# ProPrj_RGB_AddOn.net
KiCad netlist of a schematic drawn in EasyEDA Pro
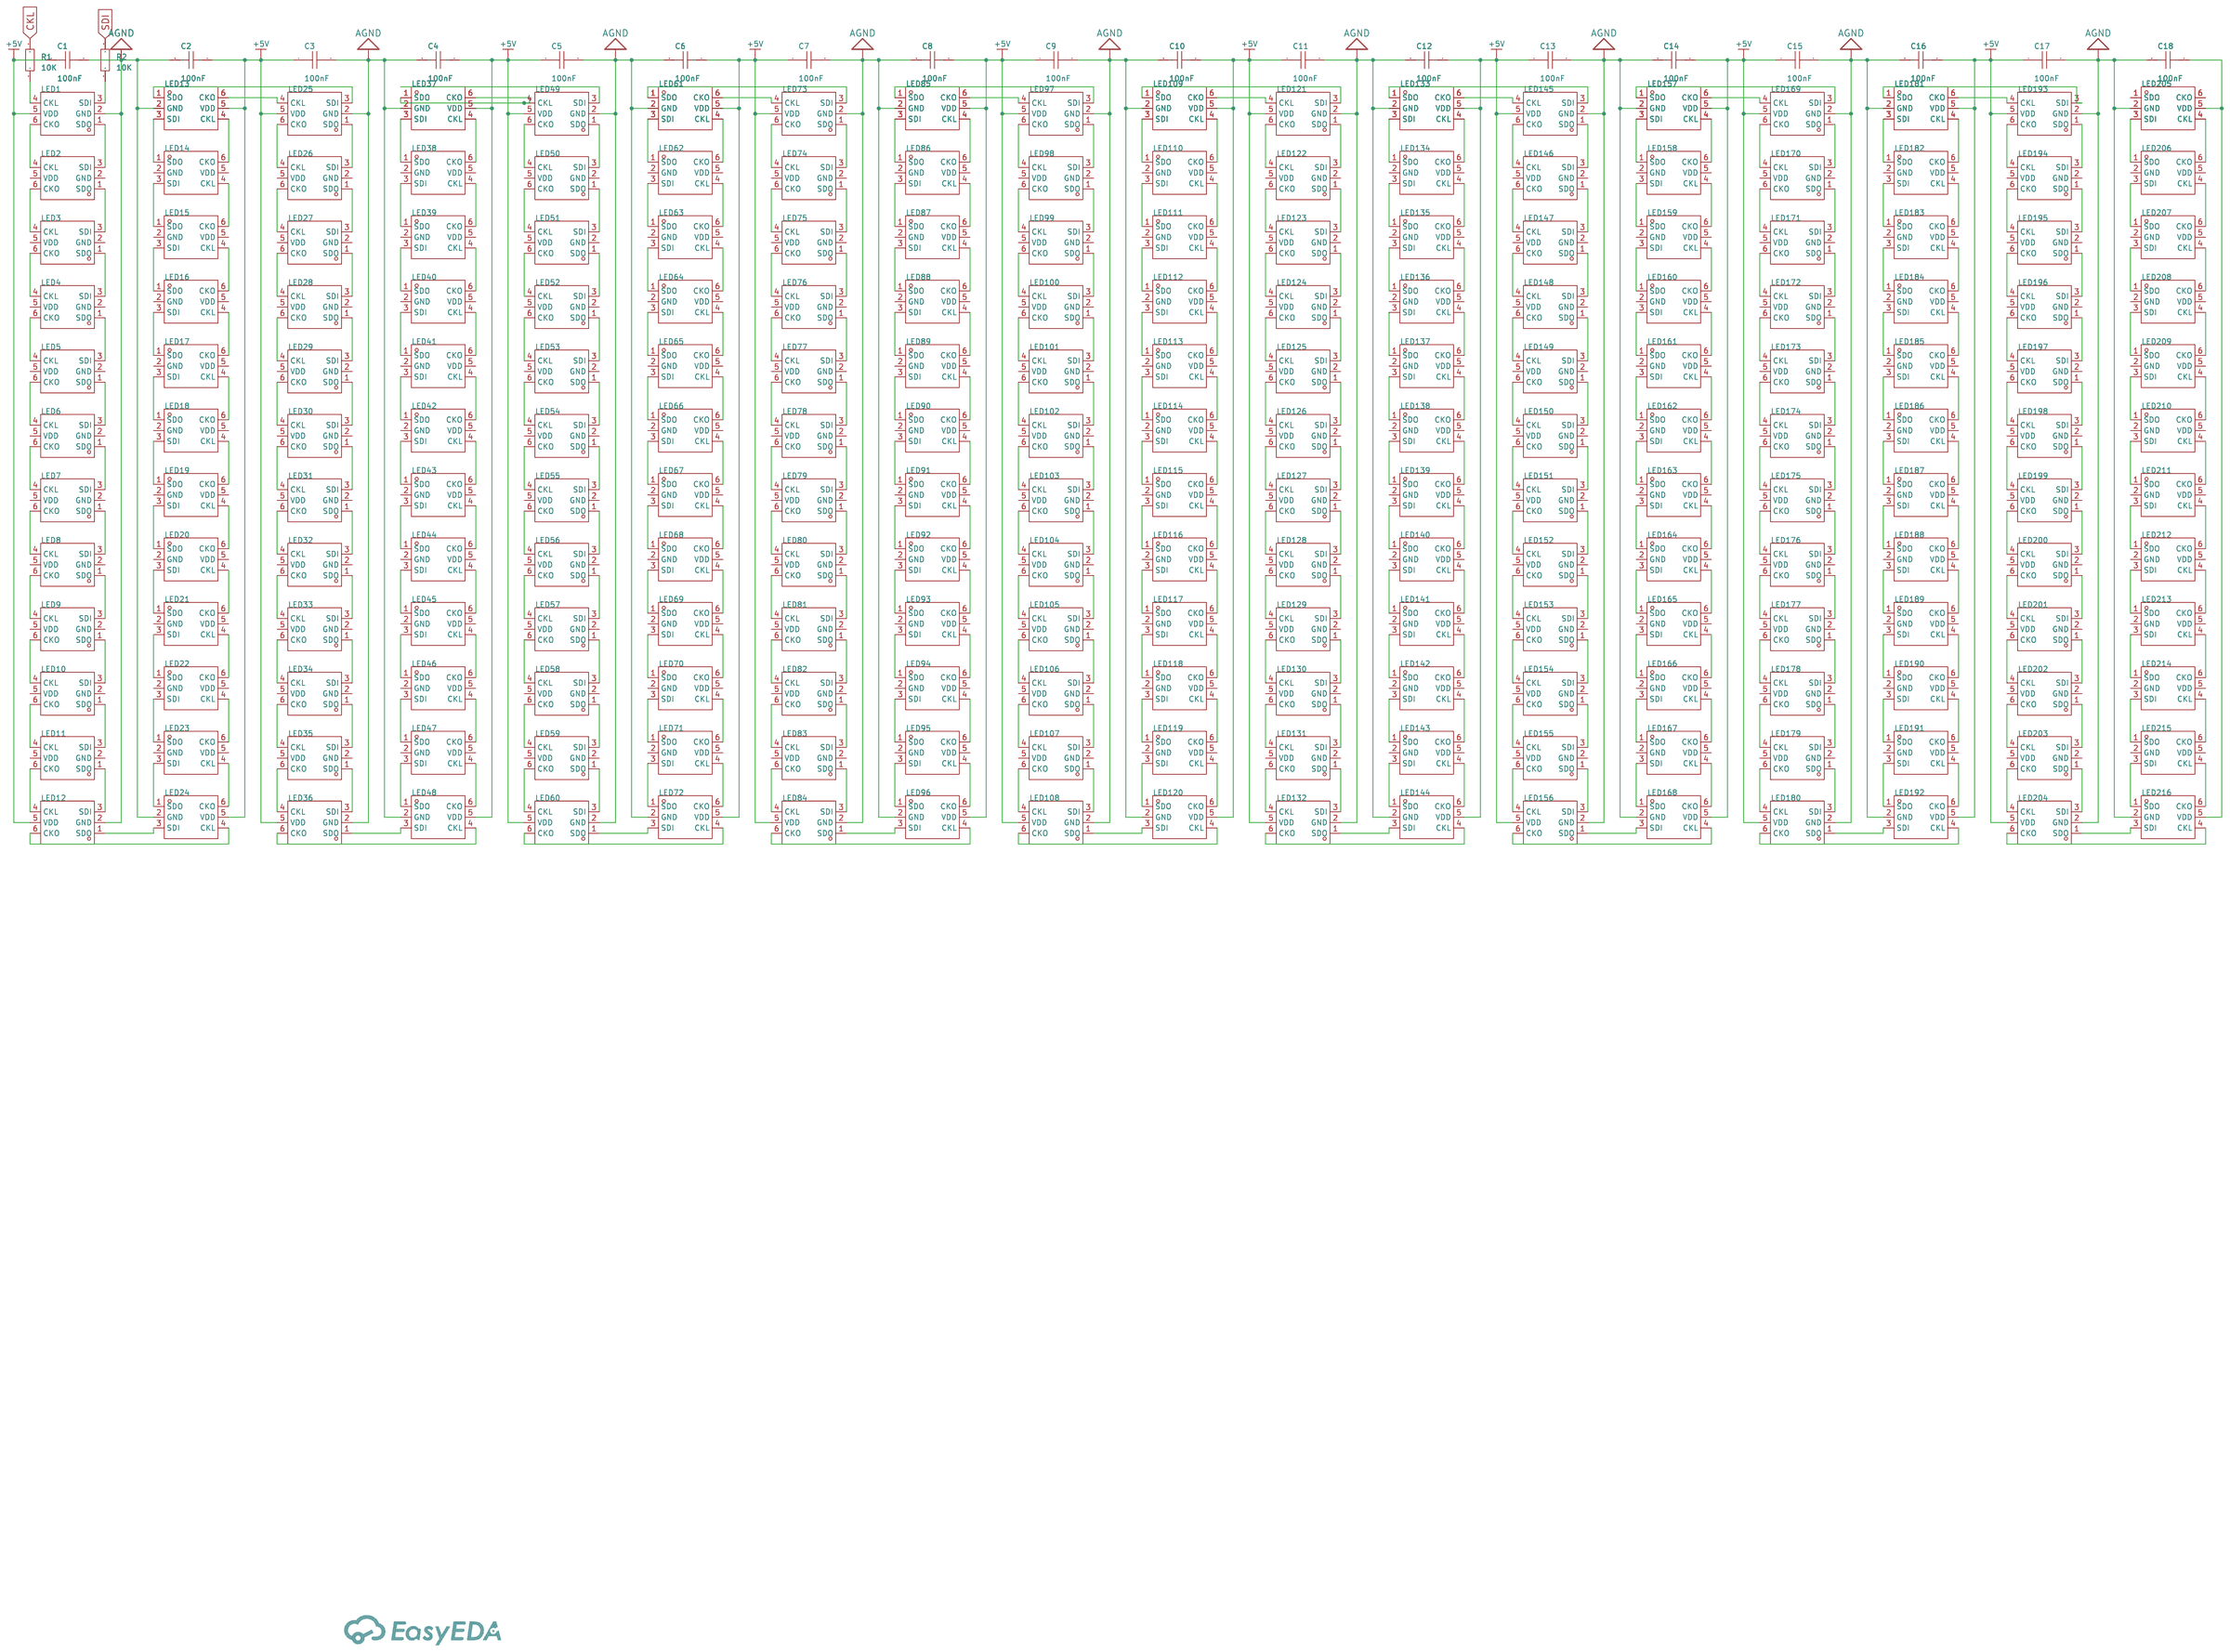
[diagram p0: Matrix]
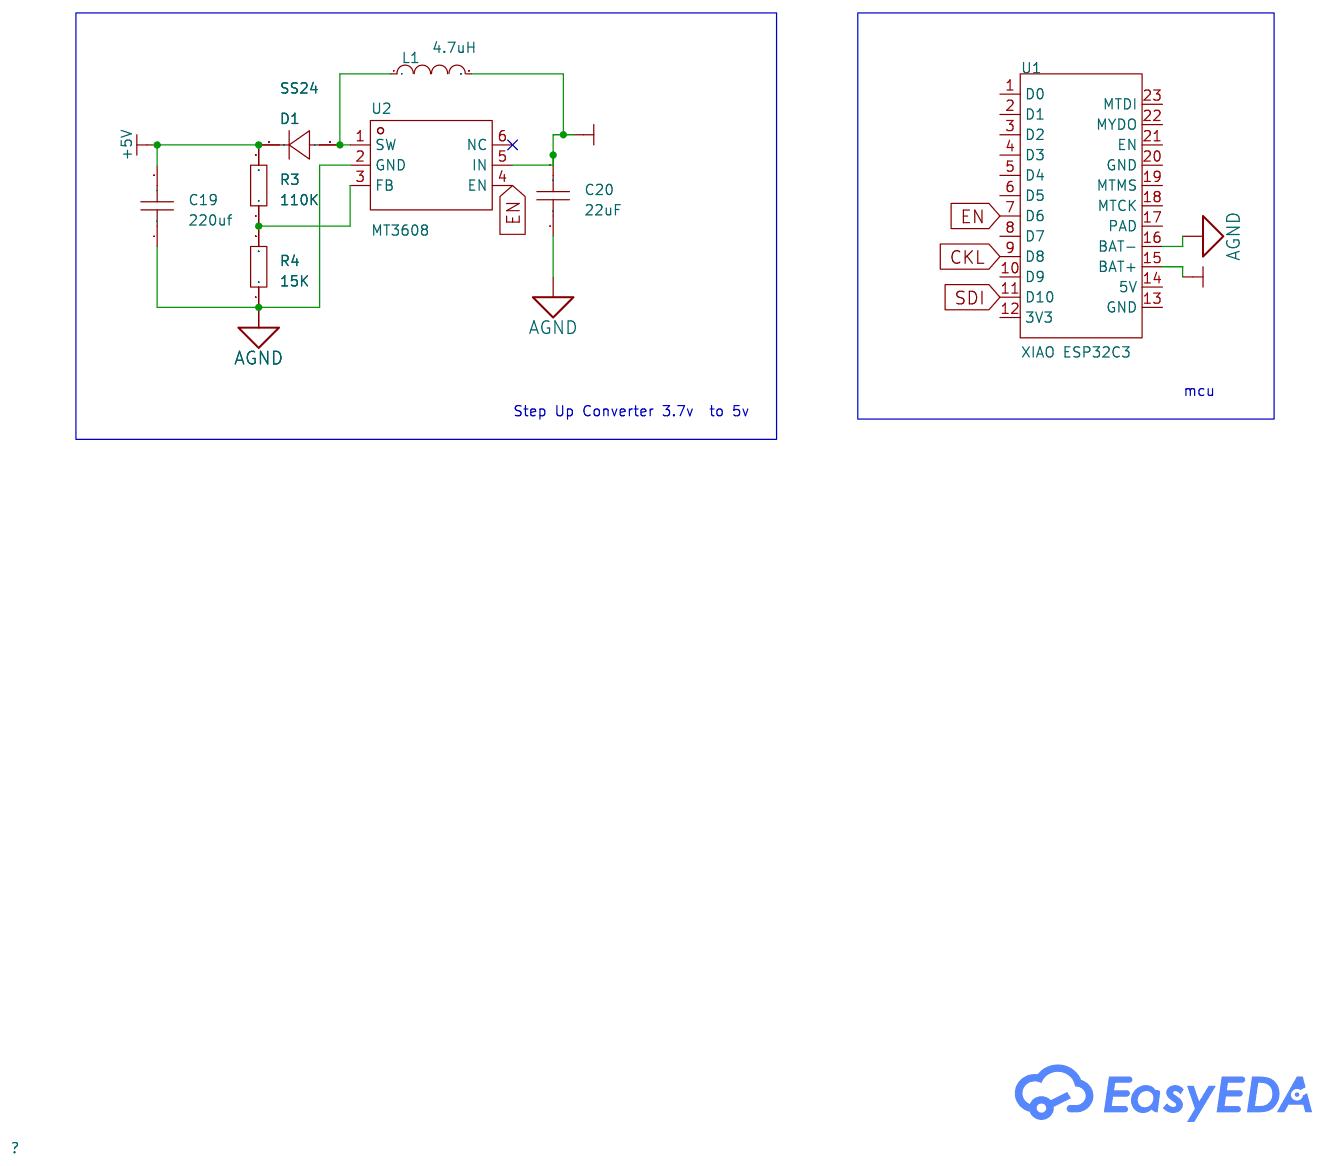
[diagram p1: MCU]

(export (version "E")
  (design (tool "Eeschema 10.0.6"))
  (components
    (comp (ref "C1")
      (value "100nF")
      (footprint "easyedapro:C0603")
      (libsource (lib "easyedapro") (part "CAP"))
    )
    (comp (ref "C2")
      (value "100nF")
      (footprint "easyedapro:C0603")
      (libsource (lib "easyedapro") (part "CAP"))
    )
    (comp (ref "C3")
      (value "100nF")
      (footprint "easyedapro:C0603")
      (libsource (lib "easyedapro") (part "CAP"))
    )
    (comp (ref "C4")
      (value "100nF")
      (footprint "easyedapro:C0603")
      (libsource (lib "easyedapro") (part "CAP"))
    )
    (comp (ref "C5")
      (value "100nF")
      (footprint "easyedapro:C0603")
      (libsource (lib "easyedapro") (part "CAP"))
    )
    (comp (ref "C6")
      (value "100nF")
      (footprint "easyedapro:C0603")
      (libsource (lib "easyedapro") (part "CAP"))
    )
    (comp (ref "C7")
      (value "100nF")
      (footprint "easyedapro:C0603")
      (libsource (lib "easyedapro") (part "CAP"))
    )
    (comp (ref "C8")
      (value "100nF")
      (footprint "easyedapro:C0603")
      (libsource (lib "easyedapro") (part "CAP"))
    )
    (comp (ref "C9")
      (value "100nF")
      (footprint "easyedapro:C0603")
      (libsource (lib "easyedapro") (part "CAP"))
    )
    (comp (ref "C10")
      (value "100nF")
      (footprint "easyedapro:C0603")
      (libsource (lib "easyedapro") (part "CAP"))
    )
    (comp (ref "C11")
      (value "100nF")
      (footprint "easyedapro:C0603")
      (libsource (lib "easyedapro") (part "CAP"))
    )
    (comp (ref "C12")
      (value "100nF")
      (footprint "easyedapro:C0603")
      (libsource (lib "easyedapro") (part "CAP"))
    )
    (comp (ref "C13")
      (value "100nF")
      (footprint "easyedapro:C0603")
      (libsource (lib "easyedapro") (part "CAP"))
    )
    (comp (ref "C14")
      (value "100nF")
      (footprint "easyedapro:C0603")
      (libsource (lib "easyedapro") (part "CAP"))
    )
    (comp (ref "C15")
      (value "100nF")
      (footprint "easyedapro:C0603")
      (libsource (lib "easyedapro") (part "CAP"))
    )
    (comp (ref "C16")
      (value "100nF")
      (footprint "easyedapro:C0603")
      (libsource (lib "easyedapro") (part "CAP"))
    )
    (comp (ref "C17")
      (value "100nF")
      (footprint "easyedapro:C0603")
      (libsource (lib "easyedapro") (part "CAP"))
    )
    (comp (ref "C18")
      (value "100nF")
      (footprint "easyedapro:C0603")
      (libsource (lib "easyedapro") (part "CAP"))
    )
    (comp (ref "LED1")
      (value "SK9822-EC20")
      (footprint "easyedapro:LED-SMD_6P-L2.0-W2.0-P0.80-TL")
      (description "Wavelength:620nm~625nm；460nm~470nm；520nm~530nm Operating Temperature:-40°C~+80°C")
      (fields (field (name "Manufacturer") "欧思科光电"))
      (libsource (lib "easyedapro") (part "SK9822-EC20"))
    )
    (comp (ref "LED2")
      (value "SK9822-EC20")
      (footprint "easyedapro:LED-SMD_6P-L2.0-W2.0-P0.80-TL")
      (description "Wavelength:620nm~625nm；460nm~470nm；520nm~530nm Operating Temperature:-40°C~+80°C")
      (fields (field (name "Manufacturer") "欧思科光电"))
      (libsource (lib "easyedapro") (part "SK9822-EC20"))
    )
    (comp (ref "LED3")
      (value "SK9822-EC20")
      (footprint "easyedapro:LED-SMD_6P-L2.0-W2.0-P0.80-TL")
      (description "Wavelength:620nm~625nm；460nm~470nm；520nm~530nm Operating Temperature:-40°C~+80°C")
      (fields (field (name "Manufacturer") "欧思科光电"))
      (libsource (lib "easyedapro") (part "SK9822-EC20"))
    )
    (comp (ref "LED4")
      (value "SK9822-EC20")
      (footprint "easyedapro:LED-SMD_6P-L2.0-W2.0-P0.80-TL")
      (description "Wavelength:620nm~625nm；460nm~470nm；520nm~530nm Operating Temperature:-40°C~+80°C")
      (fields (field (name "Manufacturer") "欧思科光电"))
      (libsource (lib "easyedapro") (part "SK9822-EC20"))
    )
    (comp (ref "LED5")
      (value "SK9822-EC20")
      (footprint "easyedapro:LED-SMD_6P-L2.0-W2.0-P0.80-TL")
      (description "Wavelength:620nm~625nm；460nm~470nm；520nm~530nm Operating Temperature:-40°C~+80°C")
      (fields (field (name "Manufacturer") "欧思科光电"))
      (libsource (lib "easyedapro") (part "SK9822-EC20"))
    )
    (comp (ref "LED6")
      (value "SK9822-EC20")
      (footprint "easyedapro:LED-SMD_6P-L2.0-W2.0-P0.80-TL")
      (description "Wavelength:620nm~625nm；460nm~470nm；520nm~530nm Operating Temperature:-40°C~+80°C")
      (fields (field (name "Manufacturer") "欧思科光电"))
      (libsource (lib "easyedapro") (part "SK9822-EC20"))
    )
    (comp (ref "LED7")
      (value "SK9822-EC20")
      (footprint "easyedapro:LED-SMD_6P-L2.0-W2.0-P0.80-TL")
      (description "Wavelength:620nm~625nm；460nm~470nm；520nm~530nm Operating Temperature:-40°C~+80°C")
      (fields (field (name "Manufacturer") "欧思科光电"))
      (libsource (lib "easyedapro") (part "SK9822-EC20"))
    )
    (comp (ref "LED8")
      (value "SK9822-EC20")
      (footprint "easyedapro:LED-SMD_6P-L2.0-W2.0-P0.80-TL")
      (description "Wavelength:620nm~625nm；460nm~470nm；520nm~530nm Operating Temperature:-40°C~+80°C")
      (fields (field (name "Manufacturer") "欧思科光电"))
      (libsource (lib "easyedapro") (part "SK9822-EC20"))
    )
    (comp (ref "LED9")
      (value "SK9822-EC20")
      (footprint "easyedapro:LED-SMD_6P-L2.0-W2.0-P0.80-TL")
      (description "Wavelength:620nm~625nm；460nm~470nm；520nm~530nm Operating Temperature:-40°C~+80°C")
      (fields (field (name "Manufacturer") "欧思科光电"))
      (libsource (lib "easyedapro") (part "SK9822-EC20"))
    )
    (comp (ref "LED10")
      (value "SK9822-EC20")
      (footprint "easyedapro:LED-SMD_6P-L2.0-W2.0-P0.80-TL")
      (description "Wavelength:620nm~625nm；460nm~470nm；520nm~530nm Operating Temperature:-40°C~+80°C")
      (fields (field (name "Manufacturer") "欧思科光电"))
      (libsource (lib "easyedapro") (part "SK9822-EC20"))
    )
    (comp (ref "LED11")
      (value "SK9822-EC20")
      (footprint "easyedapro:LED-SMD_6P-L2.0-W2.0-P0.80-TL")
      (description "Wavelength:620nm~625nm；460nm~470nm；520nm~530nm Operating Temperature:-40°C~+80°C")
      (fields (field (name "Manufacturer") "欧思科光电"))
      (libsource (lib "easyedapro") (part "SK9822-EC20"))
    )
    (comp (ref "LED12")
      (value "SK9822-EC20")
      (footprint "easyedapro:LED-SMD_6P-L2.0-W2.0-P0.80-TL")
      (description "Wavelength:620nm~625nm；460nm~470nm；520nm~530nm Operating Temperature:-40°C~+80°C")
      (fields (field (name "Manufacturer") "欧思科光电"))
      (libsource (lib "easyedapro") (part "SK9822-EC20"))
    )
    (comp (ref "LED13")
      (value "SK9822-EC20")
      (footprint "easyedapro:LED-SMD_6P-L2.0-W2.0-P0.80-TL")
      (description "Wavelength:620nm~625nm；460nm~470nm；520nm~530nm Operating Temperature:-40°C~+80°C")
      (fields (field (name "Manufacturer") "欧思科光电"))
      (libsource (lib "easyedapro") (part "SK9822-EC20"))
    )
    (comp (ref "LED14")
      (value "SK9822-EC20")
      (footprint "easyedapro:LED-SMD_6P-L2.0-W2.0-P0.80-TL")
      (description "Wavelength:620nm~625nm；460nm~470nm；520nm~530nm Operating Temperature:-40°C~+80°C")
      (fields (field (name "Manufacturer") "欧思科光电"))
      (libsource (lib "easyedapro") (part "SK9822-EC20"))
    )
    (comp (ref "LED15")
      (value "SK9822-EC20")
      (footprint "easyedapro:LED-SMD_6P-L2.0-W2.0-P0.80-TL")
      (description "Wavelength:620nm~625nm；460nm~470nm；520nm~530nm Operating Temperature:-40°C~+80°C")
      (fields (field (name "Manufacturer") "欧思科光电"))
      (libsource (lib "easyedapro") (part "SK9822-EC20"))
    )
    (comp (ref "LED16")
      (value "SK9822-EC20")
      (footprint "easyedapro:LED-SMD_6P-L2.0-W2.0-P0.80-TL")
      (description "Wavelength:620nm~625nm；460nm~470nm；520nm~530nm Operating Temperature:-40°C~+80°C")
      (fields (field (name "Manufacturer") "欧思科光电"))
      (libsource (lib "easyedapro") (part "SK9822-EC20"))
    )
    (comp (ref "LED17")
      (value "SK9822-EC20")
      (footprint "easyedapro:LED-SMD_6P-L2.0-W2.0-P0.80-TL")
      (description "Wavelength:620nm~625nm；460nm~470nm；520nm~530nm Operating Temperature:-40°C~+80°C")
      (fields (field (name "Manufacturer") "欧思科光电"))
      (libsource (lib "easyedapro") (part "SK9822-EC20"))
    )
    (comp (ref "LED18")
      (value "SK9822-EC20")
      (footprint "easyedapro:LED-SMD_6P-L2.0-W2.0-P0.80-TL")
      (description "Wavelength:620nm~625nm；460nm~470nm；520nm~530nm Operating Temperature:-40°C~+80°C")
      (fields (field (name "Manufacturer") "欧思科光电"))
      (libsource (lib "easyedapro") (part "SK9822-EC20"))
    )
    (comp (ref "LED19")
      (value "SK9822-EC20")
      (footprint "easyedapro:LED-SMD_6P-L2.0-W2.0-P0.80-TL")
      (description "Wavelength:620nm~625nm；460nm~470nm；520nm~530nm Operating Temperature:-40°C~+80°C")
      (fields (field (name "Manufacturer") "欧思科光电"))
      (libsource (lib "easyedapro") (part "SK9822-EC20"))
    )
    (comp (ref "LED20")
      (value "SK9822-EC20")
      (footprint "easyedapro:LED-SMD_6P-L2.0-W2.0-P0.80-TL")
      (description "Wavelength:620nm~625nm；460nm~470nm；520nm~530nm Operating Temperature:-40°C~+80°C")
      (fields (field (name "Manufacturer") "欧思科光电"))
      (libsource (lib "easyedapro") (part "SK9822-EC20"))
    )
    (comp (ref "LED21")
      (value "SK9822-EC20")
      (footprint "easyedapro:LED-SMD_6P-L2.0-W2.0-P0.80-TL")
      (description "Wavelength:620nm~625nm；460nm~470nm；520nm~530nm Operating Temperature:-40°C~+80°C")
      (fields (field (name "Manufacturer") "欧思科光电"))
      (libsource (lib "easyedapro") (part "SK9822-EC20"))
    )
    (comp (ref "LED22")
      (value "SK9822-EC20")
      (footprint "easyedapro:LED-SMD_6P-L2.0-W2.0-P0.80-TL")
      (description "Wavelength:620nm~625nm；460nm~470nm；520nm~530nm Operating Temperature:-40°C~+80°C")
      (fields (field (name "Manufacturer") "欧思科光电"))
      (libsource (lib "easyedapro") (part "SK9822-EC20"))
    )
    (comp (ref "LED23")
      (value "SK9822-EC20")
      (footprint "easyedapro:LED-SMD_6P-L2.0-W2.0-P0.80-TL")
      (description "Wavelength:620nm~625nm；460nm~470nm；520nm~530nm Operating Temperature:-40°C~+80°C")
      (fields (field (name "Manufacturer") "欧思科光电"))
      (libsource (lib "easyedapro") (part "SK9822-EC20"))
    )
    (comp (ref "LED24")
      (value "SK9822-EC20")
      (footprint "easyedapro:LED-SMD_6P-L2.0-W2.0-P0.80-TL")
      (description "Wavelength:620nm~625nm；460nm~470nm；520nm~530nm Operating Temperature:-40°C~+80°C")
      (fields (field (name "Manufacturer") "欧思科光电"))
      (libsource (lib "easyedapro") (part "SK9822-EC20"))
    )
    (comp (ref "LED25")
      (value "SK9822-EC20")
      (footprint "easyedapro:LED-SMD_6P-L2.0-W2.0-P0.80-TL")
      (description "Wavelength:620nm~625nm；460nm~470nm；520nm~530nm Operating Temperature:-40°C~+80°C")
      (fields (field (name "Manufacturer") "欧思科光电"))
      (libsource (lib "easyedapro") (part "SK9822-EC20"))
    )
    (comp (ref "LED26")
      (value "SK9822-EC20")
      (footprint "easyedapro:LED-SMD_6P-L2.0-W2.0-P0.80-TL")
      (description "Wavelength:620nm~625nm；460nm~470nm；520nm~530nm Operating Temperature:-40°C~+80°C")
      (fields (field (name "Manufacturer") "欧思科光电"))
      (libsource (lib "easyedapro") (part "SK9822-EC20"))
    )
    (comp (ref "LED27")
      (value "SK9822-EC20")
      (footprint "easyedapro:LED-SMD_6P-L2.0-W2.0-P0.80-TL")
      (description "Wavelength:620nm~625nm；460nm~470nm；520nm~530nm Operating Temperature:-40°C~+80°C")
      (fields (field (name "Manufacturer") "欧思科光电"))
      (libsource (lib "easyedapro") (part "SK9822-EC20"))
    )
    (comp (ref "LED28")
      (value "SK9822-EC20")
      (footprint "easyedapro:LED-SMD_6P-L2.0-W2.0-P0.80-TL")
      (description "Wavelength:620nm~625nm；460nm~470nm；520nm~530nm Operating Temperature:-40°C~+80°C")
      (fields (field (name "Manufacturer") "欧思科光电"))
      (libsource (lib "easyedapro") (part "SK9822-EC20"))
    )
    (comp (ref "LED29")
      (value "SK9822-EC20")
      (footprint "easyedapro:LED-SMD_6P-L2.0-W2.0-P0.80-TL")
      (description "Wavelength:620nm~625nm；460nm~470nm；520nm~530nm Operating Temperature:-40°C~+80°C")
      (fields (field (name "Manufacturer") "欧思科光电"))
      (libsource (lib "easyedapro") (part "SK9822-EC20"))
    )
    (comp (ref "LED30")
      (value "SK9822-EC20")
      (footprint "easyedapro:LED-SMD_6P-L2.0-W2.0-P0.80-TL")
      (description "Wavelength:620nm~625nm；460nm~470nm；520nm~530nm Operating Temperature:-40°C~+80°C")
      (fields (field (name "Manufacturer") "欧思科光电"))
      (libsource (lib "easyedapro") (part "SK9822-EC20"))
    )
    (comp (ref "LED31")
      (value "SK9822-EC20")
      (footprint "easyedapro:LED-SMD_6P-L2.0-W2.0-P0.80-TL")
      (description "Wavelength:620nm~625nm；460nm~470nm；520nm~530nm Operating Temperature:-40°C~+80°C")
      (fields (field (name "Manufacturer") "欧思科光电"))
      (libsource (lib "easyedapro") (part "SK9822-EC20"))
    )
    (comp (ref "LED32")
      (value "SK9822-EC20")
      (footprint "easyedapro:LED-SMD_6P-L2.0-W2.0-P0.80-TL")
      (description "Wavelength:620nm~625nm；460nm~470nm；520nm~530nm Operating Temperature:-40°C~+80°C")
      (fields (field (name "Manufacturer") "欧思科光电"))
      (libsource (lib "easyedapro") (part "SK9822-EC20"))
    )
    (comp (ref "LED33")
      (value "SK9822-EC20")
      (footprint "easyedapro:LED-SMD_6P-L2.0-W2.0-P0.80-TL")
      (description "Wavelength:620nm~625nm；460nm~470nm；520nm~530nm Operating Temperature:-40°C~+80°C")
      (fields (field (name "Manufacturer") "欧思科光电"))
      (libsource (lib "easyedapro") (part "SK9822-EC20"))
    )
    (comp (ref "LED34")
      (value "SK9822-EC20")
      (footprint "easyedapro:LED-SMD_6P-L2.0-W2.0-P0.80-TL")
      (description "Wavelength:620nm~625nm；460nm~470nm；520nm~530nm Operating Temperature:-40°C~+80°C")
      (fields (field (name "Manufacturer") "欧思科光电"))
      (libsource (lib "easyedapro") (part "SK9822-EC20"))
    )
    (comp (ref "LED35")
      (value "SK9822-EC20")
      (footprint "easyedapro:LED-SMD_6P-L2.0-W2.0-P0.80-TL")
      (description "Wavelength:620nm~625nm；460nm~470nm；520nm~530nm Operating Temperature:-40°C~+80°C")
      (fields (field (name "Manufacturer") "欧思科光电"))
      (libsource (lib "easyedapro") (part "SK9822-EC20"))
    )
    (comp (ref "LED36")
      (value "SK9822-EC20")
      (footprint "easyedapro:LED-SMD_6P-L2.0-W2.0-P0.80-TL")
      (description "Wavelength:620nm~625nm；460nm~470nm；520nm~530nm Operating Temperature:-40°C~+80°C")
      (fields (field (name "Manufacturer") "欧思科光电"))
      (libsource (lib "easyedapro") (part "SK9822-EC20"))
    )
    (comp (ref "LED37")
      (value "SK9822-EC20")
      (footprint "easyedapro:LED-SMD_6P-L2.0-W2.0-P0.80-TL")
      (description "Wavelength:620nm~625nm；460nm~470nm；520nm~530nm Operating Temperature:-40°C~+80°C")
      (fields (field (name "Manufacturer") "欧思科光电"))
      (libsource (lib "easyedapro") (part "SK9822-EC20"))
    )
    (comp (ref "LED38")
      (value "SK9822-EC20")
      (footprint "easyedapro:LED-SMD_6P-L2.0-W2.0-P0.80-TL")
      (description "Wavelength:620nm~625nm；460nm~470nm；520nm~530nm Operating Temperature:-40°C~+80°C")
      (fields (field (name "Manufacturer") "欧思科光电"))
      (libsource (lib "easyedapro") (part "SK9822-EC20"))
    )
    (comp (ref "LED39")
      (value "SK9822-EC20")
      (footprint "easyedapro:LED-SMD_6P-L2.0-W2.0-P0.80-TL")
      (description "Wavelength:620nm~625nm；460nm~470nm；520nm~530nm Operating Temperature:-40°C~+80°C")
      (fields (field (name "Manufacturer") "欧思科光电"))
      (libsource (lib "easyedapro") (part "SK9822-EC20"))
    )
    (comp (ref "LED40")
      (value "SK9822-EC20")
      (footprint "easyedapro:LED-SMD_6P-L2.0-W2.0-P0.80-TL")
      (description "Wavelength:620nm~625nm；460nm~470nm；520nm~530nm Operating Temperature:-40°C~+80°C")
      (fields (field (name "Manufacturer") "欧思科光电"))
      (libsource (lib "easyedapro") (part "SK9822-EC20"))
    )
    (comp (ref "LED41")
      (value "SK9822-EC20")
      (footprint "easyedapro:LED-SMD_6P-L2.0-W2.0-P0.80-TL")
      (description "Wavelength:620nm~625nm；460nm~470nm；520nm~530nm Operating Temperature:-40°C~+80°C")
      (fields (field (name "Manufacturer") "欧思科光电"))
      (libsource (lib "easyedapro") (part "SK9822-EC20"))
    )
    (comp (ref "LED42")
      (value "SK9822-EC20")
      (footprint "easyedapro:LED-SMD_6P-L2.0-W2.0-P0.80-TL")
      (description "Wavelength:620nm~625nm；460nm~470nm；520nm~530nm Operating Temperature:-40°C~+80°C")
      (fields (field (name "Manufacturer") "欧思科光电"))
      (libsource (lib "easyedapro") (part "SK9822-EC20"))
    )
    (comp (ref "LED43")
      (value "SK9822-EC20")
      (footprint "easyedapro:LED-SMD_6P-L2.0-W2.0-P0.80-TL")
      (description "Wavelength:620nm~625nm；460nm~470nm；520nm~530nm Operating Temperature:-40°C~+80°C")
      (fields (field (name "Manufacturer") "欧思科光电"))
      (libsource (lib "easyedapro") (part "SK9822-EC20"))
    )
    (comp (ref "LED44")
      (value "SK9822-EC20")
      (footprint "easyedapro:LED-SMD_6P-L2.0-W2.0-P0.80-TL")
      (description "Wavelength:620nm~625nm；460nm~470nm；520nm~530nm Operating Temperature:-40°C~+80°C")
      (fields (field (name "Manufacturer") "欧思科光电"))
      (libsource (lib "easyedapro") (part "SK9822-EC20"))
    )
    (comp (ref "LED45")
      (value "SK9822-EC20")
      (footprint "easyedapro:LED-SMD_6P-L2.0-W2.0-P0.80-TL")
      (description "Wavelength:620nm~625nm；460nm~470nm；520nm~530nm Operating Temperature:-40°C~+80°C")
      (fields (field (name "Manufacturer") "欧思科光电"))
      (libsource (lib "easyedapro") (part "SK9822-EC20"))
    )
    (comp (ref "LED46")
      (value "SK9822-EC20")
      (footprint "easyedapro:LED-SMD_6P-L2.0-W2.0-P0.80-TL")
      (description "Wavelength:620nm~625nm；460nm~470nm；520nm~530nm Operating Temperature:-40°C~+80°C")
      (fields (field (name "Manufacturer") "欧思科光电"))
      (libsource (lib "easyedapro") (part "SK9822-EC20"))
    )
    (comp (ref "LED47")
      (value "SK9822-EC20")
      (footprint "easyedapro:LED-SMD_6P-L2.0-W2.0-P0.80-TL")
      (description "Wavelength:620nm~625nm；460nm~470nm；520nm~530nm Operating Temperature:-40°C~+80°C")
      (fields (field (name "Manufacturer") "欧思科光电"))
      (libsource (lib "easyedapro") (part "SK9822-EC20"))
    )
    (comp (ref "LED48")
      (value "SK9822-EC20")
      (footprint "easyedapro:LED-SMD_6P-L2.0-W2.0-P0.80-TL")
      (description "Wavelength:620nm~625nm；460nm~470nm；520nm~530nm Operating Temperature:-40°C~+80°C")
      (fields (field (name "Manufacturer") "欧思科光电"))
      (libsource (lib "easyedapro") (part "SK9822-EC20"))
    )
    (comp (ref "LED49")
      (value "SK9822-EC20")
      (footprint "easyedapro:LED-SMD_6P-L2.0-W2.0-P0.80-TL")
      (description "Wavelength:620nm~625nm；460nm~470nm；520nm~530nm Operating Temperature:-40°C~+80°C")
      (fields (field (name "Manufacturer") "欧思科光电"))
      (libsource (lib "easyedapro") (part "SK9822-EC20"))
    )
    (comp (ref "LED50")
      (value "SK9822-EC20")
      (footprint "easyedapro:LED-SMD_6P-L2.0-W2.0-P0.80-TL")
      (description "Wavelength:620nm~625nm；460nm~470nm；520nm~530nm Operating Temperature:-40°C~+80°C")
      (fields (field (name "Manufacturer") "欧思科光电"))
      (libsource (lib "easyedapro") (part "SK9822-EC20"))
    )
    (comp (ref "LED51")
      (value "SK9822-EC20")
      (footprint "easyedapro:LED-SMD_6P-L2.0-W2.0-P0.80-TL")
      (description "Wavelength:620nm~625nm；460nm~470nm；520nm~530nm Operating Temperature:-40°C~+80°C")
      (fields (field (name "Manufacturer") "欧思科光电"))
      (libsource (lib "easyedapro") (part "SK9822-EC20"))
    )
    (comp (ref "LED52")
      (value "SK9822-EC20")
      (footprint "easyedapro:LED-SMD_6P-L2.0-W2.0-P0.80-TL")
      (description "Wavelength:620nm~625nm；460nm~470nm；520nm~530nm Operating Temperature:-40°C~+80°C")
      (fields (field (name "Manufacturer") "欧思科光电"))
      (libsource (lib "easyedapro") (part "SK9822-EC20"))
    )
    (comp (ref "LED53")
      (value "SK9822-EC20")
      (footprint "easyedapro:LED-SMD_6P-L2.0-W2.0-P0.80-TL")
      (description "Wavelength:620nm~625nm；460nm~470nm；520nm~530nm Operating Temperature:-40°C~+80°C")
      (fields (field (name "Manufacturer") "欧思科光电"))
      (libsource (lib "easyedapro") (part "SK9822-EC20"))
    )
    (comp (ref "LED54")
      (value "SK9822-EC20")
      (footprint "easyedapro:LED-SMD_6P-L2.0-W2.0-P0.80-TL")
      (description "Wavelength:620nm~625nm；460nm~470nm；520nm~530nm Operating Temperature:-40°C~+80°C")
      (fields (field (name "Manufacturer") "欧思科光电"))
      (libsource (lib "easyedapro") (part "SK9822-EC20"))
    )
    (comp (ref "LED55")
      (value "SK9822-EC20")
      (footprint "easyedapro:LED-SMD_6P-L2.0-W2.0-P0.80-TL")
      (description "Wavelength:620nm~625nm；460nm~470nm；520nm~530nm Operating Temperature:-40°C~+80°C")
      (fields (field (name "Manufacturer") "欧思科光电"))
      (libsource (lib "easyedapro") (part "SK9822-EC20"))
    )
    (comp (ref "LED56")
      (value "SK9822-EC20")
      (footprint "easyedapro:LED-SMD_6P-L2.0-W2.0-P0.80-TL")
      (description "Wavelength:620nm~625nm；460nm~470nm；520nm~530nm Operating Temperature:-40°C~+80°C")
      (fields (field (name "Manufacturer") "欧思科光电"))
      (libsource (lib "easyedapro") (part "SK9822-EC20"))
    )
    (comp (ref "LED57")
      (value "SK9822-EC20")
      (footprint "easyedapro:LED-SMD_6P-L2.0-W2.0-P0.80-TL")
      (description "Wavelength:620nm~625nm；460nm~470nm；520nm~530nm Operating Temperature:-40°C~+80°C")
      (fields (field (name "Manufacturer") "欧思科光电"))
      (libsource (lib "easyedapro") (part "SK9822-EC20"))
    )
    (comp (ref "LED58")
      (value "SK9822-EC20")
      (footprint "easyedapro:LED-SMD_6P-L2.0-W2.0-P0.80-TL")
      (description "Wavelength:620nm~625nm；460nm~470nm；520nm~530nm Operating Temperature:-40°C~+80°C")
      (fields (field (name "Manufacturer") "欧思科光电"))
      (libsource (lib "easyedapro") (part "SK9822-EC20"))
    )
    (comp (ref "LED59")
      (value "SK9822-EC20")
      (footprint "easyedapro:LED-SMD_6P-L2.0-W2.0-P0.80-TL")
      (description "Wavelength:620nm~625nm；460nm~470nm；520nm~530nm Operating Temperature:-40°C~+80°C")
      (fields (field (name "Manufacturer") "欧思科光电"))
      (libsource (lib "easyedapro") (part "SK9822-EC20"))
    )
    (comp (ref "LED60")
      (value "SK9822-EC20")
      (footprint "easyedapro:LED-SMD_6P-L2.0-W2.0-P0.80-TL")
      (description "Wavelength:620nm~625nm；460nm~470nm；520nm~530nm Operating Temperature:-40°C~+80°C")
      (fields (field (name "Manufacturer") "欧思科光电"))
      (libsource (lib "easyedapro") (part "SK9822-EC20"))
    )
    (comp (ref "LED61")
      (value "SK9822-EC20")
      (footprint "easyedapro:LED-SMD_6P-L2.0-W2.0-P0.80-TL")
      (description "Wavelength:620nm~625nm；460nm~470nm；520nm~530nm Operating Temperature:-40°C~+80°C")
      (fields (field (name "Manufacturer") "欧思科光电"))
      (libsource (lib "easyedapro") (part "SK9822-EC20"))
    )
    (comp (ref "LED62")
      (value "SK9822-EC20")
      (footprint "easyedapro:LED-SMD_6P-L2.0-W2.0-P0.80-TL")
      (description "Wavelength:620nm~625nm；460nm~470nm；520nm~530nm Operating Temperature:-40°C~+80°C")
      (fields (field (name "Manufacturer") "欧思科光电"))
      (libsource (lib "easyedapro") (part "SK9822-EC20"))
    )
    (comp (ref "LED63")
      (value "SK9822-EC20")
      (footprint "easyedapro:LED-SMD_6P-L2.0-W2.0-P0.80-TL")
      (description "Wavelength:620nm~625nm；460nm~470nm；520nm~530nm Operating Temperature:-40°C~+80°C")
      (fields (field (name "Manufacturer") "欧思科光电"))
      (libsource (lib "easyedapro") (part "SK9822-EC20"))
    )
    (comp (ref "LED64")
      (value "SK9822-EC20")
      (footprint "easyedapro:LED-SMD_6P-L2.0-W2.0-P0.80-TL")
      (description "Wavelength:620nm~625nm；460nm~470nm；520nm~530nm Operating Temperature:-40°C~+80°C")
      (fields (field (name "Manufacturer") "欧思科光电"))
      (libsource (lib "easyedapro") (part "SK9822-EC20"))
    )
    (comp (ref "LED65")
      (value "SK9822-EC20")
      (footprint "easyedapro:LED-SMD_6P-L2.0-W2.0-P0.80-TL")
      (description "Wavelength:620nm~625nm；460nm~470nm；520nm~530nm Operating Temperature:-40°C~+80°C")
      (fields (field (name "Manufacturer") "欧思科光电"))
      (libsource (lib "easyedapro") (part "SK9822-EC20"))
    )
    (comp (ref "LED66")
      (value "SK9822-EC20")
      (footprint "easyedapro:LED-SMD_6P-L2.0-W2.0-P0.80-TL")
      (description "Wavelength:620nm~625nm；460nm~470nm；520nm~530nm Operating Temperature:-40°C~+80°C")
      (fields (field (name "Manufacturer") "欧思科光电"))
      (libsource (lib "easyedapro") (part "SK9822-EC20"))
    )
    (comp (ref "LED67")
      (value "SK9822-EC20")
      (footprint "easyedapro:LED-SMD_6P-L2.0-W2.0-P0.80-TL")
      (description "Wavelength:620nm~625nm；460nm~470nm；520nm~530nm Operating Temperature:-40°C~+80°C")
      (fields (field (name "Manufacturer") "欧思科光电"))
      (libsource (lib "easyedapro") (part "SK9822-EC20"))
    )
    (comp (ref "LED68")
      (value "SK9822-EC20")
      (footprint "easyedapro:LED-SMD_6P-L2.0-W2.0-P0.80-TL")
      (description "Wavelength:620nm~625nm；460nm~470nm；520nm~530nm Operating Temperature:-40°C~+80°C")
      (fields (field (name "Manufacturer") "欧思科光电"))
      (libsource (lib "easyedapro") (part "SK9822-EC20"))
    )
    (comp (ref "LED69")
      (value "SK9822-EC20")
      (footprint "easyedapro:LED-SMD_6P-L2.0-W2.0-P0.80-TL")
      (description "Wavelength:620nm~625nm；460nm~470nm；520nm~530nm Operating Temperature:-40°C~+80°C")
      (fields (field (name "Manufacturer") "欧思科光电"))
      (libsource (lib "easyedapro") (part "SK9822-EC20"))
    )
    (comp (ref "LED70")
      (value "SK9822-EC20")
      (footprint "easyedapro:LED-SMD_6P-L2.0-W2.0-P0.80-TL")
      (description "Wavelength:620nm~625nm；460nm~470nm；520nm~530nm Operating Temperature:-40°C~+80°C")
      (fields (field (name "Manufacturer") "欧思科光电"))
      (libsource (lib "easyedapro") (part "SK9822-EC20"))
    )
    (comp (ref "LED71")
      (value "SK9822-EC20")
      (footprint "easyedapro:LED-SMD_6P-L2.0-W2.0-P0.80-TL")
      (description "Wavelength:620nm~625nm；460nm~470nm；520nm~530nm Operating Temperature:-40°C~+80°C")
      (fields (field (name "Manufacturer") "欧思科光电"))
      (libsource (lib "easyedapro") (part "SK9822-EC20"))
    )
    (comp (ref "LED72")
      (value "SK9822-EC20")
      (footprint "easyedapro:LED-SMD_6P-L2.0-W2.0-P0.80-TL")
      (description "Wavelength:620nm~625nm；460nm~470nm；520nm~530nm Operating Temperature:-40°C~+80°C")
      (fields (field (name "Manufacturer") "欧思科光电"))
      (libsource (lib "easyedapro") (part "SK9822-EC20"))
    )
    (comp (ref "LED73")
      (value "SK9822-EC20")
      (footprint "easyedapro:LED-SMD_6P-L2.0-W2.0-P0.80-TL")
      (description "Wavelength:620nm~625nm；460nm~470nm；520nm~530nm Operating Temperature:-40°C~+80°C")
      (fields (field (name "Manufacturer") "欧思科光电"))
      (libsource (lib "easyedapro") (part "SK9822-EC20"))
    )
    (comp (ref "LED74")
      (value "SK9822-EC20")
      (footprint "easyedapro:LED-SMD_6P-L2.0-W2.0-P0.80-TL")
      (description "Wavelength:620nm~625nm；460nm~470nm；520nm~530nm Operating Temperature:-40°C~+80°C")
      (fields (field (name "Manufacturer") "欧思科光电"))
      (libsource (lib "easyedapro") (part "SK9822-EC20"))
    )
    (comp (ref "LED75")
      (value "SK9822-EC20")
      (footprint "easyedapro:LED-SMD_6P-L2.0-W2.0-P0.80-TL")
      (description "Wavelength:620nm~625nm；460nm~470nm；520nm~530nm Operating Temperature:-40°C~+80°C")
      (fields (field (name "Manufacturer") "欧思科光电"))
      (libsource (lib "easyedapro") (part "SK9822-EC20"))
    )
    (comp (ref "LED76")
      (value "SK9822-EC20")
      (footprint "easyedapro:LED-SMD_6P-L2.0-W2.0-P0.80-TL")
      (description "Wavelength:620nm~625nm；460nm~470nm；520nm~530nm Operating Temperature:-40°C~+80°C")
      (fields (field (name "Manufacturer") "欧思科光电"))
      (libsource (lib "easyedapro") (part "SK9822-EC20"))
    )
    (comp (ref "LED77")
      (value "SK9822-EC20")
      (footprint "easyedapro:LED-SMD_6P-L2.0-W2.0-P0.80-TL")
      (description "Wavelength:620nm~625nm；460nm~470nm；520nm~530nm Operating Temperature:-40°C~+80°C")
      (fields (field (name "Manufacturer") "欧思科光电"))
      (libsource (lib "easyedapro") (part "SK9822-EC20"))
    )
    (comp (ref "LED78")
      (value "SK9822-EC20")
      (footprint "easyedapro:LED-SMD_6P-L2.0-W2.0-P0.80-TL")
      (description "Wavelength:620nm~625nm；460nm~470nm；520nm~530nm Operating Temperature:-40°C~+80°C")
      (fields (field (name "Manufacturer") "欧思科光电"))
      (libsource (lib "easyedapro") (part "SK9822-EC20"))
    )
    (comp (ref "LED79")
      (value "SK9822-EC20")
      (footprint "easyedapro:LED-SMD_6P-L2.0-W2.0-P0.80-TL")
      (description "Wavelength:620nm~625nm；460nm~470nm；520nm~530nm Operating Temperature:-40°C~+80°C")
      (fields (field (name "Manufacturer") "欧思科光电"))
      (libsource (lib "easyedapro") (part "SK9822-EC20"))
    )
    (comp (ref "LED80")
      (value "SK9822-EC20")
      (footprint "easyedapro:LED-SMD_6P-L2.0-W2.0-P0.80-TL")
      (description "Wavelength:620nm~625nm；460nm~470nm；520nm~530nm Operating Temperature:-40°C~+80°C")
      (fields (field (name "Manufacturer") "欧思科光电"))
      (libsource (lib "easyedapro") (part "SK9822-EC20"))
    )
    (comp (ref "LED81")
      (value "SK9822-EC20")
      (footprint "easyedapro:LED-SMD_6P-L2.0-W2.0-P0.80-TL")
      (description "Wavelength:620nm~625nm；460nm~470nm；520nm~530nm Operating Temperature:-40°C~+80°C")
      (fields (field (name "Manufacturer") "欧思科光电"))
      (libsource (lib "easyedapro") (part "SK9822-EC20"))
    )
    (comp (ref "LED82")
      (value "SK9822-EC20")
      (footprint "easyedapro:LED-SMD_6P-L2.0-W2.0-P0.80-TL")
      (description "Wavelength:620nm~625nm；460nm~470nm；520nm~530nm Operating Temperature:-40°C~+80°C")
      (fields (field (name "Manufacturer") "欧思科光电"))
      (libsource (lib "easyedapro") (part "SK9822-EC20"))
    )
    (comp (ref "LED83")
      (value "SK9822-EC20")
      (footprint "easyedapro:LED-SMD_6P-L2.0-W2.0-P0.80-TL")
      (description "Wavelength:620nm~625nm；460nm~470nm；520nm~530nm Operating Temperature:-40°C~+80°C")
      (fields (field (name "Manufacturer") "欧思科光电"))
      (libsource (lib "easyedapro") (part "SK9822-EC20"))
    )
    (comp (ref "LED84")
      (value "SK9822-EC20")
      (footprint "easyedapro:LED-SMD_6P-L2.0-W2.0-P0.80-TL")
      (description "Wavelength:620nm~625nm；460nm~470nm；520nm~530nm Operating Temperature:-40°C~+80°C")
      (fields (field (name "Manufacturer") "欧思科光电"))
      (libsource (lib "easyedapro") (part "SK9822-EC20"))
    )
    (comp (ref "LED85")
      (value "SK9822-EC20")
      (footprint "easyedapro:LED-SMD_6P-L2.0-W2.0-P0.80-TL")
      (description "Wavelength:620nm~625nm；460nm~470nm；520nm~530nm Operating Temperature:-40°C~+80°C")
      (fields (field (name "Manufacturer") "欧思科光电"))
      (libsource (lib "easyedapro") (part "SK9822-EC20"))
    )
    (comp (ref "LED86")
      (value "SK9822-EC20")
      (footprint "easyedapro:LED-SMD_6P-L2.0-W2.0-P0.80-TL")
      (description "Wavelength:620nm~625nm；460nm~470nm；520nm~530nm Operating Temperature:-40°C~+80°C")
      (fields (field (name "Manufacturer") "欧思科光电"))
      (libsource (lib "easyedapro") (part "SK9822-EC20"))
    )
    (comp (ref "LED87")
      (value "SK9822-EC20")
      (footprint "easyedapro:LED-SMD_6P-L2.0-W2.0-P0.80-TL")
      (description "Wavelength:620nm~625nm；460nm~470nm；520nm~530nm Operating Temperature:-40°C~+80°C")
      (fields (field (name "Manufacturer") "欧思科光电"))
      (libsource (lib "easyedapro") (part "SK9822-EC20"))
    )
    (comp (ref "LED88")
      (value "SK9822-EC20")
      (footprint "easyedapro:LED-SMD_6P-L2.0-W2.0-P0.80-TL")
      (description "Wavelength:620nm~625nm；460nm~470nm；520nm~530nm Operating Temperature:-40°C~+80°C")
      (fields (field (name "Manufacturer") "欧思科光电"))
      (libsource (lib "easyedapro") (part "SK9822-EC20"))
    )
    (comp (ref "LED89")
      (value "SK9822-EC20")
      (footprint "easyedapro:LED-SMD_6P-L2.0-W2.0-P0.80-TL")
      (description "Wavelength:620nm~625nm；460nm~470nm；520nm~530nm Operating Temperature:-40°C~+80°C")
      (fields (field (name "Manufacturer") "欧思科光电"))
      (libsource (lib "easyedapro") (part "SK9822-EC20"))
    )
    (comp (ref "LED90")
      (value "SK9822-EC20")
      (footprint "easyedapro:LED-SMD_6P-L2.0-W2.0-P0.80-TL")
      (description "Wavelength:620nm~625nm；460nm~470nm；520nm~530nm Operating Temperature:-40°C~+80°C")
      (fields (field (name "Manufacturer") "欧思科光电"))
      (libsource (lib "easyedapro") (part "SK9822-EC20"))
    )
    (comp (ref "LED91")
      (value "SK9822-EC20")
      (footprint "easyedapro:LED-SMD_6P-L2.0-W2.0-P0.80-TL")
      (description "Wavelength:620nm~625nm；460nm~470nm；520nm~530nm Operating Temperature:-40°C~+80°C")
      (fields (field (name "Manufacturer") "欧思科光电"))
      (libsource (lib "easyedapro") (part "SK9822-EC20"))
    )
    (comp (ref "LED92")
      (value "SK9822-EC20")
      (footprint "easyedapro:LED-SMD_6P-L2.0-W2.0-P0.80-TL")
      (description "Wavelength:620nm~625nm；460nm~470nm；520nm~530nm Operating Temperature:-40°C~+80°C")
      (fields (field (name "Manufacturer") "欧思科光电"))
      (libsource (lib "easyedapro") (part "SK9822-EC20"))
    )
    (comp (ref "LED93")
      (value "SK9822-EC20")
      (footprint "easyedapro:LED-SMD_6P-L2.0-W2.0-P0.80-TL")
      (description "Wavelength:620nm~625nm；460nm~470nm；520nm~530nm Operating Temperature:-40°C~+80°C")
      (fields (field (name "Manufacturer") "欧思科光电"))
      (libsource (lib "easyedapro") (part "SK9822-EC20"))
    )
    (comp (ref "LED94")
      (value "SK9822-EC20")
      (footprint "easyedapro:LED-SMD_6P-L2.0-W2.0-P0.80-TL")
      (description "Wavelength:620nm~625nm；460nm~470nm；520nm~530nm Operating Temperature:-40°C~+80°C")
      (fields (field (name "Manufacturer") "欧思科光电"))
      (libsource (lib "easyedapro") (part "SK9822-EC20"))
    )
    (comp (ref "LED95")
      (value "SK9822-EC20")
      (footprint "easyedapro:LED-SMD_6P-L2.0-W2.0-P0.80-TL")
      (description "Wavelength:620nm~625nm；460nm~470nm；520nm~530nm Operating Temperature:-40°C~+80°C")
      (fields (field (name "Manufacturer") "欧思科光电"))
      (libsource (lib "easyedapro") (part "SK9822-EC20"))
    )
    (comp (ref "LED96")
      (value "SK9822-EC20")
      (footprint "easyedapro:LED-SMD_6P-L2.0-W2.0-P0.80-TL")
      (description "Wavelength:620nm~625nm；460nm~470nm；520nm~530nm Operating Temperature:-40°C~+80°C")
      (fields (field (name "Manufacturer") "欧思科光电"))
      (libsource (lib "easyedapro") (part "SK9822-EC20"))
    )
    (comp (ref "LED97")
      (value "SK9822-EC20")
      (footprint "easyedapro:LED-SMD_6P-L2.0-W2.0-P0.80-TL")
      (description "Wavelength:620nm~625nm；460nm~470nm；520nm~530nm Operating Temperature:-40°C~+80°C")
      (fields (field (name "Manufacturer") "欧思科光电"))
      (libsource (lib "easyedapro") (part "SK9822-EC20"))
    )
    (comp (ref "LED98")
      (value "SK9822-EC20")
      (footprint "easyedapro:LED-SMD_6P-L2.0-W2.0-P0.80-TL")
      (description "Wavelength:620nm~625nm；460nm~470nm；520nm~530nm Operating Temperature:-40°C~+80°C")
      (fields (field (name "Manufacturer") "欧思科光电"))
      (libsource (lib "easyedapro") (part "SK9822-EC20"))
    )
    (comp (ref "LED99")
      (value "SK9822-EC20")
      (footprint "easyedapro:LED-SMD_6P-L2.0-W2.0-P0.80-TL")
      (description "Wavelength:620nm~625nm；460nm~470nm；520nm~530nm Operating Temperature:-40°C~+80°C")
      (fields (field (name "Manufacturer") "欧思科光电"))
      (libsource (lib "easyedapro") (part "SK9822-EC20"))
    )
    (comp (ref "LED100")
      (value "SK9822-EC20")
      (footprint "easyedapro:LED-SMD_6P-L2.0-W2.0-P0.80-TL")
      (description "Wavelength:620nm~625nm；460nm~470nm；520nm~530nm Operating Temperature:-40°C~+80°C")
      (fields (field (name "Manufacturer") "欧思科光电"))
      (libsource (lib "easyedapro") (part "SK9822-EC20"))
    )
    (comp (ref "LED101")
      (value "SK9822-EC20")
      (footprint "easyedapro:LED-SMD_6P-L2.0-W2.0-P0.80-TL")
      (description "Wavelength:620nm~625nm；460nm~470nm；520nm~530nm Operating Temperature:-40°C~+80°C")
      (fields (field (name "Manufacturer") "欧思科光电"))
      (libsource (lib "easyedapro") (part "SK9822-EC20"))
    )
    (comp (ref "LED102")
      (value "SK9822-EC20")
      (footprint "easyedapro:LED-SMD_6P-L2.0-W2.0-P0.80-TL")
      (description "Wavelength:620nm~625nm；460nm~470nm；520nm~530nm Operating Temperature:-40°C~+80°C")
      (fields (field (name "Manufacturer") "欧思科光电"))
      (libsource (lib "easyedapro") (part "SK9822-EC20"))
    )
    (comp (ref "LED103")
      (value "SK9822-EC20")
      (footprint "easyedapro:LED-SMD_6P-L2.0-W2.0-P0.80-TL")
      (description "Wavelength:620nm~625nm；460nm~470nm；520nm~530nm Operating Temperature:-40°C~+80°C")
      (fields (field (name "Manufacturer") "欧思科光电"))
      (libsource (lib "easyedapro") (part "SK9822-EC20"))
    )
    (comp (ref "LED104")
      (value "SK9822-EC20")
      (footprint "easyedapro:LED-SMD_6P-L2.0-W2.0-P0.80-TL")
      (description "Wavelength:620nm~625nm；460nm~470nm；520nm~530nm Operating Temperature:-40°C~+80°C")
      (fields (field (name "Manufacturer") "欧思科光电"))
      (libsource (lib "easyedapro") (part "SK9822-EC20"))
    )
    (comp (ref "LED105")
      (value "SK9822-EC20")
      (footprint "easyedapro:LED-SMD_6P-L2.0-W2.0-P0.80-TL")
      (description "Wavelength:620nm~625nm；460nm~470nm；520nm~530nm Operating Temperature:-40°C~+80°C")
      (fields (field (name "Manufacturer") "欧思科光电"))
      (libsource (lib "easyedapro") (part "SK9822-EC20"))
    )
    (comp (ref "LED106")
      (value "SK9822-EC20")
      (footprint "easyedapro:LED-SMD_6P-L2.0-W2.0-P0.80-TL")
      (description "Wavelength:620nm~625nm；460nm~470nm；520nm~530nm Operating Temperature:-40°C~+80°C")
      (fields (field (name "Manufacturer") "欧思科光电"))
      (libsource (lib "easyedapro") (part "SK9822-EC20"))
    )
    (comp (ref "LED107")
      (value "SK9822-EC20")
      (footprint "easyedapro:LED-SMD_6P-L2.0-W2.0-P0.80-TL")
      (description "Wavelength:620nm~625nm；460nm~470nm；520nm~530nm Operating Temperature:-40°C~+80°C")
      (fields (field (name "Manufacturer") "欧思科光电"))
      (libsource (lib "easyedapro") (part "SK9822-EC20"))
    )
    (comp (ref "LED108")
      (value "SK9822-EC20")
      (footprint "easyedapro:LED-SMD_6P-L2.0-W2.0-P0.80-TL")
      (description "Wavelength:620nm~625nm；460nm~470nm；520nm~530nm Operating Temperature:-40°C~+80°C")
      (fields (field (name "Manufacturer") "欧思科光电"))
      (libsource (lib "easyedapro") (part "SK9822-EC20"))
    )
    (comp (ref "LED109")
      (value "SK9822-EC20")
      (footprint "easyedapro:LED-SMD_6P-L2.0-W2.0-P0.80-TL")
      (description "Wavelength:620nm~625nm；460nm~470nm；520nm~530nm Operating Temperature:-40°C~+80°C")
      (fields (field (name "Manufacturer") "欧思科光电"))
      (libsource (lib "easyedapro") (part "SK9822-EC20"))
    )
    (comp (ref "LED110")
      (value "SK9822-EC20")
      (footprint "easyedapro:LED-SMD_6P-L2.0-W2.0-P0.80-TL")
      (description "Wavelength:620nm~625nm；460nm~470nm；520nm~530nm Operating Temperature:-40°C~+80°C")
      (fields (field (name "Manufacturer") "欧思科光电"))
      (libsource (lib "easyedapro") (part "SK9822-EC20"))
    )
    (comp (ref "LED111")
      (value "SK9822-EC20")
      (footprint "easyedapro:LED-SMD_6P-L2.0-W2.0-P0.80-TL")
      (description "Wavelength:620nm~625nm；460nm~470nm；520nm~530nm Operating Temperature:-40°C~+80°C")
      (fields (field (name "Manufacturer") "欧思科光电"))
      (libsource (lib "easyedapro") (part "SK9822-EC20"))
    )
    (comp (ref "LED112")
      (value "SK9822-EC20")
      (footprint "easyedapro:LED-SMD_6P-L2.0-W2.0-P0.80-TL")
      (description "Wavelength:620nm~625nm；460nm~470nm；520nm~530nm Operating Temperature:-40°C~+80°C")
      (fields (field (name "Manufacturer") "欧思科光电"))
      (libsource (lib "easyedapro") (part "SK9822-EC20"))
    )
    (comp (ref "LED113")
      (value "SK9822-EC20")
      (footprint "easyedapro:LED-SMD_6P-L2.0-W2.0-P0.80-TL")
      (description "Wavelength:620nm~625nm；460nm~470nm；520nm~530nm Operating Temperature:-40°C~+80°C")
      (fields (field (name "Manufacturer") "欧思科光电"))
      (libsource (lib "easyedapro") (part "SK9822-EC20"))
    )
    (comp (ref "LED114")
      (value "SK9822-EC20")
      (footprint "easyedapro:LED-SMD_6P-L2.0-W2.0-P0.80-TL")
      (description "Wavelength:620nm~625nm；460nm~470nm；520nm~530nm Operating Temperature:-40°C~+80°C")
      (fields (field (name "Manufacturer") "欧思科光电"))
      (libsource (lib "easyedapro") (part "SK9822-EC20"))
    )
    (comp (ref "LED115")
      (value "SK9822-EC20")
      (footprint "easyedapro:LED-SMD_6P-L2.0-W2.0-P0.80-TL")
      (description "Wavelength:620nm~625nm；460nm~470nm；520nm~530nm Operating Temperature:-40°C~+80°C")
      (fields (field (name "Manufacturer") "欧思科光电"))
      (libsource (lib "easyedapro") (part "SK9822-EC20"))
    )
    (comp (ref "LED116")
      (value "SK9822-EC20")
      (footprint "easyedapro:LED-SMD_6P-L2.0-W2.0-P0.80-TL")
      (description "Wavelength:620nm~625nm；460nm~470nm；520nm~530nm Operating Temperature:-40°C~+80°C")
      (fields (field (name "Manufacturer") "欧思科光电"))
      (libsource (lib "easyedapro") (part "SK9822-EC20"))
    )
    (comp (ref "LED117")
      (value "SK9822-EC20")
      (footprint "easyedapro:LED-SMD_6P-L2.0-W2.0-P0.80-TL")
      (description "Wavelength:620nm~625nm；460nm~470nm；520nm~530nm Operating Temperature:-40°C~+80°C")
      (fields (field (name "Manufacturer") "欧思科光电"))
      (libsource (lib "easyedapro") (part "SK9822-EC20"))
    )
    (comp (ref "LED118")
      (value "SK9822-EC20")
      (footprint "easyedapro:LED-SMD_6P-L2.0-W2.0-P0.80-TL")
      (description "Wavelength:620nm~625nm；460nm~470nm；520nm~530nm Operating Temperature:-40°C~+80°C")
      (fields (field (name "Manufacturer") "欧思科光电"))
      (libsource (lib "easyedapro") (part "SK9822-EC20"))
    )
    (comp (ref "LED119")
      (value "SK9822-EC20")
      (footprint "easyedapro:LED-SMD_6P-L2.0-W2.0-P0.80-TL")
      (description "Wavelength:620nm~625nm；460nm~470nm；520nm~530nm Operating Temperature:-40°C~+80°C")
      (fields (field (name "Manufacturer") "欧思科光电"))
      (libsource (lib "easyedapro") (part "SK9822-EC20"))
    )
    (comp (ref "LED120")
      (value "SK9822-EC20")
      (footprint "easyedapro:LED-SMD_6P-L2.0-W2.0-P0.80-TL")
      (description "Wavelength:620nm~625nm；460nm~470nm；520nm~530nm Operating Temperature:-40°C~+80°C")
      (fields (field (name "Manufacturer") "欧思科光电"))
      (libsource (lib "easyedapro") (part "SK9822-EC20"))
    )
    (comp (ref "LED121")
      (value "SK9822-EC20")
      (footprint "easyedapro:LED-SMD_6P-L2.0-W2.0-P0.80-TL")
      (description "Wavelength:620nm~625nm；460nm~470nm；520nm~530nm Operating Temperature:-40°C~+80°C")
      (fields (field (name "Manufacturer") "欧思科光电"))
      (libsource (lib "easyedapro") (part "SK9822-EC20"))
    )
    (comp (ref "LED122")
      (value "SK9822-EC20")
      (footprint "easyedapro:LED-SMD_6P-L2.0-W2.0-P0.80-TL")
      (description "Wavelength:620nm~625nm；460nm~470nm；520nm~530nm Operating Temperature:-40°C~+80°C")
      (fields (field (name "Manufacturer") "欧思科光电"))
      (libsource (lib "easyedapro") (part "SK9822-EC20"))
    )
    (comp (ref "LED123")
      (value "SK9822-EC20")
      (footprint "easyedapro:LED-SMD_6P-L2.0-W2.0-P0.80-TL")
      (description "Wavelength:620nm~625nm；460nm~470nm；520nm~530nm Operating Temperature:-40°C~+80°C")
      (fields (field (name "Manufacturer") "欧思科光电"))
      (libsource (lib "easyedapro") (part "SK9822-EC20"))
    )
    (comp (ref "LED124")
      (value "SK9822-EC20")
      (footprint "easyedapro:LED-SMD_6P-L2.0-W2.0-P0.80-TL")
      (description "Wavelength:620nm~625nm；460nm~470nm；520nm~530nm Operating Temperature:-40°C~+80°C")
      (fields (field (name "Manufacturer") "欧思科光电"))
      (libsource (lib "easyedapro") (part "SK9822-EC20"))
    )
    (comp (ref "LED125")
      (value "SK9822-EC20")
      (footprint "easyedapro:LED-SMD_6P-L2.0-W2.0-P0.80-TL")
      (description "Wavelength:620nm~625nm；460nm~470nm；520nm~530nm Operating Temperature:-40°C~+80°C")
      (fields (field (name "Manufacturer") "欧思科光电"))
      (libsource (lib "easyedapro") (part "SK9822-EC20"))
    )
    (comp (ref "LED126")
      (value "SK9822-EC20")
      (footprint "easyedapro:LED-SMD_6P-L2.0-W2.0-P0.80-TL")
      (description "Wavelength:620nm~625nm；460nm~470nm；520nm~530nm Operating Temperature:-40°C~+80°C")
      (fields (field (name "Manufacturer") "欧思科光电"))
      (libsource (lib "easyedapro") (part "SK9822-EC20"))
    )
    (comp (ref "LED127")
      (value "SK9822-EC20")
      (footprint "easyedapro:LED-SMD_6P-L2.0-W2.0-P0.80-TL")
      (description "Wavelength:620nm~625nm；460nm~470nm；520nm~530nm Operating Temperature:-40°C~+80°C")
      (fields (field (name "Manufacturer") "欧思科光电"))
      (libsource (lib "easyedapro") (part "SK9822-EC20"))
    )
    (comp (ref "LED128")
      (value "SK9822-EC20")
      (footprint "easyedapro:LED-SMD_6P-L2.0-W2.0-P0.80-TL")
      (description "Wavelength:620nm~625nm；460nm~470nm；520nm~530nm Operating Temperature:-40°C~+80°C")
      (fields (field (name "Manufacturer") "欧思科光电"))
      (libsource (lib "easyedapro") (part "SK9822-EC20"))
    )
    (comp (ref "LED129")
      (value "SK9822-EC20")
      (footprint "easyedapro:LED-SMD_6P-L2.0-W2.0-P0.80-TL")
      (description "Wavelength:620nm~625nm；460nm~470nm；520nm~530nm Operating Temperature:-40°C~+80°C")
      (fields (field (name "Manufacturer") "欧思科光电"))
      (libsource (lib "easyedapro") (part "SK9822-EC20"))
    )
    (comp (ref "LED130")
      (value "SK9822-EC20")
      (footprint "easyedapro:LED-SMD_6P-L2.0-W2.0-P0.80-TL")
      (description "Wavelength:620nm~625nm；460nm~470nm；520nm~530nm Operating Temperature:-40°C~+80°C")
      (fields (field (name "Manufacturer") "欧思科光电"))
      (libsource (lib "easyedapro") (part "SK9822-EC20"))
    )
    (comp (ref "LED131")
      (value "SK9822-EC20")
      (footprint "easyedapro:LED-SMD_6P-L2.0-W2.0-P0.80-TL")
      (description "Wavelength:620nm~625nm；460nm~470nm；520nm~530nm Operating Temperature:-40°C~+80°C")
      (fields (field (name "Manufacturer") "欧思科光电"))
      (libsource (lib "easyedapro") (part "SK9822-EC20"))
    )
    (comp (ref "LED132")
      (value "SK9822-EC20")
      (footprint "easyedapro:LED-SMD_6P-L2.0-W2.0-P0.80-TL")
      (description "Wavelength:620nm~625nm；460nm~470nm；520nm~530nm Operating Temperature:-40°C~+80°C")
      (fields (field (name "Manufacturer") "欧思科光电"))
      (libsource (lib "easyedapro") (part "SK9822-EC20"))
    )
    (comp (ref "LED133")
      (value "SK9822-EC20")
      (footprint "easyedapro:LED-SMD_6P-L2.0-W2.0-P0.80-TL")
      (description "Wavelength:620nm~625nm；460nm~470nm；520nm~530nm Operating Temperature:-40°C~+80°C")
      (fields (field (name "Manufacturer") "欧思科光电"))
      (libsource (lib "easyedapro") (part "SK9822-EC20"))
    )
    (comp (ref "LED134")
      (value "SK9822-EC20")
      (footprint "easyedapro:LED-SMD_6P-L2.0-W2.0-P0.80-TL")
      (description "Wavelength:620nm~625nm；460nm~470nm；520nm~530nm Operating Temperature:-40°C~+80°C")
      (fields (field (name "Manufacturer") "欧思科光电"))
      (libsource (lib "easyedapro") (part "SK9822-EC20"))
    )
    (comp (ref "LED135")
      (value "SK9822-EC20")
      (footprint "easyedapro:LED-SMD_6P-L2.0-W2.0-P0.80-TL")
      (description "Wavelength:620nm~625nm；460nm~470nm；520nm~530nm Operating Temperature:-40°C~+80°C")
      (fields (field (name "Manufacturer") "欧思科光电"))
      (libsource (lib "easyedapro") (part "SK9822-EC20"))
    )
    (comp (ref "LED136")
      (value "SK9822-EC20")
      (footprint "easyedapro:LED-SMD_6P-L2.0-W2.0-P0.80-TL")
      (description "Wavelength:620nm~625nm；460nm~470nm；520nm~530nm Operating Temperature:-40°C~+80°C")
      (fields (field (name "Manufacturer") "欧思科光电"))
      (libsource (lib "easyedapro") (part "SK9822-EC20"))
    )
    (comp (ref "LED137")
      (value "SK9822-EC20")
      (footprint "easyedapro:LED-SMD_6P-L2.0-W2.0-P0.80-TL")
      (description "Wavelength:620nm~625nm；460nm~470nm；520nm~530nm Operating Temperature:-40°C~+80°C")
      (fields (field (name "Manufacturer") "欧思科光电"))
      (libsource (lib "easyedapro") (part "SK9822-EC20"))
    )
    (comp (ref "LED138")
      (value "SK9822-EC20")
      (footprint "easyedapro:LED-SMD_6P-L2.0-W2.0-P0.80-TL")
      (description "Wavelength:620nm~625nm；460nm~470nm；520nm~530nm Operating Temperature:-40°C~+80°C")
      (fields (field (name "Manufacturer") "欧思科光电"))
      (libsource (lib "easyedapro") (part "SK9822-EC20"))
    )
    (comp (ref "LED139")
      (value "SK9822-EC20")
      (footprint "easyedapro:LED-SMD_6P-L2.0-W2.0-P0.80-TL")
      (description "Wavelength:620nm~625nm；460nm~470nm；520nm~530nm Operating Temperature:-40°C~+80°C")
      (fields (field (name "Manufacturer") "欧思科光电"))
      (libsource (lib "easyedapro") (part "SK9822-EC20"))
    )
    (comp (ref "LED140")
      (value "SK9822-EC20")
      (footprint "easyedapro:LED-SMD_6P-L2.0-W2.0-P0.80-TL")
      (description "Wavelength:620nm~625nm；460nm~470nm；520nm~530nm Operating Temperature:-40°C~+80°C")
      (fields (field (name "Manufacturer") "欧思科光电"))
      (libsource (lib "easyedapro") (part "SK9822-EC20"))
    )
    (comp (ref "LED141")
      (value "SK9822-EC20")
      (footprint "easyedapro:LED-SMD_6P-L2.0-W2.0-P0.80-TL")
      (description "Wavelength:620nm~625nm；460nm~470nm；520nm~530nm Operating Temperature:-40°C~+80°C")
      (fields (field (name "Manufacturer") "欧思科光电"))
      (libsource (lib "easyedapro") (part "SK9822-EC20"))
    )
    (comp (ref "LED142")
      (value "SK9822-EC20")
      (footprint "easyedapro:LED-SMD_6P-L2.0-W2.0-P0.80-TL")
      (description "Wavelength:620nm~625nm；460nm~470nm；520nm~530nm Operating Temperature:-40°C~+80°C")
      (fields (field (name "Manufacturer") "欧思科光电"))
      (libsource (lib "easyedapro") (part "SK9822-EC20"))
    )
    (comp (ref "LED143")
      (value "SK9822-EC20")
      (footprint "easyedapro:LED-SMD_6P-L2.0-W2.0-P0.80-TL")
      (description "Wavelength:620nm~625nm；460nm~470nm；520nm~530nm Operating Temperature:-40°C~+80°C")
      (fields (field (name "Manufacturer") "欧思科光电"))
      (libsource (lib "easyedapro") (part "SK9822-EC20"))
    )
    (comp (ref "LED144")
      (value "SK9822-EC20")
      (footprint "easyedapro:LED-SMD_6P-L2.0-W2.0-P0.80-TL")
      (description "Wavelength:620nm~625nm；460nm~470nm；520nm~530nm Operating Temperature:-40°C~+80°C")
      (fields (field (name "Manufacturer") "欧思科光电"))
      (libsource (lib "easyedapro") (part "SK9822-EC20"))
    )
    (comp (ref "LED145")
      (value "SK9822-EC20")
      (footprint "easyedapro:LED-SMD_6P-L2.0-W2.0-P0.80-TL")
      (description "Wavelength:620nm~625nm；460nm~470nm；520nm~530nm Operating Temperature:-40°C~+80°C")
      (fields (field (name "Manufacturer") "欧思科光电"))
      (libsource (lib "easyedapro") (part "SK9822-EC20"))
    )
    (comp (ref "LED146")
      (value "SK9822-EC20")
      (footprint "easyedapro:LED-SMD_6P-L2.0-W2.0-P0.80-TL")
      (description "Wavelength:620nm~625nm；460nm~470nm；520nm~530nm Operating Temperature:-40°C~+80°C")
      (fields (field (name "Manufacturer") "欧思科光电"))
      (libsource (lib "easyedapro") (part "SK9822-EC20"))
    )
    (comp (ref "LED147")
      (value "SK9822-EC20")
      (footprint "easyedapro:LED-SMD_6P-L2.0-W2.0-P0.80-TL")
      (description "Wavelength:620nm~625nm；460nm~470nm；520nm~530nm Operating Temperature:-40°C~+80°C")
      (fields (field (name "Manufacturer") "欧思科光电"))
      (libsource (lib "easyedapro") (part "SK9822-EC20"))
    )
    (comp (ref "LED148")
      (value "SK9822-EC20")
      (footprint "easyedapro:LED-SMD_6P-L2.0-W2.0-P0.80-TL")
      (description "Wavelength:620nm~625nm；460nm~470nm；520nm~530nm Operating Temperature:-40°C~+80°C")
      (fields (field (name "Manufacturer") "欧思科光电"))
      (libsource (lib "easyedapro") (part "SK9822-EC20"))
    )
    (comp (ref "LED149")
      (value "SK9822-EC20")
      (footprint "easyedapro:LED-SMD_6P-L2.0-W2.0-P0.80-TL")
      (description "Wavelength:620nm~625nm；460nm~470nm；520nm~530nm Operating Temperature:-40°C~+80°C")
      (fields (field (name "Manufacturer") "欧思科光电"))
      (libsource (lib "easyedapro") (part "SK9822-EC20"))
    )
    (comp (ref "LED150")
      (value "SK9822-EC20")
      (footprint "easyedapro:LED-SMD_6P-L2.0-W2.0-P0.80-TL")
      (description "Wavelength:620nm~625nm；460nm~470nm；520nm~530nm Operating Temperature:-40°C~+80°C")
      (fields (field (name "Manufacturer") "欧思科光电"))
      (libsource (lib "easyedapro") (part "SK9822-EC20"))
    )
    (comp (ref "LED151")
      (value "SK9822-EC20")
      (footprint "easyedapro:LED-SMD_6P-L2.0-W2.0-P0.80-TL")
      (description "Wavelength:620nm~625nm；460nm~470nm；520nm~530nm Operating Temperature:-40°C~+80°C")
      (fields (field (name "Manufacturer") "欧思科光电"))
      (libsource (lib "easyedapro") (part "SK9822-EC20"))
    )
    (comp (ref "LED152")
      (value "SK9822-EC20")
      (footprint "easyedapro:LED-SMD_6P-L2.0-W2.0-P0.80-TL")
      (description "Wavelength:620nm~625nm；460nm~470nm；520nm~530nm Operating Temperature:-40°C~+80°C")
      (fields (field (name "Manufacturer") "欧思科光电"))
      (libsource (lib "easyedapro") (part "SK9822-EC20"))
    )
    (comp (ref "LED153")
      (value "SK9822-EC20")
      (footprint "easyedapro:LED-SMD_6P-L2.0-W2.0-P0.80-TL")
      (description "Wavelength:620nm~625nm；460nm~470nm；520nm~530nm Operating Temperature:-40°C~+80°C")
      (fields (field (name "Manufacturer") "欧思科光电"))
      (libsource (lib "easyedapro") (part "SK9822-EC20"))
    )
    (comp (ref "LED154")
      (value "SK9822-EC20")
      (footprint "easyedapro:LED-SMD_6P-L2.0-W2.0-P0.80-TL")
      (description "Wavelength:620nm~625nm；460nm~470nm；520nm~530nm Operating Temperature:-40°C~+80°C")
      (fields (field (name "Manufacturer") "欧思科光电"))
      (libsource (lib "easyedapro") (part "SK9822-EC20"))
    )
    (comp (ref "LED155")
      (value "SK9822-EC20")
      (footprint "easyedapro:LED-SMD_6P-L2.0-W2.0-P0.80-TL")
      (description "Wavelength:620nm~625nm；460nm~470nm；520nm~530nm Operating Temperature:-40°C~+80°C")
      (fields (field (name "Manufacturer") "欧思科光电"))
      (libsource (lib "easyedapro") (part "SK9822-EC20"))
    )
    (comp (ref "LED156")
      (value "SK9822-EC20")
      (footprint "easyedapro:LED-SMD_6P-L2.0-W2.0-P0.80-TL")
      (description "Wavelength:620nm~625nm；460nm~470nm；520nm~530nm Operating Temperature:-40°C~+80°C")
      (fields (field (name "Manufacturer") "欧思科光电"))
      (libsource (lib "easyedapro") (part "SK9822-EC20"))
    )
    (comp (ref "LED157")
      (value "SK9822-EC20")
      (footprint "easyedapro:LED-SMD_6P-L2.0-W2.0-P0.80-TL")
      (description "Wavelength:620nm~625nm；460nm~470nm；520nm~530nm Operating Temperature:-40°C~+80°C")
      (fields (field (name "Manufacturer") "欧思科光电"))
      (libsource (lib "easyedapro") (part "SK9822-EC20"))
    )
    (comp (ref "LED158")
      (value "SK9822-EC20")
      (footprint "easyedapro:LED-SMD_6P-L2.0-W2.0-P0.80-TL")
      (description "Wavelength:620nm~625nm；460nm~470nm；520nm~530nm Operating Temperature:-40°C~+80°C")
      (fields (field (name "Manufacturer") "欧思科光电"))
      (libsource (lib "easyedapro") (part "SK9822-EC20"))
    )
    (comp (ref "LED159")
      (value "SK9822-EC20")
      (footprint "easyedapro:LED-SMD_6P-L2.0-W2.0-P0.80-TL")
      (description "Wavelength:620nm~625nm；460nm~470nm；520nm~530nm Operating Temperature:-40°C~+80°C")
      (fields (field (name "Manufacturer") "欧思科光电"))
      (libsource (lib "easyedapro") (part "SK9822-EC20"))
    )
    (comp (ref "LED160")
      (value "SK9822-EC20")
      (footprint "easyedapro:LED-SMD_6P-L2.0-W2.0-P0.80-TL")
      (description "Wavelength:620nm~625nm；460nm~470nm；520nm~530nm Operating Temperature:-40°C~+80°C")
      (fields (field (name "Manufacturer") "欧思科光电"))
      (libsource (lib "easyedapro") (part "SK9822-EC20"))
    )
    (comp (ref "LED161")
      (value "SK9822-EC20")
      (footprint "easyedapro:LED-SMD_6P-L2.0-W2.0-P0.80-TL")
      (description "Wavelength:620nm~625nm；460nm~470nm；520nm~530nm Operating Temperature:-40°C~+80°C")
      (fields (field (name "Manufacturer") "欧思科光电"))
      (libsource (lib "easyedapro") (part "SK9822-EC20"))
    )
    (comp (ref "LED162")
      (value "SK9822-EC20")
      (footprint "easyedapro:LED-SMD_6P-L2.0-W2.0-P0.80-TL")
      (description "Wavelength:620nm~625nm；460nm~470nm；520nm~530nm Operating Temperature:-40°C~+80°C")
      (fields (field (name "Manufacturer") "欧思科光电"))
      (libsource (lib "easyedapro") (part "SK9822-EC20"))
    )
    (comp (ref "LED163")
      (value "SK9822-EC20")
      (footprint "easyedapro:LED-SMD_6P-L2.0-W2.0-P0.80-TL")
      (description "Wavelength:620nm~625nm；460nm~470nm；520nm~530nm Operating Temperature:-40°C~+80°C")
      (fields (field (name "Manufacturer") "欧思科光电"))
      (libsource (lib "easyedapro") (part "SK9822-EC20"))
    )
    (comp (ref "LED164")
      (value "SK9822-EC20")
      (footprint "easyedapro:LED-SMD_6P-L2.0-W2.0-P0.80-TL")
      (description "Wavelength:620nm~625nm；460nm~470nm；520nm~530nm Operating Temperature:-40°C~+80°C")
      (fields (field (name "Manufacturer") "欧思科光电"))
      (libsource (lib "easyedapro") (part "SK9822-EC20"))
    )
    (comp (ref "LED165")
      (value "SK9822-EC20")
      (footprint "easyedapro:LED-SMD_6P-L2.0-W2.0-P0.80-TL")
      (description "Wavelength:620nm~625nm；460nm~470nm；520nm~530nm Operating Temperature:-40°C~+80°C")
      (fields (field (name "Manufacturer") "欧思科光电"))
      (libsource (lib "easyedapro") (part "SK9822-EC20"))
    )
    (comp (ref "LED166")
      (value "SK9822-EC20")
      (footprint "easyedapro:LED-SMD_6P-L2.0-W2.0-P0.80-TL")
      (description "Wavelength:620nm~625nm；460nm~470nm；520nm~530nm Operating Temperature:-40°C~+80°C")
      (fields (field (name "Manufacturer") "欧思科光电"))
      (libsource (lib "easyedapro") (part "SK9822-EC20"))
    )
    (comp (ref "LED167")
      (value "SK9822-EC20")
      (footprint "easyedapro:LED-SMD_6P-L2.0-W2.0-P0.80-TL")
      (description "Wavelength:620nm~625nm；460nm~470nm；520nm~530nm Operating Temperature:-40°C~+80°C")
      (fields (field (name "Manufacturer") "欧思科光电"))
      (libsource (lib "easyedapro") (part "SK9822-EC20"))
    )
    (comp (ref "LED168")
      (value "SK9822-EC20")
      (footprint "easyedapro:LED-SMD_6P-L2.0-W2.0-P0.80-TL")
      (description "Wavelength:620nm~625nm；460nm~470nm；520nm~530nm Operating Temperature:-40°C~+80°C")
      (fields (field (name "Manufacturer") "欧思科光电"))
      (libsource (lib "easyedapro") (part "SK9822-EC20"))
    )
    (comp (ref "LED169")
      (value "SK9822-EC20")
      (footprint "easyedapro:LED-SMD_6P-L2.0-W2.0-P0.80-TL")
      (description "Wavelength:620nm~625nm；460nm~470nm；520nm~530nm Operating Temperature:-40°C~+80°C")
      (fields (field (name "Manufacturer") "欧思科光电"))
      (libsource (lib "easyedapro") (part "SK9822-EC20"))
    )
    (comp (ref "LED170")
      (value "SK9822-EC20")
      (footprint "easyedapro:LED-SMD_6P-L2.0-W2.0-P0.80-TL")
      (description "Wavelength:620nm~625nm；460nm~470nm；520nm~530nm Operating Temperature:-40°C~+80°C")
      (fields (field (name "Manufacturer") "欧思科光电"))
      (libsource (lib "easyedapro") (part "SK9822-EC20"))
    )
    (comp (ref "LED171")
      (value "SK9822-EC20")
      (footprint "easyedapro:LED-SMD_6P-L2.0-W2.0-P0.80-TL")
      (description "Wavelength:620nm~625nm；460nm~470nm；520nm~530nm Operating Temperature:-40°C~+80°C")
      (fields (field (name "Manufacturer") "欧思科光电"))
      (libsource (lib "easyedapro") (part "SK9822-EC20"))
    )
    (comp (ref "LED172")
      (value "SK9822-EC20")
      (footprint "easyedapro:LED-SMD_6P-L2.0-W2.0-P0.80-TL")
      (description "Wavelength:620nm~625nm；460nm~470nm；520nm~530nm Operating Temperature:-40°C~+80°C")
      (fields (field (name "Manufacturer") "欧思科光电"))
      (libsource (lib "easyedapro") (part "SK9822-EC20"))
    )
    (comp (ref "LED173")
      (value "SK9822-EC20")
      (footprint "easyedapro:LED-SMD_6P-L2.0-W2.0-P0.80-TL")
      (description "Wavelength:620nm~625nm；460nm~470nm；520nm~530nm Operating Temperature:-40°C~+80°C")
      (fields (field (name "Manufacturer") "欧思科光电"))
      (libsource (lib "easyedapro") (part "SK9822-EC20"))
    )
    (comp (ref "LED174")
      (value "SK9822-EC20")
      (footprint "easyedapro:LED-SMD_6P-L2.0-W2.0-P0.80-TL")
      (description "Wavelength:620nm~625nm；460nm~470nm；520nm~530nm Operating Temperature:-40°C~+80°C")
      (fields (field (name "Manufacturer") "欧思科光电"))
      (libsource (lib "easyedapro") (part "SK9822-EC20"))
    )
    (comp (ref "LED175")
      (value "SK9822-EC20")
      (footprint "easyedapro:LED-SMD_6P-L2.0-W2.0-P0.80-TL")
      (description "Wavelength:620nm~625nm；460nm~470nm；520nm~530nm Operating Temperature:-40°C~+80°C")
      (fields (field (name "Manufacturer") "欧思科光电"))
      (libsource (lib "easyedapro") (part "SK9822-EC20"))
    )
    (comp (ref "LED176")
      (value "SK9822-EC20")
      (footprint "easyedapro:LED-SMD_6P-L2.0-W2.0-P0.80-TL")
      (description "Wavelength:620nm~625nm；460nm~470nm；520nm~530nm Operating Temperature:-40°C~+80°C")
      (fields (field (name "Manufacturer") "欧思科光电"))
      (libsource (lib "easyedapro") (part "SK9822-EC20"))
    )
    (comp (ref "LED177")
      (value "SK9822-EC20")
      (footprint "easyedapro:LED-SMD_6P-L2.0-W2.0-P0.80-TL")
      (description "Wavelength:620nm~625nm；460nm~470nm；520nm~530nm Operating Temperature:-40°C~+80°C")
      (fields (field (name "Manufacturer") "欧思科光电"))
      (libsource (lib "easyedapro") (part "SK9822-EC20"))
    )
    (comp (ref "LED178")
      (value "SK9822-EC20")
      (footprint "easyedapro:LED-SMD_6P-L2.0-W2.0-P0.80-TL")
      (description "Wavelength:620nm~625nm；460nm~470nm；520nm~530nm Operating Temperature:-40°C~+80°C")
      (fields (field (name "Manufacturer") "欧思科光电"))
      (libsource (lib "easyedapro") (part "SK9822-EC20"))
    )
    (comp (ref "LED179")
      (value "SK9822-EC20")
      (footprint "easyedapro:LED-SMD_6P-L2.0-W2.0-P0.80-TL")
      (description "Wavelength:620nm~625nm；460nm~470nm；520nm~530nm Operating Temperature:-40°C~+80°C")
      (fields (field (name "Manufacturer") "欧思科光电"))
      (libsource (lib "easyedapro") (part "SK9822-EC20"))
    )
    (comp (ref "LED180")
      (value "SK9822-EC20")
      (footprint "easyedapro:LED-SMD_6P-L2.0-W2.0-P0.80-TL")
      (description "Wavelength:620nm~625nm；460nm~470nm；520nm~530nm Operating Temperature:-40°C~+80°C")
      (fields (field (name "Manufacturer") "欧思科光电"))
      (libsource (lib "easyedapro") (part "SK9822-EC20"))
    )
    (comp (ref "LED181")
      (value "SK9822-EC20")
      (footprint "easyedapro:LED-SMD_6P-L2.0-W2.0-P0.80-TL")
      (description "Wavelength:620nm~625nm；460nm~470nm；520nm~530nm Operating Temperature:-40°C~+80°C")
      (fields (field (name "Manufacturer") "欧思科光电"))
      (libsource (lib "easyedapro") (part "SK9822-EC20"))
    )
    (comp (ref "LED182")
      (value "SK9822-EC20")
      (footprint "easyedapro:LED-SMD_6P-L2.0-W2.0-P0.80-TL")
      (description "Wavelength:620nm~625nm；460nm~470nm；520nm~530nm Operating Temperature:-40°C~+80°C")
      (fields (field (name "Manufacturer") "欧思科光电"))
      (libsource (lib "easyedapro") (part "SK9822-EC20"))
    )
    (comp (ref "LED183")
      (value "SK9822-EC20")
      (footprint "easyedapro:LED-SMD_6P-L2.0-W2.0-P0.80-TL")
      (description "Wavelength:620nm~625nm；460nm~470nm；520nm~530nm Operating Temperature:-40°C~+80°C")
      (fields (field (name "Manufacturer") "欧思科光电"))
      (libsource (lib "easyedapro") (part "SK9822-EC20"))
    )
    (comp (ref "LED184")
      (value "SK9822-EC20")
      (footprint "easyedapro:LED-SMD_6P-L2.0-W2.0-P0.80-TL")
      (description "Wavelength:620nm~625nm；460nm~470nm；520nm~530nm Operating Temperature:-40°C~+80°C")
      (fields (field (name "Manufacturer") "欧思科光电"))
      (libsource (lib "easyedapro") (part "SK9822-EC20"))
    )
    (comp (ref "LED185")
      (value "SK9822-EC20")
      (footprint "easyedapro:LED-SMD_6P-L2.0-W2.0-P0.80-TL")
      (description "Wavelength:620nm~625nm；460nm~470nm；520nm~530nm Operating Temperature:-40°C~+80°C")
      (fields (field (name "Manufacturer") "欧思科光电"))
      (libsource (lib "easyedapro") (part "SK9822-EC20"))
    )
    (comp (ref "LED186")
      (value "SK9822-EC20")
      (footprint "easyedapro:LED-SMD_6P-L2.0-W2.0-P0.80-TL")
      (description "Wavelength:620nm~625nm；460nm~470nm；520nm~530nm Operating Temperature:-40°C~+80°C")
      (fields (field (name "Manufacturer") "欧思科光电"))
      (libsource (lib "easyedapro") (part "SK9822-EC20"))
    )
    (comp (ref "LED187")
      (value "SK9822-EC20")
      (footprint "easyedapro:LED-SMD_6P-L2.0-W2.0-P0.80-TL")
      (description "Wavelength:620nm~625nm；460nm~470nm；520nm~530nm Operating Temperature:-40°C~+80°C")
      (fields (field (name "Manufacturer") "欧思科光电"))
      (libsource (lib "easyedapro") (part "SK9822-EC20"))
    )
    (comp (ref "LED188")
      (value "SK9822-EC20")
      (footprint "easyedapro:LED-SMD_6P-L2.0-W2.0-P0.80-TL")
      (description "Wavelength:620nm~625nm；460nm~470nm；520nm~530nm Operating Temperature:-40°C~+80°C")
      (fields (field (name "Manufacturer") "欧思科光电"))
      (libsource (lib "easyedapro") (part "SK9822-EC20"))
    )
    (comp (ref "LED189")
      (value "SK9822-EC20")
      (footprint "easyedapro:LED-SMD_6P-L2.0-W2.0-P0.80-TL")
      (description "Wavelength:620nm~625nm；460nm~470nm；520nm~530nm Operating Temperature:-40°C~+80°C")
      (fields (field (name "Manufacturer") "欧思科光电"))
      (libsource (lib "easyedapro") (part "SK9822-EC20"))
    )
    (comp (ref "LED190")
      (value "SK9822-EC20")
      (footprint "easyedapro:LED-SMD_6P-L2.0-W2.0-P0.80-TL")
      (description "Wavelength:620nm~625nm；460nm~470nm；520nm~530nm Operating Temperature:-40°C~+80°C")
      (fields (field (name "Manufacturer") "欧思科光电"))
      (libsource (lib "easyedapro") (part "SK9822-EC20"))
    )
    (comp (ref "LED191")
      (value "SK9822-EC20")
      (footprint "easyedapro:LED-SMD_6P-L2.0-W2.0-P0.80-TL")
      (description "Wavelength:620nm~625nm；460nm~470nm；520nm~530nm Operating Temperature:-40°C~+80°C")
      (fields (field (name "Manufacturer") "欧思科光电"))
      (libsource (lib "easyedapro") (part "SK9822-EC20"))
    )
    (comp (ref "LED192")
      (value "SK9822-EC20")
      (footprint "easyedapro:LED-SMD_6P-L2.0-W2.0-P0.80-TL")
      (description "Wavelength:620nm~625nm；460nm~470nm；520nm~530nm Operating Temperature:-40°C~+80°C")
      (fields (field (name "Manufacturer") "欧思科光电"))
      (libsource (lib "easyedapro") (part "SK9822-EC20"))
    )
    (comp (ref "LED193")
      (value "SK9822-EC20")
      (footprint "easyedapro:LED-SMD_6P-L2.0-W2.0-P0.80-TL")
      (description "Wavelength:620nm~625nm；460nm~470nm；520nm~530nm Operating Temperature:-40°C~+80°C")
      (fields (field (name "Manufacturer") "欧思科光电"))
      (libsource (lib "easyedapro") (part "SK9822-EC20"))
    )
    (comp (ref "LED194")
      (value "SK9822-EC20")
      (footprint "easyedapro:LED-SMD_6P-L2.0-W2.0-P0.80-TL")
      (description "Wavelength:620nm~625nm；460nm~470nm；520nm~530nm Operating Temperature:-40°C~+80°C")
      (fields (field (name "Manufacturer") "欧思科光电"))
      (libsource (lib "easyedapro") (part "SK9822-EC20"))
    )
    (comp (ref "LED195")
      (value "SK9822-EC20")
      (footprint "easyedapro:LED-SMD_6P-L2.0-W2.0-P0.80-TL")
      (description "Wavelength:620nm~625nm；460nm~470nm；520nm~530nm Operating Temperature:-40°C~+80°C")
      (fields (field (name "Manufacturer") "欧思科光电"))
      (libsource (lib "easyedapro") (part "SK9822-EC20"))
    )
    (comp (ref "LED196")
      (value "SK9822-EC20")
      (footprint "easyedapro:LED-SMD_6P-L2.0-W2.0-P0.80-TL")
      (description "Wavelength:620nm~625nm；460nm~470nm；520nm~530nm Operating Temperature:-40°C~+80°C")
      (fields (field (name "Manufacturer") "欧思科光电"))
      (libsource (lib "easyedapro") (part "SK9822-EC20"))
    )
    (comp (ref "LED197")
      (value "SK9822-EC20")
      (footprint "easyedapro:LED-SMD_6P-L2.0-W2.0-P0.80-TL")
      (description "Wavelength:620nm~625nm；460nm~470nm；520nm~530nm Operating Temperature:-40°C~+80°C")
      (fields (field (name "Manufacturer") "欧思科光电"))
      (libsource (lib "easyedapro") (part "SK9822-EC20"))
    )
    (comp (ref "LED198")
      (value "SK9822-EC20")
      (footprint "easyedapro:LED-SMD_6P-L2.0-W2.0-P0.80-TL")
      (description "Wavelength:620nm~625nm；460nm~470nm；520nm~530nm Operating Temperature:-40°C~+80°C")
      (fields (field (name "Manufacturer") "欧思科光电"))
      (libsource (lib "easyedapro") (part "SK9822-EC20"))
    )
    (comp (ref "LED199")
      (value "SK9822-EC20")
      (footprint "easyedapro:LED-SMD_6P-L2.0-W2.0-P0.80-TL")
      (description "Wavelength:620nm~625nm；460nm~470nm；520nm~530nm Operating Temperature:-40°C~+80°C")
      (fields (field (name "Manufacturer") "欧思科光电"))
      (libsource (lib "easyedapro") (part "SK9822-EC20"))
    )
    (comp (ref "LED200")
      (value "SK9822-EC20")
      (footprint "easyedapro:LED-SMD_6P-L2.0-W2.0-P0.80-TL")
      (description "Wavelength:620nm~625nm；460nm~470nm；520nm~530nm Operating Temperature:-40°C~+80°C")
      (fields (field (name "Manufacturer") "欧思科光电"))
      (libsource (lib "easyedapro") (part "SK9822-EC20"))
    )
    (comp (ref "LED201")
      (value "SK9822-EC20")
      (footprint "easyedapro:LED-SMD_6P-L2.0-W2.0-P0.80-TL")
      (description "Wavelength:620nm~625nm；460nm~470nm；520nm~530nm Operating Temperature:-40°C~+80°C")
      (fields (field (name "Manufacturer") "欧思科光电"))
      (libsource (lib "easyedapro") (part "SK9822-EC20"))
    )
    (comp (ref "LED202")
      (value "SK9822-EC20")
      (footprint "easyedapro:LED-SMD_6P-L2.0-W2.0-P0.80-TL")
      (description "Wavelength:620nm~625nm；460nm~470nm；520nm~530nm Operating Temperature:-40°C~+80°C")
      (fields (field (name "Manufacturer") "欧思科光电"))
      (libsource (lib "easyedapro") (part "SK9822-EC20"))
    )
    (comp (ref "LED203")
      (value "SK9822-EC20")
      (footprint "easyedapro:LED-SMD_6P-L2.0-W2.0-P0.80-TL")
      (description "Wavelength:620nm~625nm；460nm~470nm；520nm~530nm Operating Temperature:-40°C~+80°C")
      (fields (field (name "Manufacturer") "欧思科光电"))
      (libsource (lib "easyedapro") (part "SK9822-EC20"))
    )
    (comp (ref "LED204")
      (value "SK9822-EC20")
      (footprint "easyedapro:LED-SMD_6P-L2.0-W2.0-P0.80-TL")
      (description "Wavelength:620nm~625nm；460nm~470nm；520nm~530nm Operating Temperature:-40°C~+80°C")
      (fields (field (name "Manufacturer") "欧思科光电"))
      (libsource (lib "easyedapro") (part "SK9822-EC20"))
    )
    (comp (ref "LED205")
      (value "SK9822-EC20")
      (footprint "easyedapro:LED-SMD_6P-L2.0-W2.0-P0.80-TL")
      (description "Wavelength:620nm~625nm；460nm~470nm；520nm~530nm Operating Temperature:-40°C~+80°C")
      (fields (field (name "Manufacturer") "欧思科光电"))
      (libsource (lib "easyedapro") (part "SK9822-EC20"))
    )
    (comp (ref "LED206")
      (value "SK9822-EC20")
      (footprint "easyedapro:LED-SMD_6P-L2.0-W2.0-P0.80-TL")
      (description "Wavelength:620nm~625nm；460nm~470nm；520nm~530nm Operating Temperature:-40°C~+80°C")
      (fields (field (name "Manufacturer") "欧思科光电"))
      (libsource (lib "easyedapro") (part "SK9822-EC20"))
    )
    (comp (ref "LED207")
      (value "SK9822-EC20")
      (footprint "easyedapro:LED-SMD_6P-L2.0-W2.0-P0.80-TL")
      (description "Wavelength:620nm~625nm；460nm~470nm；520nm~530nm Operating Temperature:-40°C~+80°C")
      (fields (field (name "Manufacturer") "欧思科光电"))
      (libsource (lib "easyedapro") (part "SK9822-EC20"))
    )
    (comp (ref "LED208")
      (value "SK9822-EC20")
      (footprint "easyedapro:LED-SMD_6P-L2.0-W2.0-P0.80-TL")
      (description "Wavelength:620nm~625nm；460nm~470nm；520nm~530nm Operating Temperature:-40°C~+80°C")
      (fields (field (name "Manufacturer") "欧思科光电"))
      (libsource (lib "easyedapro") (part "SK9822-EC20"))
    )
    (comp (ref "LED209")
      (value "SK9822-EC20")
      (footprint "easyedapro:LED-SMD_6P-L2.0-W2.0-P0.80-TL")
      (description "Wavelength:620nm~625nm；460nm~470nm；520nm~530nm Operating Temperature:-40°C~+80°C")
      (fields (field (name "Manufacturer") "欧思科光电"))
      (libsource (lib "easyedapro") (part "SK9822-EC20"))
    )
    (comp (ref "LED210")
      (value "SK9822-EC20")
      (footprint "easyedapro:LED-SMD_6P-L2.0-W2.0-P0.80-TL")
      (description "Wavelength:620nm~625nm；460nm~470nm；520nm~530nm Operating Temperature:-40°C~+80°C")
      (fields (field (name "Manufacturer") "欧思科光电"))
      (libsource (lib "easyedapro") (part "SK9822-EC20"))
    )
    (comp (ref "LED211")
      (value "SK9822-EC20")
      (footprint "easyedapro:LED-SMD_6P-L2.0-W2.0-P0.80-TL")
      (description "Wavelength:620nm~625nm；460nm~470nm；520nm~530nm Operating Temperature:-40°C~+80°C")
      (fields (field (name "Manufacturer") "欧思科光电"))
      (libsource (lib "easyedapro") (part "SK9822-EC20"))
    )
    (comp (ref "LED212")
      (value "SK9822-EC20")
      (footprint "easyedapro:LED-SMD_6P-L2.0-W2.0-P0.80-TL")
      (description "Wavelength:620nm~625nm；460nm~470nm；520nm~530nm Operating Temperature:-40°C~+80°C")
      (fields (field (name "Manufacturer") "欧思科光电"))
      (libsource (lib "easyedapro") (part "SK9822-EC20"))
    )
    (comp (ref "LED213")
      (value "SK9822-EC20")
      (footprint "easyedapro:LED-SMD_6P-L2.0-W2.0-P0.80-TL")
      (description "Wavelength:620nm~625nm；460nm~470nm；520nm~530nm Operating Temperature:-40°C~+80°C")
      (fields (field (name "Manufacturer") "欧思科光电"))
      (libsource (lib "easyedapro") (part "SK9822-EC20"))
    )
    (comp (ref "LED214")
      (value "SK9822-EC20")
      (footprint "easyedapro:LED-SMD_6P-L2.0-W2.0-P0.80-TL")
      (description "Wavelength:620nm~625nm；460nm~470nm；520nm~530nm Operating Temperature:-40°C~+80°C")
      (fields (field (name "Manufacturer") "欧思科光电"))
      (libsource (lib "easyedapro") (part "SK9822-EC20"))
    )
    (comp (ref "LED215")
      (value "SK9822-EC20")
      (footprint "easyedapro:LED-SMD_6P-L2.0-W2.0-P0.80-TL")
      (description "Wavelength:620nm~625nm；460nm~470nm；520nm~530nm Operating Temperature:-40°C~+80°C")
      (fields (field (name "Manufacturer") "欧思科光电"))
      (libsource (lib "easyedapro") (part "SK9822-EC20"))
    )
    (comp (ref "LED216")
      (value "SK9822-EC20")
      (footprint "easyedapro:LED-SMD_6P-L2.0-W2.0-P0.80-TL")
      (description "Wavelength:620nm~625nm；460nm~470nm；520nm~530nm Operating Temperature:-40°C~+80°C")
      (fields (field (name "Manufacturer") "欧思科光电"))
      (libsource (lib "easyedapro") (part "SK9822-EC20"))
    )
    (comp (ref "R1") (value "10K") (footprint "easyedapro:R0603") (libsource (lib "easyedapro") (part "Res")))
    (comp (ref "R2") (value "10K") (footprint "easyedapro:R0603") (libsource (lib "easyedapro") (part "Res")))
    (comp (ref "C19")
      (value "220uf")
      (footprint "easyedapro:C0603")
      (libsource (lib "easyedapro") (part "CAP"))
    )
    (comp (ref "C20")
      (value "22uF")
      (footprint "easyedapro:C0603")
      (libsource (lib "easyedapro") (part "CAP"))
    )
    (comp (ref "D1")
      (value "SS24")
      (footprint "easyedapro:SMA_L4.4-W2.8-LS5.4-RD")
      (fields (field (name "Manufacturer") "JSMSEMI(杰盛微)"))
      (libsource (lib "easyedapro") (part "D_1N4007"))
    )
    (comp (ref "L1")
      (value "4.7uH")
      (footprint "easyedapro:L0603")
      (libsource (lib "easyedapro") (part "电感"))
    )
    (comp (ref "R3")
      (value "110K")
      (footprint "easyedapro:R0603")
      (libsource (lib "easyedapro") (part "Res"))
    )
    (comp (ref "R4") (value "15K") (footprint "easyedapro:R0603") (libsource (lib "easyedapro") (part "Res")))
    (comp (ref "U1")
      (value "XIAO ESP32C3")
      (footprint "easyedapro:CONN-SMD_113991054")
      (libsource (lib "easyedapro") (part "XIAO ESP32C3"))
    )
    (comp (ref "U2")
      (value "MT3608")
      (footprint "easyedapro:SOT-23-6_L2.9-W1.6-P0.95-LS2.8-BL")
      (fields (field (name "Manufacturer") "西安航天民芯"))
      (libsource (lib "easyedapro") (part "MT3608"))
    )
  )
  (nets
    (net (code "1") (name "+5V") (class "Default")
      (node (ref "C1") (pin "1") (pinfunction "1_1") (pintype "input"))
      (node (ref "C10") (pin "1") (pinfunction "1_1") (pintype "input"))
      (node (ref "C11") (pin "1") (pinfunction "1_1") (pintype "input"))
      (node (ref "C12") (pin "1") (pinfunction "1_1") (pintype "input"))
      (node (ref "C13") (pin "1") (pinfunction "1_1") (pintype "input"))
      (node (ref "C14") (pin "1") (pinfunction "1_1") (pintype "input"))
      (node (ref "C15") (pin "1") (pinfunction "1_1") (pintype "input"))
      (node (ref "C16") (pin "1") (pinfunction "1_1") (pintype "input"))
      (node (ref "C17") (pin "1") (pinfunction "1_1") (pintype "input"))
      (node (ref "C19") (pin "2") (pinfunction "2_2") (pintype "input"))
      (node (ref "C2") (pin "1") (pinfunction "1_1") (pintype "input"))
      (node (ref "C3") (pin "1") (pinfunction "1_1") (pintype "input"))
      (node (ref "C4") (pin "1") (pinfunction "1_1") (pintype "input"))
      (node (ref "C5") (pin "1") (pinfunction "1_1") (pintype "input"))
      (node (ref "C6") (pin "1") (pinfunction "1_1") (pintype "input"))
      (node (ref "C7") (pin "1") (pinfunction "1_1") (pintype "input"))
      (node (ref "C8") (pin "1") (pinfunction "1_1") (pintype "input"))
      (node (ref "C9") (pin "1") (pinfunction "1_1") (pintype "input"))
      (node (ref "D1") (pin "1") (pinfunction "K_1") (pintype "input"))
      (node (ref "LED1") (pin "5") (pinfunction "VDD_5") (pintype "unspecified"))
      (node (ref "LED108") (pin "5") (pinfunction "VDD_5") (pintype "unspecified"))
      (node (ref "LED109") (pin "5") (pinfunction "VDD_5") (pintype "unspecified"))
      (node (ref "LED12") (pin "5") (pinfunction "VDD_5") (pintype "unspecified"))
      (node (ref "LED120") (pin "5") (pinfunction "VDD_5") (pintype "unspecified"))
      (node (ref "LED121") (pin "5") (pinfunction "VDD_5") (pintype "unspecified"))
      (node (ref "LED13") (pin "5") (pinfunction "VDD_5") (pintype "unspecified"))
      (node (ref "LED132") (pin "5") (pinfunction "VDD_5") (pintype "unspecified"))
      (node (ref "LED133") (pin "5") (pinfunction "VDD_5") (pintype "unspecified"))
      (node (ref "LED144") (pin "5") (pinfunction "VDD_5") (pintype "unspecified"))
      (node (ref "LED145") (pin "5") (pinfunction "VDD_5") (pintype "unspecified"))
      (node (ref "LED156") (pin "5") (pinfunction "VDD_5") (pintype "unspecified"))
      (node (ref "LED157") (pin "5") (pinfunction "VDD_5") (pintype "unspecified"))
      (node (ref "LED168") (pin "5") (pinfunction "VDD_5") (pintype "unspecified"))
      (node (ref "LED169") (pin "5") (pinfunction "VDD_5") (pintype "unspecified"))
      (node (ref "LED180") (pin "5") (pinfunction "VDD_5") (pintype "unspecified"))
      (node (ref "LED181") (pin "5") (pinfunction "VDD_5") (pintype "unspecified"))
      (node (ref "LED192") (pin "5") (pinfunction "VDD_5") (pintype "unspecified"))
      (node (ref "LED193") (pin "5") (pinfunction "VDD_5") (pintype "unspecified"))
      (node (ref "LED204") (pin "5") (pinfunction "VDD_5") (pintype "unspecified"))
      (node (ref "LED24") (pin "5") (pinfunction "VDD_5") (pintype "unspecified"))
      (node (ref "LED25") (pin "5") (pinfunction "VDD_5") (pintype "unspecified"))
      (node (ref "LED36") (pin "5") (pinfunction "VDD_5") (pintype "unspecified"))
      (node (ref "LED37") (pin "5") (pinfunction "VDD_5") (pintype "unspecified"))
      (node (ref "LED48") (pin "5") (pinfunction "VDD_5") (pintype "unspecified"))
      (node (ref "LED49") (pin "5") (pinfunction "VDD_5") (pintype "unspecified"))
      (node (ref "LED60") (pin "5") (pinfunction "VDD_5") (pintype "unspecified"))
      (node (ref "LED61") (pin "5") (pinfunction "VDD_5") (pintype "unspecified"))
      (node (ref "LED72") (pin "5") (pinfunction "VDD_5") (pintype "unspecified"))
      (node (ref "LED73") (pin "5") (pinfunction "VDD_5") (pintype "unspecified"))
      (node (ref "LED84") (pin "5") (pinfunction "VDD_5") (pintype "unspecified"))
      (node (ref "LED85") (pin "5") (pinfunction "VDD_5") (pintype "unspecified"))
      (node (ref "LED96") (pin "5") (pinfunction "VDD_5") (pintype "unspecified"))
      (node (ref "LED97") (pin "5") (pinfunction "VDD_5") (pintype "unspecified"))
      (node (ref "R3") (pin "2") (pinfunction "2_2") (pintype "input"))
    )
    (net (code "2") (name "AGND") (class "Default")
      (node (ref "C1") (pin "2") (pinfunction "2_2") (pintype "input"))
      (node (ref "C10") (pin "2") (pinfunction "2_2") (pintype "input"))
      (node (ref "C11") (pin "2") (pinfunction "2_2") (pintype "input"))
      (node (ref "C12") (pin "2") (pinfunction "2_2") (pintype "input"))
      (node (ref "C13") (pin "2") (pinfunction "2_2") (pintype "input"))
      (node (ref "C14") (pin "2") (pinfunction "2_2") (pintype "input"))
      (node (ref "C15") (pin "2") (pinfunction "2_2") (pintype "input"))
      (node (ref "C16") (pin "2") (pinfunction "2_2") (pintype "input"))
      (node (ref "C17") (pin "2") (pinfunction "2_2") (pintype "input"))
      (node (ref "C18") (pin "2") (pinfunction "2_2") (pintype "input"))
      (node (ref "C19") (pin "1") (pinfunction "1_1") (pintype "input"))
      (node (ref "C2") (pin "2") (pinfunction "2_2") (pintype "input"))
      (node (ref "C20") (pin "1") (pinfunction "1_1") (pintype "input"))
      (node (ref "C3") (pin "2") (pinfunction "2_2") (pintype "input"))
      (node (ref "C4") (pin "2") (pinfunction "2_2") (pintype "input"))
      (node (ref "C5") (pin "2") (pinfunction "2_2") (pintype "input"))
      (node (ref "C6") (pin "2") (pinfunction "2_2") (pintype "input"))
      (node (ref "C7") (pin "2") (pinfunction "2_2") (pintype "input"))
      (node (ref "C8") (pin "2") (pinfunction "2_2") (pintype "input"))
      (node (ref "C9") (pin "2") (pinfunction "2_2") (pintype "input"))
      (node (ref "LED1") (pin "2") (pinfunction "GND_2") (pintype "unspecified"))
      (node (ref "LED108") (pin "2") (pinfunction "GND_2") (pintype "unspecified"))
      (node (ref "LED109") (pin "2") (pinfunction "GND_2") (pintype "unspecified"))
      (node (ref "LED12") (pin "2") (pinfunction "GND_2") (pintype "unspecified"))
      (node (ref "LED120") (pin "2") (pinfunction "GND_2") (pintype "unspecified"))
      (node (ref "LED121") (pin "2") (pinfunction "GND_2") (pintype "unspecified"))
      (node (ref "LED13") (pin "2") (pinfunction "GND_2") (pintype "unspecified"))
      (node (ref "LED132") (pin "2") (pinfunction "GND_2") (pintype "unspecified"))
      (node (ref "LED133") (pin "2") (pinfunction "GND_2") (pintype "unspecified"))
      (node (ref "LED144") (pin "2") (pinfunction "GND_2") (pintype "unspecified"))
      (node (ref "LED145") (pin "2") (pinfunction "GND_2") (pintype "unspecified"))
      (node (ref "LED156") (pin "2") (pinfunction "GND_2") (pintype "unspecified"))
      (node (ref "LED157") (pin "2") (pinfunction "GND_2") (pintype "unspecified"))
      (node (ref "LED168") (pin "2") (pinfunction "GND_2") (pintype "unspecified"))
      (node (ref "LED169") (pin "2") (pinfunction "GND_2") (pintype "unspecified"))
      (node (ref "LED180") (pin "2") (pinfunction "GND_2") (pintype "unspecified"))
      (node (ref "LED181") (pin "2") (pinfunction "GND_2") (pintype "unspecified"))
      (node (ref "LED192") (pin "2") (pinfunction "GND_2") (pintype "unspecified"))
      (node (ref "LED193") (pin "2") (pinfunction "GND_2") (pintype "unspecified"))
      (node (ref "LED204") (pin "2") (pinfunction "GND_2") (pintype "unspecified"))
      (node (ref "LED205") (pin "2") (pinfunction "GND_2") (pintype "unspecified"))
      (node (ref "LED216") (pin "2") (pinfunction "GND_2") (pintype "unspecified"))
      (node (ref "LED24") (pin "2") (pinfunction "GND_2") (pintype "unspecified"))
      (node (ref "LED25") (pin "2") (pinfunction "GND_2") (pintype "unspecified"))
      (node (ref "LED36") (pin "2") (pinfunction "GND_2") (pintype "unspecified"))
      (node (ref "LED37") (pin "2") (pinfunction "GND_2") (pintype "unspecified"))
      (node (ref "LED48") (pin "2") (pinfunction "GND_2") (pintype "unspecified"))
      (node (ref "LED49") (pin "2") (pinfunction "GND_2") (pintype "unspecified"))
      (node (ref "LED60") (pin "2") (pinfunction "GND_2") (pintype "unspecified"))
      (node (ref "LED61") (pin "2") (pinfunction "GND_2") (pintype "unspecified"))
      (node (ref "LED72") (pin "2") (pinfunction "GND_2") (pintype "unspecified"))
      (node (ref "LED73") (pin "2") (pinfunction "GND_2") (pintype "unspecified"))
      (node (ref "LED84") (pin "2") (pinfunction "GND_2") (pintype "unspecified"))
      (node (ref "LED85") (pin "2") (pinfunction "GND_2") (pintype "unspecified"))
      (node (ref "LED96") (pin "2") (pinfunction "GND_2") (pintype "unspecified"))
      (node (ref "LED97") (pin "2") (pinfunction "GND_2") (pintype "unspecified"))
      (node (ref "R4") (pin "1") (pinfunction "1_1") (pintype "input"))
      (node (ref "U1") (pin "16") (pinfunction "BAT-_16") (pintype "unspecified"))
      (node (ref "U2") (pin "2") (pinfunction "GND_2") (pintype "unspecified"))
    )
    (net (code "3") (name "CKL") (class "Default")
      (node (ref "R1") (pin "2") (pinfunction "2_2") (pintype "input"))
      (node (ref "U1") (pin "9") (pinfunction "D8_9") (pintype "unspecified"))
    )
    (net (code "4") (name "EN") (class "Default")
      (node (ref "U1") (pin "7") (pinfunction "D6_7") (pintype "unspecified"))
      (node (ref "U2") (pin "4") (pinfunction "EN_4") (pintype "unspecified"))
    )
    (net (code "5") (name "Net-(D1-A)") (class "Default")
      (node (ref "D1") (pin "2") (pinfunction "A_2") (pintype "input"))
      (node (ref "L1") (pin "1") (pinfunction "1_1") (pintype "input"))
      (node (ref "U2") (pin "1") (pinfunction "SW_1") (pintype "unspecified"))
    )
    (net (code "6") (name "Net-(LED1-CKL)") (class "Default")
      (node (ref "LED1") (pin "4") (pinfunction "CKL_4") (pintype "unspecified"))
      (node (ref "R1") (pin "1") (pinfunction "1_1") (pintype "input"))
    )
    (net (code "7") (name "Net-(LED1-CKO)") (class "Default")
      (node (ref "LED1") (pin "6") (pinfunction "CKO_6") (pintype "unspecified"))
      (node (ref "LED2") (pin "4") (pinfunction "CKL_4") (pintype "unspecified"))
    )
    (net (code "8") (name "Net-(LED1-SDI)") (class "Default")
      (node (ref "LED1") (pin "3") (pinfunction "SDI_3") (pintype "unspecified"))
      (node (ref "R2") (pin "1") (pinfunction "1_1") (pintype "input"))
    )
    (net (code "9") (name "Net-(LED1-SDO)") (class "Default")
      (node (ref "LED1") (pin "1") (pinfunction "SDO_1") (pintype "unspecified"))
      (node (ref "LED2") (pin "3") (pinfunction "SDI_3") (pintype "unspecified"))
    )
    (net (code "10") (name "Net-(LED2-CKO)") (class "Default")
      (node (ref "LED2") (pin "6") (pinfunction "CKO_6") (pintype "unspecified"))
      (node (ref "LED3") (pin "4") (pinfunction "CKL_4") (pintype "unspecified"))
    )
    (net (code "11") (name "Net-(LED2-SDO)") (class "Default")
      (node (ref "LED2") (pin "1") (pinfunction "SDO_1") (pintype "unspecified"))
      (node (ref "LED3") (pin "3") (pinfunction "SDI_3") (pintype "unspecified"))
    )
    (net (code "12") (name "Net-(LED3-CKO)") (class "Default")
      (node (ref "LED3") (pin "6") (pinfunction "CKO_6") (pintype "unspecified"))
      (node (ref "LED4") (pin "4") (pinfunction "CKL_4") (pintype "unspecified"))
    )
    (net (code "13") (name "Net-(LED3-SDO)") (class "Default")
      (node (ref "LED3") (pin "1") (pinfunction "SDO_1") (pintype "unspecified"))
      (node (ref "LED4") (pin "3") (pinfunction "SDI_3") (pintype "unspecified"))
    )
    (net (code "14") (name "Net-(LED4-CKO)") (class "Default")
      (node (ref "LED4") (pin "6") (pinfunction "CKO_6") (pintype "unspecified"))
      (node (ref "LED5") (pin "4") (pinfunction "CKL_4") (pintype "unspecified"))
    )
    (net (code "15") (name "Net-(LED4-SDO)") (class "Default")
      (node (ref "LED4") (pin "1") (pinfunction "SDO_1") (pintype "unspecified"))
      (node (ref "LED5") (pin "3") (pinfunction "SDI_3") (pintype "unspecified"))
    )
    (net (code "16") (name "Net-(LED5-CKO)") (class "Default")
      (node (ref "LED5") (pin "6") (pinfunction "CKO_6") (pintype "unspecified"))
      (node (ref "LED6") (pin "4") (pinfunction "CKL_4") (pintype "unspecified"))
    )
    (net (code "17") (name "Net-(LED5-SDO)") (class "Default")
      (node (ref "LED5") (pin "1") (pinfunction "SDO_1") (pintype "unspecified"))
      (node (ref "LED6") (pin "3") (pinfunction "SDI_3") (pintype "unspecified"))
    )
    (net (code "18") (name "Net-(LED6-CKO)") (class "Default")
      (node (ref "LED6") (pin "6") (pinfunction "CKO_6") (pintype "unspecified"))
      (node (ref "LED7") (pin "4") (pinfunction "CKL_4") (pintype "unspecified"))
    )
    (net (code "19") (name "Net-(LED6-SDO)") (class "Default")
      (node (ref "LED6") (pin "1") (pinfunction "SDO_1") (pintype "unspecified"))
      (node (ref "LED7") (pin "3") (pinfunction "SDI_3") (pintype "unspecified"))
    )
    (net (code "20") (name "Net-(LED7-CKO)") (class "Default")
      (node (ref "LED7") (pin "6") (pinfunction "CKO_6") (pintype "unspecified"))
      (node (ref "LED8") (pin "4") (pinfunction "CKL_4") (pintype "unspecified"))
    )
    (net (code "21") (name "Net-(LED7-SDO)") (class "Default")
      (node (ref "LED7") (pin "1") (pinfunction "SDO_1") (pintype "unspecified"))
      (node (ref "LED8") (pin "3") (pinfunction "SDI_3") (pintype "unspecified"))
    )
    (net (code "22") (name "Net-(LED8-CKO)") (class "Default")
      (node (ref "LED8") (pin "6") (pinfunction "CKO_6") (pintype "unspecified"))
      (node (ref "LED9") (pin "4") (pinfunction "CKL_4") (pintype "unspecified"))
    )
    (net (code "23") (name "Net-(LED8-SDO)") (class "Default")
      (node (ref "LED8") (pin "1") (pinfunction "SDO_1") (pintype "unspecified"))
      (node (ref "LED9") (pin "3") (pinfunction "SDI_3") (pintype "unspecified"))
    )
    (net (code "24") (name "Net-(LED10-CKL)") (class "Default")
      (node (ref "LED10") (pin "4") (pinfunction "CKL_4") (pintype "unspecified"))
      (node (ref "LED9") (pin "6") (pinfunction "CKO_6") (pintype "unspecified"))
    )
    (net (code "25") (name "Net-(LED10-CKO)") (class "Default")
      (node (ref "LED10") (pin "6") (pinfunction "CKO_6") (pintype "unspecified"))
      (node (ref "LED11") (pin "4") (pinfunction "CKL_4") (pintype "unspecified"))
    )
    (net (code "26") (name "Net-(LED10-SDI)") (class "Default")
      (node (ref "LED10") (pin "3") (pinfunction "SDI_3") (pintype "unspecified"))
      (node (ref "LED9") (pin "1") (pinfunction "SDO_1") (pintype "unspecified"))
    )
    (net (code "27") (name "Net-(LED10-SDO)") (class "Default")
      (node (ref "LED10") (pin "1") (pinfunction "SDO_1") (pintype "unspecified"))
      (node (ref "LED11") (pin "3") (pinfunction "SDI_3") (pintype "unspecified"))
    )
    (net (code "28") (name "Net-(LED11-CKO)") (class "Default")
      (node (ref "LED11") (pin "6") (pinfunction "CKO_6") (pintype "unspecified"))
      (node (ref "LED12") (pin "4") (pinfunction "CKL_4") (pintype "unspecified"))
    )
    (net (code "29") (name "Net-(LED11-SDO)") (class "Default")
      (node (ref "LED11") (pin "1") (pinfunction "SDO_1") (pintype "unspecified"))
      (node (ref "LED12") (pin "3") (pinfunction "SDI_3") (pintype "unspecified"))
    )
    (net (code "30") (name "Net-(LED12-CKO)") (class "Default")
      (node (ref "LED12") (pin "6") (pinfunction "CKO_6") (pintype "unspecified"))
      (node (ref "LED24") (pin "4") (pinfunction "CKL_4") (pintype "unspecified"))
    )
    (net (code "31") (name "Net-(LED12-SDO)") (class "Default")
      (node (ref "LED12") (pin "1") (pinfunction "SDO_1") (pintype "unspecified"))
      (node (ref "LED24") (pin "3") (pinfunction "SDI_3") (pintype "unspecified"))
    )
    (net (code "32") (name "Net-(LED13-CKL)") (class "Default")
      (node (ref "LED13") (pin "4") (pinfunction "CKL_4") (pintype "unspecified"))
      (node (ref "LED14") (pin "6") (pinfunction "CKO_6") (pintype "unspecified"))
    )
    (net (code "33") (name "Net-(LED13-CKO)") (class "Default")
      (node (ref "LED13") (pin "6") (pinfunction "CKO_6") (pintype "unspecified"))
      (node (ref "LED25") (pin "4") (pinfunction "CKL_4") (pintype "unspecified"))
    )
    (net (code "34") (name "Net-(LED13-SDI)") (class "Default")
      (node (ref "LED13") (pin "3") (pinfunction "SDI_3") (pintype "unspecified"))
      (node (ref "LED14") (pin "1") (pinfunction "SDO_1") (pintype "unspecified"))
    )
    (net (code "35") (name "Net-(LED13-SDO)") (class "Default")
      (node (ref "LED13") (pin "1") (pinfunction "SDO_1") (pintype "unspecified"))
      (node (ref "LED25") (pin "3") (pinfunction "SDI_3") (pintype "unspecified"))
    )
    (net (code "36") (name "Net-(LED14-CKL)") (class "Default")
      (node (ref "LED14") (pin "4") (pinfunction "CKL_4") (pintype "unspecified"))
      (node (ref "LED15") (pin "6") (pinfunction "CKO_6") (pintype "unspecified"))
    )
    (net (code "37") (name "Net-(LED14-SDI)") (class "Default")
      (node (ref "LED14") (pin "3") (pinfunction "SDI_3") (pintype "unspecified"))
      (node (ref "LED15") (pin "1") (pinfunction "SDO_1") (pintype "unspecified"))
    )
    (net (code "38") (name "Net-(LED15-CKL)") (class "Default")
      (node (ref "LED15") (pin "4") (pinfunction "CKL_4") (pintype "unspecified"))
      (node (ref "LED16") (pin "6") (pinfunction "CKO_6") (pintype "unspecified"))
    )
    (net (code "39") (name "Net-(LED15-SDI)") (class "Default")
      (node (ref "LED15") (pin "3") (pinfunction "SDI_3") (pintype "unspecified"))
      (node (ref "LED16") (pin "1") (pinfunction "SDO_1") (pintype "unspecified"))
    )
    (net (code "40") (name "Net-(LED16-CKL)") (class "Default")
      (node (ref "LED16") (pin "4") (pinfunction "CKL_4") (pintype "unspecified"))
      (node (ref "LED17") (pin "6") (pinfunction "CKO_6") (pintype "unspecified"))
    )
    (net (code "41") (name "Net-(LED16-SDI)") (class "Default")
      (node (ref "LED16") (pin "3") (pinfunction "SDI_3") (pintype "unspecified"))
      (node (ref "LED17") (pin "1") (pinfunction "SDO_1") (pintype "unspecified"))
    )
    (net (code "42") (name "Net-(LED17-CKL)") (class "Default")
      (node (ref "LED17") (pin "4") (pinfunction "CKL_4") (pintype "unspecified"))
      (node (ref "LED18") (pin "6") (pinfunction "CKO_6") (pintype "unspecified"))
    )
    (net (code "43") (name "Net-(LED17-SDI)") (class "Default")
      (node (ref "LED17") (pin "3") (pinfunction "SDI_3") (pintype "unspecified"))
      (node (ref "LED18") (pin "1") (pinfunction "SDO_1") (pintype "unspecified"))
    )
    (net (code "44") (name "Net-(LED18-CKL)") (class "Default")
      (node (ref "LED18") (pin "4") (pinfunction "CKL_4") (pintype "unspecified"))
      (node (ref "LED19") (pin "6") (pinfunction "CKO_6") (pintype "unspecified"))
    )
    (net (code "45") (name "Net-(LED18-SDI)") (class "Default")
      (node (ref "LED18") (pin "3") (pinfunction "SDI_3") (pintype "unspecified"))
      (node (ref "LED19") (pin "1") (pinfunction "SDO_1") (pintype "unspecified"))
    )
    (net (code "46") (name "Net-(LED19-CKL)") (class "Default")
      (node (ref "LED19") (pin "4") (pinfunction "CKL_4") (pintype "unspecified"))
      (node (ref "LED20") (pin "6") (pinfunction "CKO_6") (pintype "unspecified"))
    )
    (net (code "47") (name "Net-(LED19-SDI)") (class "Default")
      (node (ref "LED19") (pin "3") (pinfunction "SDI_3") (pintype "unspecified"))
      (node (ref "LED20") (pin "1") (pinfunction "SDO_1") (pintype "unspecified"))
    )
    (net (code "48") (name "Net-(LED20-CKL)") (class "Default")
      (node (ref "LED20") (pin "4") (pinfunction "CKL_4") (pintype "unspecified"))
      (node (ref "LED21") (pin "6") (pinfunction "CKO_6") (pintype "unspecified"))
    )
    (net (code "49") (name "Net-(LED20-SDI)") (class "Default")
      (node (ref "LED20") (pin "3") (pinfunction "SDI_3") (pintype "unspecified"))
      (node (ref "LED21") (pin "1") (pinfunction "SDO_1") (pintype "unspecified"))
    )
    (net (code "50") (name "Net-(LED21-CKL)") (class "Default")
      (node (ref "LED21") (pin "4") (pinfunction "CKL_4") (pintype "unspecified"))
      (node (ref "LED22") (pin "6") (pinfunction "CKO_6") (pintype "unspecified"))
    )
    (net (code "51") (name "Net-(LED21-SDI)") (class "Default")
      (node (ref "LED21") (pin "3") (pinfunction "SDI_3") (pintype "unspecified"))
      (node (ref "LED22") (pin "1") (pinfunction "SDO_1") (pintype "unspecified"))
    )
    (net (code "52") (name "Net-(LED22-CKL)") (class "Default")
      (node (ref "LED22") (pin "4") (pinfunction "CKL_4") (pintype "unspecified"))
      (node (ref "LED23") (pin "6") (pinfunction "CKO_6") (pintype "unspecified"))
    )
    (net (code "53") (name "Net-(LED22-SDI)") (class "Default")
      (node (ref "LED22") (pin "3") (pinfunction "SDI_3") (pintype "unspecified"))
      (node (ref "LED23") (pin "1") (pinfunction "SDO_1") (pintype "unspecified"))
    )
    (net (code "54") (name "Net-(LED23-CKL)") (class "Default")
      (node (ref "LED23") (pin "4") (pinfunction "CKL_4") (pintype "unspecified"))
      (node (ref "LED24") (pin "6") (pinfunction "CKO_6") (pintype "unspecified"))
    )
    (net (code "55") (name "Net-(LED23-SDI)") (class "Default")
      (node (ref "LED23") (pin "3") (pinfunction "SDI_3") (pintype "unspecified"))
      (node (ref "LED24") (pin "1") (pinfunction "SDO_1") (pintype "unspecified"))
    )
    (net (code "56") (name "Net-(LED25-CKO)") (class "Default")
      (node (ref "LED25") (pin "6") (pinfunction "CKO_6") (pintype "unspecified"))
      (node (ref "LED26") (pin "4") (pinfunction "CKL_4") (pintype "unspecified"))
    )
    (net (code "57") (name "Net-(LED25-SDO)") (class "Default")
      (node (ref "LED25") (pin "1") (pinfunction "SDO_1") (pintype "unspecified"))
      (node (ref "LED26") (pin "3") (pinfunction "SDI_3") (pintype "unspecified"))
    )
    (net (code "58") (name "Net-(LED26-CKO)") (class "Default")
      (node (ref "LED26") (pin "6") (pinfunction "CKO_6") (pintype "unspecified"))
      (node (ref "LED27") (pin "4") (pinfunction "CKL_4") (pintype "unspecified"))
    )
    (net (code "59") (name "Net-(LED26-SDO)") (class "Default")
      (node (ref "LED26") (pin "1") (pinfunction "SDO_1") (pintype "unspecified"))
      (node (ref "LED27") (pin "3") (pinfunction "SDI_3") (pintype "unspecified"))
    )
    (net (code "60") (name "Net-(LED27-CKO)") (class "Default")
      (node (ref "LED27") (pin "6") (pinfunction "CKO_6") (pintype "unspecified"))
      (node (ref "LED28") (pin "4") (pinfunction "CKL_4") (pintype "unspecified"))
    )
    (net (code "61") (name "Net-(LED27-SDO)") (class "Default")
      (node (ref "LED27") (pin "1") (pinfunction "SDO_1") (pintype "unspecified"))
      (node (ref "LED28") (pin "3") (pinfunction "SDI_3") (pintype "unspecified"))
    )
    (net (code "62") (name "Net-(LED28-CKO)") (class "Default")
      (node (ref "LED28") (pin "6") (pinfunction "CKO_6") (pintype "unspecified"))
      (node (ref "LED29") (pin "4") (pinfunction "CKL_4") (pintype "unspecified"))
    )
    (net (code "63") (name "Net-(LED28-SDO)") (class "Default")
      (node (ref "LED28") (pin "1") (pinfunction "SDO_1") (pintype "unspecified"))
      (node (ref "LED29") (pin "3") (pinfunction "SDI_3") (pintype "unspecified"))
    )
    (net (code "64") (name "Net-(LED29-CKO)") (class "Default")
      (node (ref "LED29") (pin "6") (pinfunction "CKO_6") (pintype "unspecified"))
      (node (ref "LED30") (pin "4") (pinfunction "CKL_4") (pintype "unspecified"))
    )
    (net (code "65") (name "Net-(LED29-SDO)") (class "Default")
      (node (ref "LED29") (pin "1") (pinfunction "SDO_1") (pintype "unspecified"))
      (node (ref "LED30") (pin "3") (pinfunction "SDI_3") (pintype "unspecified"))
    )
    (net (code "66") (name "Net-(LED30-CKO)") (class "Default")
      (node (ref "LED30") (pin "6") (pinfunction "CKO_6") (pintype "unspecified"))
      (node (ref "LED31") (pin "4") (pinfunction "CKL_4") (pintype "unspecified"))
    )
    (net (code "67") (name "Net-(LED30-SDO)") (class "Default")
      (node (ref "LED30") (pin "1") (pinfunction "SDO_1") (pintype "unspecified"))
      (node (ref "LED31") (pin "3") (pinfunction "SDI_3") (pintype "unspecified"))
    )
    (net (code "68") (name "Net-(LED31-CKO)") (class "Default")
      (node (ref "LED31") (pin "6") (pinfunction "CKO_6") (pintype "unspecified"))
      (node (ref "LED32") (pin "4") (pinfunction "CKL_4") (pintype "unspecified"))
    )
    (net (code "69") (name "Net-(LED31-SDO)") (class "Default")
      (node (ref "LED31") (pin "1") (pinfunction "SDO_1") (pintype "unspecified"))
      (node (ref "LED32") (pin "3") (pinfunction "SDI_3") (pintype "unspecified"))
    )
    (net (code "70") (name "Net-(LED32-CKO)") (class "Default")
      (node (ref "LED32") (pin "6") (pinfunction "CKO_6") (pintype "unspecified"))
      (node (ref "LED33") (pin "4") (pinfunction "CKL_4") (pintype "unspecified"))
    )
    (net (code "71") (name "Net-(LED32-SDO)") (class "Default")
      (node (ref "LED32") (pin "1") (pinfunction "SDO_1") (pintype "unspecified"))
      (node (ref "LED33") (pin "3") (pinfunction "SDI_3") (pintype "unspecified"))
    )
    (net (code "72") (name "Net-(LED33-CKO)") (class "Default")
      (node (ref "LED33") (pin "6") (pinfunction "CKO_6") (pintype "unspecified"))
      (node (ref "LED34") (pin "4") (pinfunction "CKL_4") (pintype "unspecified"))
    )
    (net (code "73") (name "Net-(LED33-SDO)") (class "Default")
      (node (ref "LED33") (pin "1") (pinfunction "SDO_1") (pintype "unspecified"))
      (node (ref "LED34") (pin "3") (pinfunction "SDI_3") (pintype "unspecified"))
    )
    (net (code "74") (name "Net-(LED34-CKO)") (class "Default")
      (node (ref "LED34") (pin "6") (pinfunction "CKO_6") (pintype "unspecified"))
      (node (ref "LED35") (pin "4") (pinfunction "CKL_4") (pintype "unspecified"))
    )
    (net (code "75") (name "Net-(LED34-SDO)") (class "Default")
      (node (ref "LED34") (pin "1") (pinfunction "SDO_1") (pintype "unspecified"))
      (node (ref "LED35") (pin "3") (pinfunction "SDI_3") (pintype "unspecified"))
    )
    (net (code "76") (name "Net-(LED35-CKO)") (class "Default")
      (node (ref "LED35") (pin "6") (pinfunction "CKO_6") (pintype "unspecified"))
      (node (ref "LED36") (pin "4") (pinfunction "CKL_4") (pintype "unspecified"))
    )
    (net (code "77") (name "Net-(LED35-SDO)") (class "Default")
      (node (ref "LED35") (pin "1") (pinfunction "SDO_1") (pintype "unspecified"))
      (node (ref "LED36") (pin "3") (pinfunction "SDI_3") (pintype "unspecified"))
    )
    (net (code "78") (name "Net-(LED36-CKO)") (class "Default")
      (node (ref "LED36") (pin "6") (pinfunction "CKO_6") (pintype "unspecified"))
      (node (ref "LED48") (pin "4") (pinfunction "CKL_4") (pintype "unspecified"))
    )
    (net (code "79") (name "Net-(LED36-SDO)") (class "Default")
      (node (ref "LED36") (pin "1") (pinfunction "SDO_1") (pintype "unspecified"))
      (node (ref "LED48") (pin "3") (pinfunction "SDI_3") (pintype "unspecified"))
    )
    (net (code "80") (name "Net-(LED37-CKL)") (class "Default")
      (node (ref "LED37") (pin "4") (pinfunction "CKL_4") (pintype "unspecified"))
      (node (ref "LED38") (pin "6") (pinfunction "CKO_6") (pintype "unspecified"))
    )
    (net (code "81") (name "Net-(LED37-CKO)") (class "Default")
      (node (ref "LED37") (pin "1") (pinfunction "SDO_1") (pintype "unspecified"))
      (node (ref "LED37") (pin "6") (pinfunction "CKO_6") (pintype "unspecified"))
      (node (ref "LED49") (pin "4") (pinfunction "CKL_4") (pintype "unspecified"))
    )
    (net (code "82") (name "Net-(LED37-SDI)") (class "Default")
      (node (ref "LED37") (pin "3") (pinfunction "SDI_3") (pintype "unspecified"))
      (node (ref "LED38") (pin "1") (pinfunction "SDO_1") (pintype "unspecified"))
    )
    (net (code "83") (name "Net-(LED38-CKL)") (class "Default")
      (node (ref "LED38") (pin "4") (pinfunction "CKL_4") (pintype "unspecified"))
      (node (ref "LED39") (pin "6") (pinfunction "CKO_6") (pintype "unspecified"))
    )
    (net (code "84") (name "Net-(LED38-SDI)") (class "Default")
      (node (ref "LED38") (pin "3") (pinfunction "SDI_3") (pintype "unspecified"))
      (node (ref "LED39") (pin "1") (pinfunction "SDO_1") (pintype "unspecified"))
    )
    (net (code "85") (name "Net-(LED39-CKL)") (class "Default")
      (node (ref "LED39") (pin "4") (pinfunction "CKL_4") (pintype "unspecified"))
      (node (ref "LED40") (pin "6") (pinfunction "CKO_6") (pintype "unspecified"))
    )
    (net (code "86") (name "Net-(LED39-SDI)") (class "Default")
      (node (ref "LED39") (pin "3") (pinfunction "SDI_3") (pintype "unspecified"))
      (node (ref "LED40") (pin "1") (pinfunction "SDO_1") (pintype "unspecified"))
    )
    (net (code "87") (name "Net-(LED40-CKL)") (class "Default")
      (node (ref "LED40") (pin "4") (pinfunction "CKL_4") (pintype "unspecified"))
      (node (ref "LED41") (pin "6") (pinfunction "CKO_6") (pintype "unspecified"))
    )
    (net (code "88") (name "Net-(LED40-SDI)") (class "Default")
      (node (ref "LED40") (pin "3") (pinfunction "SDI_3") (pintype "unspecified"))
      (node (ref "LED41") (pin "1") (pinfunction "SDO_1") (pintype "unspecified"))
    )
    (net (code "89") (name "Net-(LED41-CKL)") (class "Default")
      (node (ref "LED41") (pin "4") (pinfunction "CKL_4") (pintype "unspecified"))
      (node (ref "LED42") (pin "6") (pinfunction "CKO_6") (pintype "unspecified"))
    )
    (net (code "90") (name "Net-(LED41-SDI)") (class "Default")
      (node (ref "LED41") (pin "3") (pinfunction "SDI_3") (pintype "unspecified"))
      (node (ref "LED42") (pin "1") (pinfunction "SDO_1") (pintype "unspecified"))
    )
    (net (code "91") (name "Net-(LED42-CKL)") (class "Default")
      (node (ref "LED42") (pin "4") (pinfunction "CKL_4") (pintype "unspecified"))
      (node (ref "LED43") (pin "6") (pinfunction "CKO_6") (pintype "unspecified"))
    )
    (net (code "92") (name "Net-(LED42-SDI)") (class "Default")
      (node (ref "LED42") (pin "3") (pinfunction "SDI_3") (pintype "unspecified"))
      (node (ref "LED43") (pin "1") (pinfunction "SDO_1") (pintype "unspecified"))
    )
    (net (code "93") (name "Net-(LED43-CKL)") (class "Default")
      (node (ref "LED43") (pin "4") (pinfunction "CKL_4") (pintype "unspecified"))
      (node (ref "LED44") (pin "6") (pinfunction "CKO_6") (pintype "unspecified"))
    )
    (net (code "94") (name "Net-(LED43-SDI)") (class "Default")
      (node (ref "LED43") (pin "3") (pinfunction "SDI_3") (pintype "unspecified"))
      (node (ref "LED44") (pin "1") (pinfunction "SDO_1") (pintype "unspecified"))
    )
    (net (code "95") (name "Net-(LED44-CKL)") (class "Default")
      (node (ref "LED44") (pin "4") (pinfunction "CKL_4") (pintype "unspecified"))
      (node (ref "LED45") (pin "6") (pinfunction "CKO_6") (pintype "unspecified"))
    )
    (net (code "96") (name "Net-(LED44-SDI)") (class "Default")
      (node (ref "LED44") (pin "3") (pinfunction "SDI_3") (pintype "unspecified"))
      (node (ref "LED45") (pin "1") (pinfunction "SDO_1") (pintype "unspecified"))
    )
    (net (code "97") (name "Net-(LED45-CKL)") (class "Default")
      (node (ref "LED45") (pin "4") (pinfunction "CKL_4") (pintype "unspecified"))
      (node (ref "LED46") (pin "6") (pinfunction "CKO_6") (pintype "unspecified"))
    )
    (net (code "98") (name "Net-(LED45-SDI)") (class "Default")
      (node (ref "LED45") (pin "3") (pinfunction "SDI_3") (pintype "unspecified"))
      (node (ref "LED46") (pin "1") (pinfunction "SDO_1") (pintype "unspecified"))
    )
    (net (code "99") (name "Net-(LED46-CKL)") (class "Default")
      (node (ref "LED46") (pin "4") (pinfunction "CKL_4") (pintype "unspecified"))
      (node (ref "LED47") (pin "6") (pinfunction "CKO_6") (pintype "unspecified"))
    )
    (net (code "100") (name "Net-(LED46-SDI)") (class "Default")
      (node (ref "LED46") (pin "3") (pinfunction "SDI_3") (pintype "unspecified"))
      (node (ref "LED47") (pin "1") (pinfunction "SDO_1") (pintype "unspecified"))
    )
    (net (code "101") (name "Net-(LED47-CKL)") (class "Default")
      (node (ref "LED47") (pin "4") (pinfunction "CKL_4") (pintype "unspecified"))
      (node (ref "LED48") (pin "6") (pinfunction "CKO_6") (pintype "unspecified"))
    )
    (net (code "102") (name "Net-(LED47-SDI)") (class "Default")
      (node (ref "LED47") (pin "3") (pinfunction "SDI_3") (pintype "unspecified"))
      (node (ref "LED48") (pin "1") (pinfunction "SDO_1") (pintype "unspecified"))
    )
    (net (code "103") (name "Net-(LED49-CKO)") (class "Default")
      (node (ref "LED49") (pin "6") (pinfunction "CKO_6") (pintype "unspecified"))
      (node (ref "LED50") (pin "4") (pinfunction "CKL_4") (pintype "unspecified"))
    )
    (net (code "104") (name "Net-(LED49-SDO)") (class "Default")
      (node (ref "LED49") (pin "1") (pinfunction "SDO_1") (pintype "unspecified"))
      (node (ref "LED50") (pin "3") (pinfunction "SDI_3") (pintype "unspecified"))
    )
    (net (code "105") (name "Net-(LED50-CKO)") (class "Default")
      (node (ref "LED50") (pin "6") (pinfunction "CKO_6") (pintype "unspecified"))
      (node (ref "LED51") (pin "4") (pinfunction "CKL_4") (pintype "unspecified"))
    )
    (net (code "106") (name "Net-(LED50-SDO)") (class "Default")
      (node (ref "LED50") (pin "1") (pinfunction "SDO_1") (pintype "unspecified"))
      (node (ref "LED51") (pin "3") (pinfunction "SDI_3") (pintype "unspecified"))
    )
    (net (code "107") (name "Net-(LED51-CKO)") (class "Default")
      (node (ref "LED51") (pin "6") (pinfunction "CKO_6") (pintype "unspecified"))
      (node (ref "LED52") (pin "4") (pinfunction "CKL_4") (pintype "unspecified"))
    )
    (net (code "108") (name "Net-(LED51-SDO)") (class "Default")
      (node (ref "LED51") (pin "1") (pinfunction "SDO_1") (pintype "unspecified"))
      (node (ref "LED52") (pin "3") (pinfunction "SDI_3") (pintype "unspecified"))
    )
    (net (code "109") (name "Net-(LED52-CKO)") (class "Default")
      (node (ref "LED52") (pin "6") (pinfunction "CKO_6") (pintype "unspecified"))
      (node (ref "LED53") (pin "4") (pinfunction "CKL_4") (pintype "unspecified"))
    )
    (net (code "110") (name "Net-(LED52-SDO)") (class "Default")
      (node (ref "LED52") (pin "1") (pinfunction "SDO_1") (pintype "unspecified"))
      (node (ref "LED53") (pin "3") (pinfunction "SDI_3") (pintype "unspecified"))
    )
    (net (code "111") (name "Net-(LED53-CKO)") (class "Default")
      (node (ref "LED53") (pin "6") (pinfunction "CKO_6") (pintype "unspecified"))
      (node (ref "LED54") (pin "4") (pinfunction "CKL_4") (pintype "unspecified"))
    )
    (net (code "112") (name "Net-(LED53-SDO)") (class "Default")
      (node (ref "LED53") (pin "1") (pinfunction "SDO_1") (pintype "unspecified"))
      (node (ref "LED54") (pin "3") (pinfunction "SDI_3") (pintype "unspecified"))
    )
    (net (code "113") (name "Net-(LED54-CKO)") (class "Default")
      (node (ref "LED54") (pin "6") (pinfunction "CKO_6") (pintype "unspecified"))
      (node (ref "LED55") (pin "4") (pinfunction "CKL_4") (pintype "unspecified"))
    )
    (net (code "114") (name "Net-(LED54-SDO)") (class "Default")
      (node (ref "LED54") (pin "1") (pinfunction "SDO_1") (pintype "unspecified"))
      (node (ref "LED55") (pin "3") (pinfunction "SDI_3") (pintype "unspecified"))
    )
    (net (code "115") (name "Net-(LED55-CKO)") (class "Default")
      (node (ref "LED55") (pin "6") (pinfunction "CKO_6") (pintype "unspecified"))
      (node (ref "LED56") (pin "4") (pinfunction "CKL_4") (pintype "unspecified"))
    )
    (net (code "116") (name "Net-(LED55-SDO)") (class "Default")
      (node (ref "LED55") (pin "1") (pinfunction "SDO_1") (pintype "unspecified"))
      (node (ref "LED56") (pin "3") (pinfunction "SDI_3") (pintype "unspecified"))
    )
    (net (code "117") (name "Net-(LED56-CKO)") (class "Default")
      (node (ref "LED56") (pin "6") (pinfunction "CKO_6") (pintype "unspecified"))
      (node (ref "LED57") (pin "4") (pinfunction "CKL_4") (pintype "unspecified"))
    )
    (net (code "118") (name "Net-(LED56-SDO)") (class "Default")
      (node (ref "LED56") (pin "1") (pinfunction "SDO_1") (pintype "unspecified"))
      (node (ref "LED57") (pin "3") (pinfunction "SDI_3") (pintype "unspecified"))
    )
    (net (code "119") (name "Net-(LED57-CKO)") (class "Default")
      (node (ref "LED57") (pin "6") (pinfunction "CKO_6") (pintype "unspecified"))
      (node (ref "LED58") (pin "4") (pinfunction "CKL_4") (pintype "unspecified"))
    )
    (net (code "120") (name "Net-(LED57-SDO)") (class "Default")
      (node (ref "LED57") (pin "1") (pinfunction "SDO_1") (pintype "unspecified"))
      (node (ref "LED58") (pin "3") (pinfunction "SDI_3") (pintype "unspecified"))
    )
    (net (code "121") (name "Net-(LED58-CKO)") (class "Default")
      (node (ref "LED58") (pin "6") (pinfunction "CKO_6") (pintype "unspecified"))
      (node (ref "LED59") (pin "4") (pinfunction "CKL_4") (pintype "unspecified"))
    )
    (net (code "122") (name "Net-(LED58-SDO)") (class "Default")
      (node (ref "LED58") (pin "1") (pinfunction "SDO_1") (pintype "unspecified"))
      (node (ref "LED59") (pin "3") (pinfunction "SDI_3") (pintype "unspecified"))
    )
    (net (code "123") (name "Net-(LED59-CKO)") (class "Default")
      (node (ref "LED59") (pin "6") (pinfunction "CKO_6") (pintype "unspecified"))
      (node (ref "LED60") (pin "4") (pinfunction "CKL_4") (pintype "unspecified"))
    )
    (net (code "124") (name "Net-(LED59-SDO)") (class "Default")
      (node (ref "LED59") (pin "1") (pinfunction "SDO_1") (pintype "unspecified"))
      (node (ref "LED60") (pin "3") (pinfunction "SDI_3") (pintype "unspecified"))
    )
    (net (code "125") (name "Net-(LED60-CKO)") (class "Default")
      (node (ref "LED60") (pin "6") (pinfunction "CKO_6") (pintype "unspecified"))
      (node (ref "LED72") (pin "4") (pinfunction "CKL_4") (pintype "unspecified"))
    )
    (net (code "126") (name "Net-(LED60-SDO)") (class "Default")
      (node (ref "LED60") (pin "1") (pinfunction "SDO_1") (pintype "unspecified"))
      (node (ref "LED72") (pin "3") (pinfunction "SDI_3") (pintype "unspecified"))
    )
    (net (code "127") (name "Net-(LED61-CKL)") (class "Default")
      (node (ref "LED61") (pin "4") (pinfunction "CKL_4") (pintype "unspecified"))
      (node (ref "LED62") (pin "6") (pinfunction "CKO_6") (pintype "unspecified"))
    )
    (net (code "128") (name "Net-(LED61-CKO)") (class "Default")
      (node (ref "LED61") (pin "6") (pinfunction "CKO_6") (pintype "unspecified"))
      (node (ref "LED73") (pin "4") (pinfunction "CKL_4") (pintype "unspecified"))
    )
    (net (code "129") (name "Net-(LED61-SDI)") (class "Default")
      (node (ref "LED61") (pin "3") (pinfunction "SDI_3") (pintype "unspecified"))
      (node (ref "LED62") (pin "1") (pinfunction "SDO_1") (pintype "unspecified"))
    )
    (net (code "130") (name "Net-(LED61-SDO)") (class "Default")
      (node (ref "LED61") (pin "1") (pinfunction "SDO_1") (pintype "unspecified"))
      (node (ref "LED73") (pin "3") (pinfunction "SDI_3") (pintype "unspecified"))
    )
    (net (code "131") (name "Net-(LED62-CKL)") (class "Default")
      (node (ref "LED62") (pin "4") (pinfunction "CKL_4") (pintype "unspecified"))
      (node (ref "LED63") (pin "6") (pinfunction "CKO_6") (pintype "unspecified"))
    )
    (net (code "132") (name "Net-(LED62-SDI)") (class "Default")
      (node (ref "LED62") (pin "3") (pinfunction "SDI_3") (pintype "unspecified"))
      (node (ref "LED63") (pin "1") (pinfunction "SDO_1") (pintype "unspecified"))
    )
    (net (code "133") (name "Net-(LED63-CKL)") (class "Default")
      (node (ref "LED63") (pin "4") (pinfunction "CKL_4") (pintype "unspecified"))
      (node (ref "LED64") (pin "6") (pinfunction "CKO_6") (pintype "unspecified"))
    )
    (net (code "134") (name "Net-(LED63-SDI)") (class "Default")
      (node (ref "LED63") (pin "3") (pinfunction "SDI_3") (pintype "unspecified"))
      (node (ref "LED64") (pin "1") (pinfunction "SDO_1") (pintype "unspecified"))
    )
    (net (code "135") (name "Net-(LED64-CKL)") (class "Default")
      (node (ref "LED64") (pin "4") (pinfunction "CKL_4") (pintype "unspecified"))
      (node (ref "LED65") (pin "6") (pinfunction "CKO_6") (pintype "unspecified"))
    )
    (net (code "136") (name "Net-(LED64-SDI)") (class "Default")
      (node (ref "LED64") (pin "3") (pinfunction "SDI_3") (pintype "unspecified"))
      (node (ref "LED65") (pin "1") (pinfunction "SDO_1") (pintype "unspecified"))
    )
    (net (code "137") (name "Net-(LED65-CKL)") (class "Default")
      (node (ref "LED65") (pin "4") (pinfunction "CKL_4") (pintype "unspecified"))
      (node (ref "LED66") (pin "6") (pinfunction "CKO_6") (pintype "unspecified"))
    )
    (net (code "138") (name "Net-(LED65-SDI)") (class "Default")
      (node (ref "LED65") (pin "3") (pinfunction "SDI_3") (pintype "unspecified"))
      (node (ref "LED66") (pin "1") (pinfunction "SDO_1") (pintype "unspecified"))
    )
    (net (code "139") (name "Net-(LED66-CKL)") (class "Default")
      (node (ref "LED66") (pin "4") (pinfunction "CKL_4") (pintype "unspecified"))
      (node (ref "LED67") (pin "6") (pinfunction "CKO_6") (pintype "unspecified"))
    )
    (net (code "140") (name "Net-(LED66-SDI)") (class "Default")
      (node (ref "LED66") (pin "3") (pinfunction "SDI_3") (pintype "unspecified"))
      (node (ref "LED67") (pin "1") (pinfunction "SDO_1") (pintype "unspecified"))
    )
    (net (code "141") (name "Net-(LED67-CKL)") (class "Default")
      (node (ref "LED67") (pin "4") (pinfunction "CKL_4") (pintype "unspecified"))
      (node (ref "LED68") (pin "6") (pinfunction "CKO_6") (pintype "unspecified"))
    )
    (net (code "142") (name "Net-(LED67-SDI)") (class "Default")
      (node (ref "LED67") (pin "3") (pinfunction "SDI_3") (pintype "unspecified"))
      (node (ref "LED68") (pin "1") (pinfunction "SDO_1") (pintype "unspecified"))
    )
    (net (code "143") (name "Net-(LED68-CKL)") (class "Default")
      (node (ref "LED68") (pin "4") (pinfunction "CKL_4") (pintype "unspecified"))
      (node (ref "LED69") (pin "6") (pinfunction "CKO_6") (pintype "unspecified"))
    )
    (net (code "144") (name "Net-(LED68-SDI)") (class "Default")
      (node (ref "LED68") (pin "3") (pinfunction "SDI_3") (pintype "unspecified"))
      (node (ref "LED69") (pin "1") (pinfunction "SDO_1") (pintype "unspecified"))
    )
    (net (code "145") (name "Net-(LED69-CKL)") (class "Default")
      (node (ref "LED69") (pin "4") (pinfunction "CKL_4") (pintype "unspecified"))
      (node (ref "LED70") (pin "6") (pinfunction "CKO_6") (pintype "unspecified"))
    )
    (net (code "146") (name "Net-(LED69-SDI)") (class "Default")
      (node (ref "LED69") (pin "3") (pinfunction "SDI_3") (pintype "unspecified"))
      (node (ref "LED70") (pin "1") (pinfunction "SDO_1") (pintype "unspecified"))
    )
    (net (code "147") (name "Net-(LED70-CKL)") (class "Default")
      (node (ref "LED70") (pin "4") (pinfunction "CKL_4") (pintype "unspecified"))
      (node (ref "LED71") (pin "6") (pinfunction "CKO_6") (pintype "unspecified"))
    )
    (net (code "148") (name "Net-(LED70-SDI)") (class "Default")
      (node (ref "LED70") (pin "3") (pinfunction "SDI_3") (pintype "unspecified"))
      (node (ref "LED71") (pin "1") (pinfunction "SDO_1") (pintype "unspecified"))
    )
    (net (code "149") (name "Net-(LED71-CKL)") (class "Default")
      (node (ref "LED71") (pin "4") (pinfunction "CKL_4") (pintype "unspecified"))
      (node (ref "LED72") (pin "6") (pinfunction "CKO_6") (pintype "unspecified"))
    )
    (net (code "150") (name "Net-(LED71-SDI)") (class "Default")
      (node (ref "LED71") (pin "3") (pinfunction "SDI_3") (pintype "unspecified"))
      (node (ref "LED72") (pin "1") (pinfunction "SDO_1") (pintype "unspecified"))
    )
    (net (code "151") (name "Net-(LED73-CKO)") (class "Default")
      (node (ref "LED73") (pin "6") (pinfunction "CKO_6") (pintype "unspecified"))
      (node (ref "LED74") (pin "4") (pinfunction "CKL_4") (pintype "unspecified"))
    )
    (net (code "152") (name "Net-(LED73-SDO)") (class "Default")
      (node (ref "LED73") (pin "1") (pinfunction "SDO_1") (pintype "unspecified"))
      (node (ref "LED74") (pin "3") (pinfunction "SDI_3") (pintype "unspecified"))
    )
    (net (code "153") (name "Net-(LED74-CKO)") (class "Default")
      (node (ref "LED74") (pin "6") (pinfunction "CKO_6") (pintype "unspecified"))
      (node (ref "LED75") (pin "4") (pinfunction "CKL_4") (pintype "unspecified"))
    )
    (net (code "154") (name "Net-(LED74-SDO)") (class "Default")
      (node (ref "LED74") (pin "1") (pinfunction "SDO_1") (pintype "unspecified"))
      (node (ref "LED75") (pin "3") (pinfunction "SDI_3") (pintype "unspecified"))
    )
    (net (code "155") (name "Net-(LED75-CKO)") (class "Default")
      (node (ref "LED75") (pin "6") (pinfunction "CKO_6") (pintype "unspecified"))
      (node (ref "LED76") (pin "4") (pinfunction "CKL_4") (pintype "unspecified"))
    )
    (net (code "156") (name "Net-(LED75-SDO)") (class "Default")
      (node (ref "LED75") (pin "1") (pinfunction "SDO_1") (pintype "unspecified"))
      (node (ref "LED76") (pin "3") (pinfunction "SDI_3") (pintype "unspecified"))
    )
    (net (code "157") (name "Net-(LED76-CKO)") (class "Default")
      (node (ref "LED76") (pin "6") (pinfunction "CKO_6") (pintype "unspecified"))
      (node (ref "LED77") (pin "4") (pinfunction "CKL_4") (pintype "unspecified"))
    )
    (net (code "158") (name "Net-(LED76-SDO)") (class "Default")
      (node (ref "LED76") (pin "1") (pinfunction "SDO_1") (pintype "unspecified"))
      (node (ref "LED77") (pin "3") (pinfunction "SDI_3") (pintype "unspecified"))
    )
    (net (code "159") (name "Net-(LED77-CKO)") (class "Default")
      (node (ref "LED77") (pin "6") (pinfunction "CKO_6") (pintype "unspecified"))
      (node (ref "LED78") (pin "4") (pinfunction "CKL_4") (pintype "unspecified"))
    )
    (net (code "160") (name "Net-(LED77-SDO)") (class "Default")
      (node (ref "LED77") (pin "1") (pinfunction "SDO_1") (pintype "unspecified"))
      (node (ref "LED78") (pin "3") (pinfunction "SDI_3") (pintype "unspecified"))
    )
    (net (code "161") (name "Net-(LED78-CKO)") (class "Default")
      (node (ref "LED78") (pin "6") (pinfunction "CKO_6") (pintype "unspecified"))
      (node (ref "LED79") (pin "4") (pinfunction "CKL_4") (pintype "unspecified"))
    )
    (net (code "162") (name "Net-(LED78-SDO)") (class "Default")
      (node (ref "LED78") (pin "1") (pinfunction "SDO_1") (pintype "unspecified"))
      (node (ref "LED79") (pin "3") (pinfunction "SDI_3") (pintype "unspecified"))
    )
    (net (code "163") (name "Net-(LED79-CKO)") (class "Default")
      (node (ref "LED79") (pin "6") (pinfunction "CKO_6") (pintype "unspecified"))
      (node (ref "LED80") (pin "4") (pinfunction "CKL_4") (pintype "unspecified"))
    )
    (net (code "164") (name "Net-(LED79-SDO)") (class "Default")
      (node (ref "LED79") (pin "1") (pinfunction "SDO_1") (pintype "unspecified"))
      (node (ref "LED80") (pin "3") (pinfunction "SDI_3") (pintype "unspecified"))
    )
    (net (code "165") (name "Net-(LED80-CKO)") (class "Default")
      (node (ref "LED80") (pin "6") (pinfunction "CKO_6") (pintype "unspecified"))
      (node (ref "LED81") (pin "4") (pinfunction "CKL_4") (pintype "unspecified"))
    )
    (net (code "166") (name "Net-(LED80-SDO)") (class "Default")
      (node (ref "LED80") (pin "1") (pinfunction "SDO_1") (pintype "unspecified"))
      (node (ref "LED81") (pin "3") (pinfunction "SDI_3") (pintype "unspecified"))
    )
    (net (code "167") (name "Net-(LED81-CKO)") (class "Default")
      (node (ref "LED81") (pin "6") (pinfunction "CKO_6") (pintype "unspecified"))
      (node (ref "LED82") (pin "4") (pinfunction "CKL_4") (pintype "unspecified"))
    )
    (net (code "168") (name "Net-(LED81-SDO)") (class "Default")
      (node (ref "LED81") (pin "1") (pinfunction "SDO_1") (pintype "unspecified"))
      (node (ref "LED82") (pin "3") (pinfunction "SDI_3") (pintype "unspecified"))
    )
    (net (code "169") (name "Net-(LED82-CKO)") (class "Default")
      (node (ref "LED82") (pin "6") (pinfunction "CKO_6") (pintype "unspecified"))
      (node (ref "LED83") (pin "4") (pinfunction "CKL_4") (pintype "unspecified"))
    )
    (net (code "170") (name "Net-(LED82-SDO)") (class "Default")
      (node (ref "LED82") (pin "1") (pinfunction "SDO_1") (pintype "unspecified"))
      (node (ref "LED83") (pin "3") (pinfunction "SDI_3") (pintype "unspecified"))
    )
    (net (code "171") (name "Net-(LED83-CKO)") (class "Default")
      (node (ref "LED83") (pin "6") (pinfunction "CKO_6") (pintype "unspecified"))
      (node (ref "LED84") (pin "4") (pinfunction "CKL_4") (pintype "unspecified"))
    )
    (net (code "172") (name "Net-(LED83-SDO)") (class "Default")
      (node (ref "LED83") (pin "1") (pinfunction "SDO_1") (pintype "unspecified"))
      (node (ref "LED84") (pin "3") (pinfunction "SDI_3") (pintype "unspecified"))
    )
    (net (code "173") (name "Net-(LED84-CKO)") (class "Default")
      (node (ref "LED84") (pin "6") (pinfunction "CKO_6") (pintype "unspecified"))
      (node (ref "LED96") (pin "4") (pinfunction "CKL_4") (pintype "unspecified"))
    )
    (net (code "174") (name "Net-(LED84-SDO)") (class "Default")
      (node (ref "LED84") (pin "1") (pinfunction "SDO_1") (pintype "unspecified"))
      (node (ref "LED96") (pin "3") (pinfunction "SDI_3") (pintype "unspecified"))
    )
    (net (code "175") (name "Net-(LED85-CKL)") (class "Default")
      (node (ref "LED85") (pin "4") (pinfunction "CKL_4") (pintype "unspecified"))
      (node (ref "LED86") (pin "6") (pinfunction "CKO_6") (pintype "unspecified"))
    )
    (net (code "176") (name "Net-(LED85-CKO)") (class "Default")
      (node (ref "LED85") (pin "6") (pinfunction "CKO_6") (pintype "unspecified"))
      (node (ref "LED97") (pin "4") (pinfunction "CKL_4") (pintype "unspecified"))
    )
    (net (code "177") (name "Net-(LED85-SDI)") (class "Default")
      (node (ref "LED85") (pin "3") (pinfunction "SDI_3") (pintype "unspecified"))
      (node (ref "LED86") (pin "1") (pinfunction "SDO_1") (pintype "unspecified"))
    )
    (net (code "178") (name "Net-(LED85-SDO)") (class "Default")
      (node (ref "LED85") (pin "1") (pinfunction "SDO_1") (pintype "unspecified"))
      (node (ref "LED97") (pin "3") (pinfunction "SDI_3") (pintype "unspecified"))
    )
    (net (code "179") (name "Net-(LED86-CKL)") (class "Default")
      (node (ref "LED86") (pin "4") (pinfunction "CKL_4") (pintype "unspecified"))
      (node (ref "LED87") (pin "6") (pinfunction "CKO_6") (pintype "unspecified"))
    )
    (net (code "180") (name "Net-(LED86-SDI)") (class "Default")
      (node (ref "LED86") (pin "3") (pinfunction "SDI_3") (pintype "unspecified"))
      (node (ref "LED87") (pin "1") (pinfunction "SDO_1") (pintype "unspecified"))
    )
    (net (code "181") (name "Net-(LED87-CKL)") (class "Default")
      (node (ref "LED87") (pin "4") (pinfunction "CKL_4") (pintype "unspecified"))
      (node (ref "LED88") (pin "6") (pinfunction "CKO_6") (pintype "unspecified"))
    )
    (net (code "182") (name "Net-(LED87-SDI)") (class "Default")
      (node (ref "LED87") (pin "3") (pinfunction "SDI_3") (pintype "unspecified"))
      (node (ref "LED88") (pin "1") (pinfunction "SDO_1") (pintype "unspecified"))
    )
    (net (code "183") (name "Net-(LED88-CKL)") (class "Default")
      (node (ref "LED88") (pin "4") (pinfunction "CKL_4") (pintype "unspecified"))
      (node (ref "LED89") (pin "6") (pinfunction "CKO_6") (pintype "unspecified"))
    )
    (net (code "184") (name "Net-(LED88-SDI)") (class "Default")
      (node (ref "LED88") (pin "3") (pinfunction "SDI_3") (pintype "unspecified"))
      (node (ref "LED89") (pin "1") (pinfunction "SDO_1") (pintype "unspecified"))
    )
    (net (code "185") (name "Net-(LED89-CKL)") (class "Default")
      (node (ref "LED89") (pin "4") (pinfunction "CKL_4") (pintype "unspecified"))
      (node (ref "LED90") (pin "6") (pinfunction "CKO_6") (pintype "unspecified"))
    )
    (net (code "186") (name "Net-(LED89-SDI)") (class "Default")
      (node (ref "LED89") (pin "3") (pinfunction "SDI_3") (pintype "unspecified"))
      (node (ref "LED90") (pin "1") (pinfunction "SDO_1") (pintype "unspecified"))
    )
    (net (code "187") (name "Net-(LED90-CKL)") (class "Default")
      (node (ref "LED90") (pin "4") (pinfunction "CKL_4") (pintype "unspecified"))
      (node (ref "LED91") (pin "6") (pinfunction "CKO_6") (pintype "unspecified"))
    )
    (net (code "188") (name "Net-(LED90-SDI)") (class "Default")
      (node (ref "LED90") (pin "3") (pinfunction "SDI_3") (pintype "unspecified"))
      (node (ref "LED91") (pin "1") (pinfunction "SDO_1") (pintype "unspecified"))
    )
    (net (code "189") (name "Net-(LED91-CKL)") (class "Default")
      (node (ref "LED91") (pin "4") (pinfunction "CKL_4") (pintype "unspecified"))
      (node (ref "LED92") (pin "6") (pinfunction "CKO_6") (pintype "unspecified"))
    )
    (net (code "190") (name "Net-(LED91-SDI)") (class "Default")
      (node (ref "LED91") (pin "3") (pinfunction "SDI_3") (pintype "unspecified"))
      (node (ref "LED92") (pin "1") (pinfunction "SDO_1") (pintype "unspecified"))
    )
    (net (code "191") (name "Net-(LED92-CKL)") (class "Default")
      (node (ref "LED92") (pin "4") (pinfunction "CKL_4") (pintype "unspecified"))
      (node (ref "LED93") (pin "6") (pinfunction "CKO_6") (pintype "unspecified"))
    )
    (net (code "192") (name "Net-(LED92-SDI)") (class "Default")
      (node (ref "LED92") (pin "3") (pinfunction "SDI_3") (pintype "unspecified"))
      (node (ref "LED93") (pin "1") (pinfunction "SDO_1") (pintype "unspecified"))
    )
    (net (code "193") (name "Net-(LED93-CKL)") (class "Default")
      (node (ref "LED93") (pin "4") (pinfunction "CKL_4") (pintype "unspecified"))
      (node (ref "LED94") (pin "6") (pinfunction "CKO_6") (pintype "unspecified"))
    )
    (net (code "194") (name "Net-(LED93-SDI)") (class "Default")
      (node (ref "LED93") (pin "3") (pinfunction "SDI_3") (pintype "unspecified"))
      (node (ref "LED94") (pin "1") (pinfunction "SDO_1") (pintype "unspecified"))
    )
    (net (code "195") (name "Net-(LED94-CKL)") (class "Default")
      (node (ref "LED94") (pin "4") (pinfunction "CKL_4") (pintype "unspecified"))
      (node (ref "LED95") (pin "6") (pinfunction "CKO_6") (pintype "unspecified"))
    )
    (net (code "196") (name "Net-(LED94-SDI)") (class "Default")
      (node (ref "LED94") (pin "3") (pinfunction "SDI_3") (pintype "unspecified"))
      (node (ref "LED95") (pin "1") (pinfunction "SDO_1") (pintype "unspecified"))
    )
    (net (code "197") (name "Net-(LED95-CKL)") (class "Default")
      (node (ref "LED95") (pin "4") (pinfunction "CKL_4") (pintype "unspecified"))
      (node (ref "LED96") (pin "6") (pinfunction "CKO_6") (pintype "unspecified"))
    )
    (net (code "198") (name "Net-(LED95-SDI)") (class "Default")
      (node (ref "LED95") (pin "3") (pinfunction "SDI_3") (pintype "unspecified"))
      (node (ref "LED96") (pin "1") (pinfunction "SDO_1") (pintype "unspecified"))
    )
    (net (code "199") (name "Net-(LED97-CKO)") (class "Default")
      (node (ref "LED97") (pin "6") (pinfunction "CKO_6") (pintype "unspecified"))
      (node (ref "LED98") (pin "4") (pinfunction "CKL_4") (pintype "unspecified"))
    )
    (net (code "200") (name "Net-(LED97-SDO)") (class "Default")
      (node (ref "LED97") (pin "1") (pinfunction "SDO_1") (pintype "unspecified"))
      (node (ref "LED98") (pin "3") (pinfunction "SDI_3") (pintype "unspecified"))
    )
    (net (code "201") (name "Net-(LED98-CKO)") (class "Default")
      (node (ref "LED98") (pin "6") (pinfunction "CKO_6") (pintype "unspecified"))
      (node (ref "LED99") (pin "4") (pinfunction "CKL_4") (pintype "unspecified"))
    )
    (net (code "202") (name "Net-(LED98-SDO)") (class "Default")
      (node (ref "LED98") (pin "1") (pinfunction "SDO_1") (pintype "unspecified"))
      (node (ref "LED99") (pin "3") (pinfunction "SDI_3") (pintype "unspecified"))
    )
    (net (code "203") (name "Net-(LED100-CKL)") (class "Default")
      (node (ref "LED100") (pin "4") (pinfunction "CKL_4") (pintype "unspecified"))
      (node (ref "LED99") (pin "6") (pinfunction "CKO_6") (pintype "unspecified"))
    )
    (net (code "204") (name "Net-(LED100-CKO)") (class "Default")
      (node (ref "LED100") (pin "6") (pinfunction "CKO_6") (pintype "unspecified"))
      (node (ref "LED101") (pin "4") (pinfunction "CKL_4") (pintype "unspecified"))
    )
    (net (code "205") (name "Net-(LED100-SDI)") (class "Default")
      (node (ref "LED100") (pin "3") (pinfunction "SDI_3") (pintype "unspecified"))
      (node (ref "LED99") (pin "1") (pinfunction "SDO_1") (pintype "unspecified"))
    )
    (net (code "206") (name "Net-(LED100-SDO)") (class "Default")
      (node (ref "LED100") (pin "1") (pinfunction "SDO_1") (pintype "unspecified"))
      (node (ref "LED101") (pin "3") (pinfunction "SDI_3") (pintype "unspecified"))
    )
    (net (code "207") (name "Net-(LED101-CKO)") (class "Default")
      (node (ref "LED101") (pin "6") (pinfunction "CKO_6") (pintype "unspecified"))
      (node (ref "LED102") (pin "4") (pinfunction "CKL_4") (pintype "unspecified"))
    )
    (net (code "208") (name "Net-(LED101-SDO)") (class "Default")
      (node (ref "LED101") (pin "1") (pinfunction "SDO_1") (pintype "unspecified"))
      (node (ref "LED102") (pin "3") (pinfunction "SDI_3") (pintype "unspecified"))
    )
    (net (code "209") (name "Net-(LED102-CKO)") (class "Default")
      (node (ref "LED102") (pin "6") (pinfunction "CKO_6") (pintype "unspecified"))
      (node (ref "LED103") (pin "4") (pinfunction "CKL_4") (pintype "unspecified"))
    )
    (net (code "210") (name "Net-(LED102-SDO)") (class "Default")
      (node (ref "LED102") (pin "1") (pinfunction "SDO_1") (pintype "unspecified"))
      (node (ref "LED103") (pin "3") (pinfunction "SDI_3") (pintype "unspecified"))
    )
    (net (code "211") (name "Net-(LED103-CKO)") (class "Default")
      (node (ref "LED103") (pin "6") (pinfunction "CKO_6") (pintype "unspecified"))
      (node (ref "LED104") (pin "4") (pinfunction "CKL_4") (pintype "unspecified"))
    )
    (net (code "212") (name "Net-(LED103-SDO)") (class "Default")
      (node (ref "LED103") (pin "1") (pinfunction "SDO_1") (pintype "unspecified"))
      (node (ref "LED104") (pin "3") (pinfunction "SDI_3") (pintype "unspecified"))
    )
    (net (code "213") (name "Net-(LED104-CKO)") (class "Default")
      (node (ref "LED104") (pin "6") (pinfunction "CKO_6") (pintype "unspecified"))
      (node (ref "LED105") (pin "4") (pinfunction "CKL_4") (pintype "unspecified"))
    )
    (net (code "214") (name "Net-(LED104-SDO)") (class "Default")
      (node (ref "LED104") (pin "1") (pinfunction "SDO_1") (pintype "unspecified"))
      (node (ref "LED105") (pin "3") (pinfunction "SDI_3") (pintype "unspecified"))
    )
    (net (code "215") (name "Net-(LED105-CKO)") (class "Default")
      (node (ref "LED105") (pin "6") (pinfunction "CKO_6") (pintype "unspecified"))
      (node (ref "LED106") (pin "4") (pinfunction "CKL_4") (pintype "unspecified"))
    )
    (net (code "216") (name "Net-(LED105-SDO)") (class "Default")
      (node (ref "LED105") (pin "1") (pinfunction "SDO_1") (pintype "unspecified"))
      (node (ref "LED106") (pin "3") (pinfunction "SDI_3") (pintype "unspecified"))
    )
    (net (code "217") (name "Net-(LED106-CKO)") (class "Default")
      (node (ref "LED106") (pin "6") (pinfunction "CKO_6") (pintype "unspecified"))
      (node (ref "LED107") (pin "4") (pinfunction "CKL_4") (pintype "unspecified"))
    )
    (net (code "218") (name "Net-(LED106-SDO)") (class "Default")
      (node (ref "LED106") (pin "1") (pinfunction "SDO_1") (pintype "unspecified"))
      (node (ref "LED107") (pin "3") (pinfunction "SDI_3") (pintype "unspecified"))
    )
    (net (code "219") (name "Net-(LED107-CKO)") (class "Default")
      (node (ref "LED107") (pin "6") (pinfunction "CKO_6") (pintype "unspecified"))
      (node (ref "LED108") (pin "4") (pinfunction "CKL_4") (pintype "unspecified"))
    )
    (net (code "220") (name "Net-(LED107-SDO)") (class "Default")
      (node (ref "LED107") (pin "1") (pinfunction "SDO_1") (pintype "unspecified"))
      (node (ref "LED108") (pin "3") (pinfunction "SDI_3") (pintype "unspecified"))
    )
    (net (code "221") (name "Net-(LED108-CKO)") (class "Default")
      (node (ref "LED108") (pin "6") (pinfunction "CKO_6") (pintype "unspecified"))
      (node (ref "LED120") (pin "4") (pinfunction "CKL_4") (pintype "unspecified"))
    )
    (net (code "222") (name "Net-(LED108-SDO)") (class "Default")
      (node (ref "LED108") (pin "1") (pinfunction "SDO_1") (pintype "unspecified"))
      (node (ref "LED120") (pin "3") (pinfunction "SDI_3") (pintype "unspecified"))
    )
    (net (code "223") (name "Net-(LED109-CKL)") (class "Default")
      (node (ref "LED109") (pin "4") (pinfunction "CKL_4") (pintype "unspecified"))
      (node (ref "LED110") (pin "6") (pinfunction "CKO_6") (pintype "unspecified"))
    )
    (net (code "224") (name "Net-(LED109-CKO)") (class "Default")
      (node (ref "LED109") (pin "6") (pinfunction "CKO_6") (pintype "unspecified"))
      (node (ref "LED121") (pin "4") (pinfunction "CKL_4") (pintype "unspecified"))
    )
    (net (code "225") (name "Net-(LED109-SDI)") (class "Default")
      (node (ref "LED109") (pin "3") (pinfunction "SDI_3") (pintype "unspecified"))
      (node (ref "LED110") (pin "1") (pinfunction "SDO_1") (pintype "unspecified"))
    )
    (net (code "226") (name "Net-(LED109-SDO)") (class "Default")
      (node (ref "LED109") (pin "1") (pinfunction "SDO_1") (pintype "unspecified"))
      (node (ref "LED121") (pin "3") (pinfunction "SDI_3") (pintype "unspecified"))
    )
    (net (code "227") (name "Net-(LED110-CKL)") (class "Default")
      (node (ref "LED110") (pin "4") (pinfunction "CKL_4") (pintype "unspecified"))
      (node (ref "LED111") (pin "6") (pinfunction "CKO_6") (pintype "unspecified"))
    )
    (net (code "228") (name "Net-(LED110-SDI)") (class "Default")
      (node (ref "LED110") (pin "3") (pinfunction "SDI_3") (pintype "unspecified"))
      (node (ref "LED111") (pin "1") (pinfunction "SDO_1") (pintype "unspecified"))
    )
    (net (code "229") (name "Net-(LED111-CKL)") (class "Default")
      (node (ref "LED111") (pin "4") (pinfunction "CKL_4") (pintype "unspecified"))
      (node (ref "LED112") (pin "6") (pinfunction "CKO_6") (pintype "unspecified"))
    )
    (net (code "230") (name "Net-(LED111-SDI)") (class "Default")
      (node (ref "LED111") (pin "3") (pinfunction "SDI_3") (pintype "unspecified"))
      (node (ref "LED112") (pin "1") (pinfunction "SDO_1") (pintype "unspecified"))
    )
    (net (code "231") (name "Net-(LED112-CKL)") (class "Default")
      (node (ref "LED112") (pin "4") (pinfunction "CKL_4") (pintype "unspecified"))
      (node (ref "LED113") (pin "6") (pinfunction "CKO_6") (pintype "unspecified"))
    )
    (net (code "232") (name "Net-(LED112-SDI)") (class "Default")
      (node (ref "LED112") (pin "3") (pinfunction "SDI_3") (pintype "unspecified"))
      (node (ref "LED113") (pin "1") (pinfunction "SDO_1") (pintype "unspecified"))
    )
    (net (code "233") (name "Net-(LED113-CKL)") (class "Default")
      (node (ref "LED113") (pin "4") (pinfunction "CKL_4") (pintype "unspecified"))
      (node (ref "LED114") (pin "6") (pinfunction "CKO_6") (pintype "unspecified"))
    )
    (net (code "234") (name "Net-(LED113-SDI)") (class "Default")
      (node (ref "LED113") (pin "3") (pinfunction "SDI_3") (pintype "unspecified"))
      (node (ref "LED114") (pin "1") (pinfunction "SDO_1") (pintype "unspecified"))
    )
    (net (code "235") (name "Net-(LED114-CKL)") (class "Default")
      (node (ref "LED114") (pin "4") (pinfunction "CKL_4") (pintype "unspecified"))
      (node (ref "LED115") (pin "6") (pinfunction "CKO_6") (pintype "unspecified"))
    )
    (net (code "236") (name "Net-(LED114-SDI)") (class "Default")
      (node (ref "LED114") (pin "3") (pinfunction "SDI_3") (pintype "unspecified"))
      (node (ref "LED115") (pin "1") (pinfunction "SDO_1") (pintype "unspecified"))
    )
    (net (code "237") (name "Net-(LED115-CKL)") (class "Default")
      (node (ref "LED115") (pin "4") (pinfunction "CKL_4") (pintype "unspecified"))
      (node (ref "LED116") (pin "6") (pinfunction "CKO_6") (pintype "unspecified"))
    )
    (net (code "238") (name "Net-(LED115-SDI)") (class "Default")
      (node (ref "LED115") (pin "3") (pinfunction "SDI_3") (pintype "unspecified"))
      (node (ref "LED116") (pin "1") (pinfunction "SDO_1") (pintype "unspecified"))
    )
    (net (code "239") (name "Net-(LED116-CKL)") (class "Default")
      (node (ref "LED116") (pin "4") (pinfunction "CKL_4") (pintype "unspecified"))
      (node (ref "LED117") (pin "6") (pinfunction "CKO_6") (pintype "unspecified"))
    )
    (net (code "240") (name "Net-(LED116-SDI)") (class "Default")
      (node (ref "LED116") (pin "3") (pinfunction "SDI_3") (pintype "unspecified"))
      (node (ref "LED117") (pin "1") (pinfunction "SDO_1") (pintype "unspecified"))
    )
    (net (code "241") (name "Net-(LED117-CKL)") (class "Default")
      (node (ref "LED117") (pin "4") (pinfunction "CKL_4") (pintype "unspecified"))
      (node (ref "LED118") (pin "6") (pinfunction "CKO_6") (pintype "unspecified"))
    )
    (net (code "242") (name "Net-(LED117-SDI)") (class "Default")
      (node (ref "LED117") (pin "3") (pinfunction "SDI_3") (pintype "unspecified"))
      (node (ref "LED118") (pin "1") (pinfunction "SDO_1") (pintype "unspecified"))
    )
    (net (code "243") (name "Net-(LED118-CKL)") (class "Default")
      (node (ref "LED118") (pin "4") (pinfunction "CKL_4") (pintype "unspecified"))
      (node (ref "LED119") (pin "6") (pinfunction "CKO_6") (pintype "unspecified"))
    )
    (net (code "244") (name "Net-(LED118-SDI)") (class "Default")
      (node (ref "LED118") (pin "3") (pinfunction "SDI_3") (pintype "unspecified"))
      (node (ref "LED119") (pin "1") (pinfunction "SDO_1") (pintype "unspecified"))
    )
    (net (code "245") (name "Net-(LED119-CKL)") (class "Default")
      (node (ref "LED119") (pin "4") (pinfunction "CKL_4") (pintype "unspecified"))
      (node (ref "LED120") (pin "6") (pinfunction "CKO_6") (pintype "unspecified"))
    )
    (net (code "246") (name "Net-(LED119-SDI)") (class "Default")
      (node (ref "LED119") (pin "3") (pinfunction "SDI_3") (pintype "unspecified"))
      (node (ref "LED120") (pin "1") (pinfunction "SDO_1") (pintype "unspecified"))
    )
    (net (code "247") (name "Net-(LED121-CKO)") (class "Default")
      (node (ref "LED121") (pin "6") (pinfunction "CKO_6") (pintype "unspecified"))
      (node (ref "LED122") (pin "4") (pinfunction "CKL_4") (pintype "unspecified"))
    )
    (net (code "248") (name "Net-(LED121-SDO)") (class "Default")
      (node (ref "LED121") (pin "1") (pinfunction "SDO_1") (pintype "unspecified"))
      (node (ref "LED122") (pin "3") (pinfunction "SDI_3") (pintype "unspecified"))
    )
    (net (code "249") (name "Net-(LED122-CKO)") (class "Default")
      (node (ref "LED122") (pin "6") (pinfunction "CKO_6") (pintype "unspecified"))
      (node (ref "LED123") (pin "4") (pinfunction "CKL_4") (pintype "unspecified"))
    )
    (net (code "250") (name "Net-(LED122-SDO)") (class "Default")
      (node (ref "LED122") (pin "1") (pinfunction "SDO_1") (pintype "unspecified"))
      (node (ref "LED123") (pin "3") (pinfunction "SDI_3") (pintype "unspecified"))
    )
    (net (code "251") (name "Net-(LED123-CKO)") (class "Default")
      (node (ref "LED123") (pin "6") (pinfunction "CKO_6") (pintype "unspecified"))
      (node (ref "LED124") (pin "4") (pinfunction "CKL_4") (pintype "unspecified"))
    )
    (net (code "252") (name "Net-(LED123-SDO)") (class "Default")
      (node (ref "LED123") (pin "1") (pinfunction "SDO_1") (pintype "unspecified"))
      (node (ref "LED124") (pin "3") (pinfunction "SDI_3") (pintype "unspecified"))
    )
    (net (code "253") (name "Net-(LED124-CKO)") (class "Default")
      (node (ref "LED124") (pin "6") (pinfunction "CKO_6") (pintype "unspecified"))
      (node (ref "LED125") (pin "4") (pinfunction "CKL_4") (pintype "unspecified"))
    )
    (net (code "254") (name "Net-(LED124-SDO)") (class "Default")
      (node (ref "LED124") (pin "1") (pinfunction "SDO_1") (pintype "unspecified"))
      (node (ref "LED125") (pin "3") (pinfunction "SDI_3") (pintype "unspecified"))
    )
    (net (code "255") (name "Net-(LED125-CKO)") (class "Default")
      (node (ref "LED125") (pin "6") (pinfunction "CKO_6") (pintype "unspecified"))
      (node (ref "LED126") (pin "4") (pinfunction "CKL_4") (pintype "unspecified"))
    )
    (net (code "256") (name "Net-(LED125-SDO)") (class "Default")
      (node (ref "LED125") (pin "1") (pinfunction "SDO_1") (pintype "unspecified"))
      (node (ref "LED126") (pin "3") (pinfunction "SDI_3") (pintype "unspecified"))
    )
    (net (code "257") (name "Net-(LED126-CKO)") (class "Default")
      (node (ref "LED126") (pin "6") (pinfunction "CKO_6") (pintype "unspecified"))
      (node (ref "LED127") (pin "4") (pinfunction "CKL_4") (pintype "unspecified"))
    )
    (net (code "258") (name "Net-(LED126-SDO)") (class "Default")
      (node (ref "LED126") (pin "1") (pinfunction "SDO_1") (pintype "unspecified"))
      (node (ref "LED127") (pin "3") (pinfunction "SDI_3") (pintype "unspecified"))
    )
    (net (code "259") (name "Net-(LED127-CKO)") (class "Default")
      (node (ref "LED127") (pin "6") (pinfunction "CKO_6") (pintype "unspecified"))
      (node (ref "LED128") (pin "4") (pinfunction "CKL_4") (pintype "unspecified"))
    )
    (net (code "260") (name "Net-(LED127-SDO)") (class "Default")
      (node (ref "LED127") (pin "1") (pinfunction "SDO_1") (pintype "unspecified"))
      (node (ref "LED128") (pin "3") (pinfunction "SDI_3") (pintype "unspecified"))
    )
    (net (code "261") (name "Net-(LED128-CKO)") (class "Default")
      (node (ref "LED128") (pin "6") (pinfunction "CKO_6") (pintype "unspecified"))
      (node (ref "LED129") (pin "4") (pinfunction "CKL_4") (pintype "unspecified"))
    )
    (net (code "262") (name "Net-(LED128-SDO)") (class "Default")
      (node (ref "LED128") (pin "1") (pinfunction "SDO_1") (pintype "unspecified"))
      (node (ref "LED129") (pin "3") (pinfunction "SDI_3") (pintype "unspecified"))
    )
    (net (code "263") (name "Net-(LED129-CKO)") (class "Default")
      (node (ref "LED129") (pin "6") (pinfunction "CKO_6") (pintype "unspecified"))
      (node (ref "LED130") (pin "4") (pinfunction "CKL_4") (pintype "unspecified"))
    )
    (net (code "264") (name "Net-(LED129-SDO)") (class "Default")
      (node (ref "LED129") (pin "1") (pinfunction "SDO_1") (pintype "unspecified"))
      (node (ref "LED130") (pin "3") (pinfunction "SDI_3") (pintype "unspecified"))
    )
    (net (code "265") (name "Net-(LED130-CKO)") (class "Default")
      (node (ref "LED130") (pin "6") (pinfunction "CKO_6") (pintype "unspecified"))
      (node (ref "LED131") (pin "4") (pinfunction "CKL_4") (pintype "unspecified"))
    )
    (net (code "266") (name "Net-(LED130-SDO)") (class "Default")
      (node (ref "LED130") (pin "1") (pinfunction "SDO_1") (pintype "unspecified"))
      (node (ref "LED131") (pin "3") (pinfunction "SDI_3") (pintype "unspecified"))
    )
    (net (code "267") (name "Net-(LED131-CKO)") (class "Default")
      (node (ref "LED131") (pin "6") (pinfunction "CKO_6") (pintype "unspecified"))
      (node (ref "LED132") (pin "4") (pinfunction "CKL_4") (pintype "unspecified"))
    )
    (net (code "268") (name "Net-(LED131-SDO)") (class "Default")
      (node (ref "LED131") (pin "1") (pinfunction "SDO_1") (pintype "unspecified"))
      (node (ref "LED132") (pin "3") (pinfunction "SDI_3") (pintype "unspecified"))
    )
    (net (code "269") (name "Net-(LED132-CKO)") (class "Default")
      (node (ref "LED132") (pin "6") (pinfunction "CKO_6") (pintype "unspecified"))
      (node (ref "LED144") (pin "4") (pinfunction "CKL_4") (pintype "unspecified"))
    )
    (net (code "270") (name "Net-(LED132-SDO)") (class "Default")
      (node (ref "LED132") (pin "1") (pinfunction "SDO_1") (pintype "unspecified"))
      (node (ref "LED144") (pin "3") (pinfunction "SDI_3") (pintype "unspecified"))
    )
    (net (code "271") (name "Net-(LED133-CKL)") (class "Default")
      (node (ref "LED133") (pin "4") (pinfunction "CKL_4") (pintype "unspecified"))
      (node (ref "LED134") (pin "6") (pinfunction "CKO_6") (pintype "unspecified"))
    )
    (net (code "272") (name "Net-(LED133-CKO)") (class "Default")
      (node (ref "LED133") (pin "6") (pinfunction "CKO_6") (pintype "unspecified"))
      (node (ref "LED145") (pin "4") (pinfunction "CKL_4") (pintype "unspecified"))
    )
    (net (code "273") (name "Net-(LED133-SDI)") (class "Default")
      (node (ref "LED133") (pin "3") (pinfunction "SDI_3") (pintype "unspecified"))
      (node (ref "LED134") (pin "1") (pinfunction "SDO_1") (pintype "unspecified"))
    )
    (net (code "274") (name "Net-(LED133-SDO)") (class "Default")
      (node (ref "LED133") (pin "1") (pinfunction "SDO_1") (pintype "unspecified"))
      (node (ref "LED145") (pin "3") (pinfunction "SDI_3") (pintype "unspecified"))
    )
    (net (code "275") (name "Net-(LED134-CKL)") (class "Default")
      (node (ref "LED134") (pin "4") (pinfunction "CKL_4") (pintype "unspecified"))
      (node (ref "LED135") (pin "6") (pinfunction "CKO_6") (pintype "unspecified"))
    )
    (net (code "276") (name "Net-(LED134-SDI)") (class "Default")
      (node (ref "LED134") (pin "3") (pinfunction "SDI_3") (pintype "unspecified"))
      (node (ref "LED135") (pin "1") (pinfunction "SDO_1") (pintype "unspecified"))
    )
    (net (code "277") (name "Net-(LED135-CKL)") (class "Default")
      (node (ref "LED135") (pin "4") (pinfunction "CKL_4") (pintype "unspecified"))
      (node (ref "LED136") (pin "6") (pinfunction "CKO_6") (pintype "unspecified"))
    )
    (net (code "278") (name "Net-(LED135-SDI)") (class "Default")
      (node (ref "LED135") (pin "3") (pinfunction "SDI_3") (pintype "unspecified"))
      (node (ref "LED136") (pin "1") (pinfunction "SDO_1") (pintype "unspecified"))
    )
    (net (code "279") (name "Net-(LED136-CKL)") (class "Default")
      (node (ref "LED136") (pin "4") (pinfunction "CKL_4") (pintype "unspecified"))
      (node (ref "LED137") (pin "6") (pinfunction "CKO_6") (pintype "unspecified"))
    )
    (net (code "280") (name "Net-(LED136-SDI)") (class "Default")
      (node (ref "LED136") (pin "3") (pinfunction "SDI_3") (pintype "unspecified"))
      (node (ref "LED137") (pin "1") (pinfunction "SDO_1") (pintype "unspecified"))
    )
    (net (code "281") (name "Net-(LED137-CKL)") (class "Default")
      (node (ref "LED137") (pin "4") (pinfunction "CKL_4") (pintype "unspecified"))
      (node (ref "LED138") (pin "6") (pinfunction "CKO_6") (pintype "unspecified"))
    )
    (net (code "282") (name "Net-(LED137-SDI)") (class "Default")
      (node (ref "LED137") (pin "3") (pinfunction "SDI_3") (pintype "unspecified"))
      (node (ref "LED138") (pin "1") (pinfunction "SDO_1") (pintype "unspecified"))
    )
    (net (code "283") (name "Net-(LED138-CKL)") (class "Default")
      (node (ref "LED138") (pin "4") (pinfunction "CKL_4") (pintype "unspecified"))
      (node (ref "LED139") (pin "6") (pinfunction "CKO_6") (pintype "unspecified"))
    )
    (net (code "284") (name "Net-(LED138-SDI)") (class "Default")
      (node (ref "LED138") (pin "3") (pinfunction "SDI_3") (pintype "unspecified"))
      (node (ref "LED139") (pin "1") (pinfunction "SDO_1") (pintype "unspecified"))
    )
    (net (code "285") (name "Net-(LED139-CKL)") (class "Default")
      (node (ref "LED139") (pin "4") (pinfunction "CKL_4") (pintype "unspecified"))
      (node (ref "LED140") (pin "6") (pinfunction "CKO_6") (pintype "unspecified"))
    )
    (net (code "286") (name "Net-(LED139-SDI)") (class "Default")
      (node (ref "LED139") (pin "3") (pinfunction "SDI_3") (pintype "unspecified"))
      (node (ref "LED140") (pin "1") (pinfunction "SDO_1") (pintype "unspecified"))
    )
    (net (code "287") (name "Net-(LED140-CKL)") (class "Default")
      (node (ref "LED140") (pin "4") (pinfunction "CKL_4") (pintype "unspecified"))
      (node (ref "LED141") (pin "6") (pinfunction "CKO_6") (pintype "unspecified"))
    )
    (net (code "288") (name "Net-(LED140-SDI)") (class "Default")
      (node (ref "LED140") (pin "3") (pinfunction "SDI_3") (pintype "unspecified"))
      (node (ref "LED141") (pin "1") (pinfunction "SDO_1") (pintype "unspecified"))
    )
    (net (code "289") (name "Net-(LED141-CKL)") (class "Default")
      (node (ref "LED141") (pin "4") (pinfunction "CKL_4") (pintype "unspecified"))
      (node (ref "LED142") (pin "6") (pinfunction "CKO_6") (pintype "unspecified"))
    )
    (net (code "290") (name "Net-(LED141-SDI)") (class "Default")
      (node (ref "LED141") (pin "3") (pinfunction "SDI_3") (pintype "unspecified"))
      (node (ref "LED142") (pin "1") (pinfunction "SDO_1") (pintype "unspecified"))
    )
    (net (code "291") (name "Net-(LED142-CKL)") (class "Default")
      (node (ref "LED142") (pin "4") (pinfunction "CKL_4") (pintype "unspecified"))
      (node (ref "LED143") (pin "6") (pinfunction "CKO_6") (pintype "unspecified"))
    )
    (net (code "292") (name "Net-(LED142-SDI)") (class "Default")
      (node (ref "LED142") (pin "3") (pinfunction "SDI_3") (pintype "unspecified"))
      (node (ref "LED143") (pin "1") (pinfunction "SDO_1") (pintype "unspecified"))
    )
    (net (code "293") (name "Net-(LED143-CKL)") (class "Default")
      (node (ref "LED143") (pin "4") (pinfunction "CKL_4") (pintype "unspecified"))
      (node (ref "LED144") (pin "6") (pinfunction "CKO_6") (pintype "unspecified"))
    )
    (net (code "294") (name "Net-(LED143-SDI)") (class "Default")
      (node (ref "LED143") (pin "3") (pinfunction "SDI_3") (pintype "unspecified"))
      (node (ref "LED144") (pin "1") (pinfunction "SDO_1") (pintype "unspecified"))
    )
    (net (code "295") (name "Net-(LED145-CKO)") (class "Default")
      (node (ref "LED145") (pin "6") (pinfunction "CKO_6") (pintype "unspecified"))
      (node (ref "LED146") (pin "4") (pinfunction "CKL_4") (pintype "unspecified"))
    )
    (net (code "296") (name "Net-(LED145-SDO)") (class "Default")
      (node (ref "LED145") (pin "1") (pinfunction "SDO_1") (pintype "unspecified"))
      (node (ref "LED146") (pin "3") (pinfunction "SDI_3") (pintype "unspecified"))
    )
    (net (code "297") (name "Net-(LED146-CKO)") (class "Default")
      (node (ref "LED146") (pin "6") (pinfunction "CKO_6") (pintype "unspecified"))
      (node (ref "LED147") (pin "4") (pinfunction "CKL_4") (pintype "unspecified"))
    )
    (net (code "298") (name "Net-(LED146-SDO)") (class "Default")
      (node (ref "LED146") (pin "1") (pinfunction "SDO_1") (pintype "unspecified"))
      (node (ref "LED147") (pin "3") (pinfunction "SDI_3") (pintype "unspecified"))
    )
    (net (code "299") (name "Net-(LED147-CKO)") (class "Default")
      (node (ref "LED147") (pin "6") (pinfunction "CKO_6") (pintype "unspecified"))
      (node (ref "LED148") (pin "4") (pinfunction "CKL_4") (pintype "unspecified"))
    )
    (net (code "300") (name "Net-(LED147-SDO)") (class "Default")
      (node (ref "LED147") (pin "1") (pinfunction "SDO_1") (pintype "unspecified"))
      (node (ref "LED148") (pin "3") (pinfunction "SDI_3") (pintype "unspecified"))
    )
    (net (code "301") (name "Net-(LED148-CKO)") (class "Default")
      (node (ref "LED148") (pin "6") (pinfunction "CKO_6") (pintype "unspecified"))
      (node (ref "LED149") (pin "4") (pinfunction "CKL_4") (pintype "unspecified"))
    )
    (net (code "302") (name "Net-(LED148-SDO)") (class "Default")
      (node (ref "LED148") (pin "1") (pinfunction "SDO_1") (pintype "unspecified"))
      (node (ref "LED149") (pin "3") (pinfunction "SDI_3") (pintype "unspecified"))
    )
    (net (code "303") (name "Net-(LED149-CKO)") (class "Default")
      (node (ref "LED149") (pin "6") (pinfunction "CKO_6") (pintype "unspecified"))
      (node (ref "LED150") (pin "4") (pinfunction "CKL_4") (pintype "unspecified"))
    )
    (net (code "304") (name "Net-(LED149-SDO)") (class "Default")
      (node (ref "LED149") (pin "1") (pinfunction "SDO_1") (pintype "unspecified"))
      (node (ref "LED150") (pin "3") (pinfunction "SDI_3") (pintype "unspecified"))
    )
    (net (code "305") (name "Net-(LED150-CKO)") (class "Default")
      (node (ref "LED150") (pin "6") (pinfunction "CKO_6") (pintype "unspecified"))
      (node (ref "LED151") (pin "4") (pinfunction "CKL_4") (pintype "unspecified"))
    )
    (net (code "306") (name "Net-(LED150-SDO)") (class "Default")
      (node (ref "LED150") (pin "1") (pinfunction "SDO_1") (pintype "unspecified"))
      (node (ref "LED151") (pin "3") (pinfunction "SDI_3") (pintype "unspecified"))
    )
    (net (code "307") (name "Net-(LED151-CKO)") (class "Default")
      (node (ref "LED151") (pin "6") (pinfunction "CKO_6") (pintype "unspecified"))
      (node (ref "LED152") (pin "4") (pinfunction "CKL_4") (pintype "unspecified"))
    )
    (net (code "308") (name "Net-(LED151-SDO)") (class "Default")
      (node (ref "LED151") (pin "1") (pinfunction "SDO_1") (pintype "unspecified"))
      (node (ref "LED152") (pin "3") (pinfunction "SDI_3") (pintype "unspecified"))
    )
    (net (code "309") (name "Net-(LED152-CKO)") (class "Default")
      (node (ref "LED152") (pin "6") (pinfunction "CKO_6") (pintype "unspecified"))
      (node (ref "LED153") (pin "4") (pinfunction "CKL_4") (pintype "unspecified"))
    )
    (net (code "310") (name "Net-(LED152-SDO)") (class "Default")
      (node (ref "LED152") (pin "1") (pinfunction "SDO_1") (pintype "unspecified"))
      (node (ref "LED153") (pin "3") (pinfunction "SDI_3") (pintype "unspecified"))
    )
    (net (code "311") (name "Net-(LED153-CKO)") (class "Default")
      (node (ref "LED153") (pin "6") (pinfunction "CKO_6") (pintype "unspecified"))
      (node (ref "LED154") (pin "4") (pinfunction "CKL_4") (pintype "unspecified"))
    )
    (net (code "312") (name "Net-(LED153-SDO)") (class "Default")
      (node (ref "LED153") (pin "1") (pinfunction "SDO_1") (pintype "unspecified"))
      (node (ref "LED154") (pin "3") (pinfunction "SDI_3") (pintype "unspecified"))
    )
    (net (code "313") (name "Net-(LED154-CKO)") (class "Default")
      (node (ref "LED154") (pin "6") (pinfunction "CKO_6") (pintype "unspecified"))
      (node (ref "LED155") (pin "4") (pinfunction "CKL_4") (pintype "unspecified"))
    )
    (net (code "314") (name "Net-(LED154-SDO)") (class "Default")
      (node (ref "LED154") (pin "1") (pinfunction "SDO_1") (pintype "unspecified"))
      (node (ref "LED155") (pin "3") (pinfunction "SDI_3") (pintype "unspecified"))
    )
    (net (code "315") (name "Net-(LED155-CKO)") (class "Default")
      (node (ref "LED155") (pin "6") (pinfunction "CKO_6") (pintype "unspecified"))
      (node (ref "LED156") (pin "4") (pinfunction "CKL_4") (pintype "unspecified"))
    )
    (net (code "316") (name "Net-(LED155-SDO)") (class "Default")
      (node (ref "LED155") (pin "1") (pinfunction "SDO_1") (pintype "unspecified"))
      (node (ref "LED156") (pin "3") (pinfunction "SDI_3") (pintype "unspecified"))
    )
    (net (code "317") (name "Net-(LED156-CKO)") (class "Default")
      (node (ref "LED156") (pin "6") (pinfunction "CKO_6") (pintype "unspecified"))
      (node (ref "LED168") (pin "4") (pinfunction "CKL_4") (pintype "unspecified"))
    )
    (net (code "318") (name "Net-(LED156-SDO)") (class "Default")
      (node (ref "LED156") (pin "1") (pinfunction "SDO_1") (pintype "unspecified"))
      (node (ref "LED168") (pin "3") (pinfunction "SDI_3") (pintype "unspecified"))
    )
    (net (code "319") (name "Net-(LED157-CKL)") (class "Default")
      (node (ref "LED157") (pin "4") (pinfunction "CKL_4") (pintype "unspecified"))
      (node (ref "LED158") (pin "6") (pinfunction "CKO_6") (pintype "unspecified"))
    )
    (net (code "320") (name "Net-(LED157-CKO)") (class "Default")
      (node (ref "LED157") (pin "6") (pinfunction "CKO_6") (pintype "unspecified"))
      (node (ref "LED169") (pin "4") (pinfunction "CKL_4") (pintype "unspecified"))
    )
    (net (code "321") (name "Net-(LED157-SDI)") (class "Default")
      (node (ref "LED157") (pin "3") (pinfunction "SDI_3") (pintype "unspecified"))
      (node (ref "LED158") (pin "1") (pinfunction "SDO_1") (pintype "unspecified"))
    )
    (net (code "322") (name "Net-(LED157-SDO)") (class "Default")
      (node (ref "LED157") (pin "1") (pinfunction "SDO_1") (pintype "unspecified"))
      (node (ref "LED169") (pin "3") (pinfunction "SDI_3") (pintype "unspecified"))
    )
    (net (code "323") (name "Net-(LED158-CKL)") (class "Default")
      (node (ref "LED158") (pin "4") (pinfunction "CKL_4") (pintype "unspecified"))
      (node (ref "LED159") (pin "6") (pinfunction "CKO_6") (pintype "unspecified"))
    )
    (net (code "324") (name "Net-(LED158-SDI)") (class "Default")
      (node (ref "LED158") (pin "3") (pinfunction "SDI_3") (pintype "unspecified"))
      (node (ref "LED159") (pin "1") (pinfunction "SDO_1") (pintype "unspecified"))
    )
    (net (code "325") (name "Net-(LED159-CKL)") (class "Default")
      (node (ref "LED159") (pin "4") (pinfunction "CKL_4") (pintype "unspecified"))
      (node (ref "LED160") (pin "6") (pinfunction "CKO_6") (pintype "unspecified"))
    )
    (net (code "326") (name "Net-(LED159-SDI)") (class "Default")
      (node (ref "LED159") (pin "3") (pinfunction "SDI_3") (pintype "unspecified"))
      (node (ref "LED160") (pin "1") (pinfunction "SDO_1") (pintype "unspecified"))
    )
    (net (code "327") (name "Net-(LED160-CKL)") (class "Default")
      (node (ref "LED160") (pin "4") (pinfunction "CKL_4") (pintype "unspecified"))
      (node (ref "LED161") (pin "6") (pinfunction "CKO_6") (pintype "unspecified"))
    )
    (net (code "328") (name "Net-(LED160-SDI)") (class "Default")
      (node (ref "LED160") (pin "3") (pinfunction "SDI_3") (pintype "unspecified"))
      (node (ref "LED161") (pin "1") (pinfunction "SDO_1") (pintype "unspecified"))
    )
    (net (code "329") (name "Net-(LED161-CKL)") (class "Default")
      (node (ref "LED161") (pin "4") (pinfunction "CKL_4") (pintype "unspecified"))
      (node (ref "LED162") (pin "6") (pinfunction "CKO_6") (pintype "unspecified"))
    )
    (net (code "330") (name "Net-(LED161-SDI)") (class "Default")
      (node (ref "LED161") (pin "3") (pinfunction "SDI_3") (pintype "unspecified"))
      (node (ref "LED162") (pin "1") (pinfunction "SDO_1") (pintype "unspecified"))
    )
    (net (code "331") (name "Net-(LED162-CKL)") (class "Default")
      (node (ref "LED162") (pin "4") (pinfunction "CKL_4") (pintype "unspecified"))
      (node (ref "LED163") (pin "6") (pinfunction "CKO_6") (pintype "unspecified"))
    )
    (net (code "332") (name "Net-(LED162-SDI)") (class "Default")
      (node (ref "LED162") (pin "3") (pinfunction "SDI_3") (pintype "unspecified"))
      (node (ref "LED163") (pin "1") (pinfunction "SDO_1") (pintype "unspecified"))
    )
    (net (code "333") (name "Net-(LED163-CKL)") (class "Default")
      (node (ref "LED163") (pin "4") (pinfunction "CKL_4") (pintype "unspecified"))
      (node (ref "LED164") (pin "6") (pinfunction "CKO_6") (pintype "unspecified"))
    )
    (net (code "334") (name "Net-(LED163-SDI)") (class "Default")
      (node (ref "LED163") (pin "3") (pinfunction "SDI_3") (pintype "unspecified"))
      (node (ref "LED164") (pin "1") (pinfunction "SDO_1") (pintype "unspecified"))
    )
    (net (code "335") (name "Net-(LED164-CKL)") (class "Default")
      (node (ref "LED164") (pin "4") (pinfunction "CKL_4") (pintype "unspecified"))
      (node (ref "LED165") (pin "6") (pinfunction "CKO_6") (pintype "unspecified"))
    )
    (net (code "336") (name "Net-(LED164-SDI)") (class "Default")
      (node (ref "LED164") (pin "3") (pinfunction "SDI_3") (pintype "unspecified"))
      (node (ref "LED165") (pin "1") (pinfunction "SDO_1") (pintype "unspecified"))
    )
    (net (code "337") (name "Net-(LED165-CKL)") (class "Default")
      (node (ref "LED165") (pin "4") (pinfunction "CKL_4") (pintype "unspecified"))
      (node (ref "LED166") (pin "6") (pinfunction "CKO_6") (pintype "unspecified"))
    )
    (net (code "338") (name "Net-(LED165-SDI)") (class "Default")
      (node (ref "LED165") (pin "3") (pinfunction "SDI_3") (pintype "unspecified"))
      (node (ref "LED166") (pin "1") (pinfunction "SDO_1") (pintype "unspecified"))
    )
    (net (code "339") (name "Net-(LED166-CKL)") (class "Default")
      (node (ref "LED166") (pin "4") (pinfunction "CKL_4") (pintype "unspecified"))
      (node (ref "LED167") (pin "6") (pinfunction "CKO_6") (pintype "unspecified"))
    )
    (net (code "340") (name "Net-(LED166-SDI)") (class "Default")
      (node (ref "LED166") (pin "3") (pinfunction "SDI_3") (pintype "unspecified"))
      (node (ref "LED167") (pin "1") (pinfunction "SDO_1") (pintype "unspecified"))
    )
    (net (code "341") (name "Net-(LED167-CKL)") (class "Default")
      (node (ref "LED167") (pin "4") (pinfunction "CKL_4") (pintype "unspecified"))
      (node (ref "LED168") (pin "6") (pinfunction "CKO_6") (pintype "unspecified"))
    )
    (net (code "342") (name "Net-(LED167-SDI)") (class "Default")
      (node (ref "LED167") (pin "3") (pinfunction "SDI_3") (pintype "unspecified"))
      (node (ref "LED168") (pin "1") (pinfunction "SDO_1") (pintype "unspecified"))
    )
    (net (code "343") (name "Net-(LED169-CKO)") (class "Default")
      (node (ref "LED169") (pin "6") (pinfunction "CKO_6") (pintype "unspecified"))
      (node (ref "LED170") (pin "4") (pinfunction "CKL_4") (pintype "unspecified"))
    )
    (net (code "344") (name "Net-(LED169-SDO)") (class "Default")
      (node (ref "LED169") (pin "1") (pinfunction "SDO_1") (pintype "unspecified"))
      (node (ref "LED170") (pin "3") (pinfunction "SDI_3") (pintype "unspecified"))
    )
    (net (code "345") (name "Net-(LED170-CKO)") (class "Default")
      (node (ref "LED170") (pin "6") (pinfunction "CKO_6") (pintype "unspecified"))
      (node (ref "LED171") (pin "4") (pinfunction "CKL_4") (pintype "unspecified"))
    )
    (net (code "346") (name "Net-(LED170-SDO)") (class "Default")
      (node (ref "LED170") (pin "1") (pinfunction "SDO_1") (pintype "unspecified"))
      (node (ref "LED171") (pin "3") (pinfunction "SDI_3") (pintype "unspecified"))
    )
    (net (code "347") (name "Net-(LED171-CKO)") (class "Default")
      (node (ref "LED171") (pin "6") (pinfunction "CKO_6") (pintype "unspecified"))
      (node (ref "LED172") (pin "4") (pinfunction "CKL_4") (pintype "unspecified"))
    )
    (net (code "348") (name "Net-(LED171-SDO)") (class "Default")
      (node (ref "LED171") (pin "1") (pinfunction "SDO_1") (pintype "unspecified"))
      (node (ref "LED172") (pin "3") (pinfunction "SDI_3") (pintype "unspecified"))
    )
    (net (code "349") (name "Net-(LED172-CKO)") (class "Default")
      (node (ref "LED172") (pin "6") (pinfunction "CKO_6") (pintype "unspecified"))
      (node (ref "LED173") (pin "4") (pinfunction "CKL_4") (pintype "unspecified"))
    )
    (net (code "350") (name "Net-(LED172-SDO)") (class "Default")
      (node (ref "LED172") (pin "1") (pinfunction "SDO_1") (pintype "unspecified"))
      (node (ref "LED173") (pin "3") (pinfunction "SDI_3") (pintype "unspecified"))
    )
    (net (code "351") (name "Net-(LED173-CKO)") (class "Default")
      (node (ref "LED173") (pin "6") (pinfunction "CKO_6") (pintype "unspecified"))
      (node (ref "LED174") (pin "4") (pinfunction "CKL_4") (pintype "unspecified"))
    )
    (net (code "352") (name "Net-(LED173-SDO)") (class "Default")
      (node (ref "LED173") (pin "1") (pinfunction "SDO_1") (pintype "unspecified"))
      (node (ref "LED174") (pin "3") (pinfunction "SDI_3") (pintype "unspecified"))
    )
    (net (code "353") (name "Net-(LED174-CKO)") (class "Default")
      (node (ref "LED174") (pin "6") (pinfunction "CKO_6") (pintype "unspecified"))
      (node (ref "LED175") (pin "4") (pinfunction "CKL_4") (pintype "unspecified"))
    )
    (net (code "354") (name "Net-(LED174-SDO)") (class "Default")
      (node (ref "LED174") (pin "1") (pinfunction "SDO_1") (pintype "unspecified"))
      (node (ref "LED175") (pin "3") (pinfunction "SDI_3") (pintype "unspecified"))
    )
    (net (code "355") (name "Net-(LED175-CKO)") (class "Default")
      (node (ref "LED175") (pin "6") (pinfunction "CKO_6") (pintype "unspecified"))
      (node (ref "LED176") (pin "4") (pinfunction "CKL_4") (pintype "unspecified"))
    )
    (net (code "356") (name "Net-(LED175-SDO)") (class "Default")
      (node (ref "LED175") (pin "1") (pinfunction "SDO_1") (pintype "unspecified"))
      (node (ref "LED176") (pin "3") (pinfunction "SDI_3") (pintype "unspecified"))
    )
    (net (code "357") (name "Net-(LED176-CKO)") (class "Default")
      (node (ref "LED176") (pin "6") (pinfunction "CKO_6") (pintype "unspecified"))
      (node (ref "LED177") (pin "4") (pinfunction "CKL_4") (pintype "unspecified"))
    )
    (net (code "358") (name "Net-(LED176-SDO)") (class "Default")
      (node (ref "LED176") (pin "1") (pinfunction "SDO_1") (pintype "unspecified"))
      (node (ref "LED177") (pin "3") (pinfunction "SDI_3") (pintype "unspecified"))
    )
    (net (code "359") (name "Net-(LED177-CKO)") (class "Default")
      (node (ref "LED177") (pin "6") (pinfunction "CKO_6") (pintype "unspecified"))
      (node (ref "LED178") (pin "4") (pinfunction "CKL_4") (pintype "unspecified"))
    )
    (net (code "360") (name "Net-(LED177-SDO)") (class "Default")
      (node (ref "LED177") (pin "1") (pinfunction "SDO_1") (pintype "unspecified"))
      (node (ref "LED178") (pin "3") (pinfunction "SDI_3") (pintype "unspecified"))
    )
    (net (code "361") (name "Net-(LED178-CKO)") (class "Default")
      (node (ref "LED178") (pin "6") (pinfunction "CKO_6") (pintype "unspecified"))
      (node (ref "LED179") (pin "4") (pinfunction "CKL_4") (pintype "unspecified"))
    )
    (net (code "362") (name "Net-(LED178-SDO)") (class "Default")
      (node (ref "LED178") (pin "1") (pinfunction "SDO_1") (pintype "unspecified"))
      (node (ref "LED179") (pin "3") (pinfunction "SDI_3") (pintype "unspecified"))
    )
    (net (code "363") (name "Net-(LED179-CKO)") (class "Default")
      (node (ref "LED179") (pin "6") (pinfunction "CKO_6") (pintype "unspecified"))
      (node (ref "LED180") (pin "4") (pinfunction "CKL_4") (pintype "unspecified"))
    )
    (net (code "364") (name "Net-(LED179-SDO)") (class "Default")
      (node (ref "LED179") (pin "1") (pinfunction "SDO_1") (pintype "unspecified"))
      (node (ref "LED180") (pin "3") (pinfunction "SDI_3") (pintype "unspecified"))
    )
    (net (code "365") (name "Net-(LED180-CKO)") (class "Default")
      (node (ref "LED180") (pin "6") (pinfunction "CKO_6") (pintype "unspecified"))
      (node (ref "LED192") (pin "4") (pinfunction "CKL_4") (pintype "unspecified"))
    )
    (net (code "366") (name "Net-(LED180-SDO)") (class "Default")
      (node (ref "LED180") (pin "1") (pinfunction "SDO_1") (pintype "unspecified"))
      (node (ref "LED192") (pin "3") (pinfunction "SDI_3") (pintype "unspecified"))
    )
    (net (code "367") (name "Net-(LED181-CKL)") (class "Default")
      (node (ref "LED181") (pin "4") (pinfunction "CKL_4") (pintype "unspecified"))
      (node (ref "LED182") (pin "6") (pinfunction "CKO_6") (pintype "unspecified"))
    )
    (net (code "368") (name "Net-(LED181-CKO)") (class "Default")
      (node (ref "LED181") (pin "6") (pinfunction "CKO_6") (pintype "unspecified"))
      (node (ref "LED193") (pin "4") (pinfunction "CKL_4") (pintype "unspecified"))
    )
    (net (code "369") (name "Net-(LED181-SDI)") (class "Default")
      (node (ref "LED181") (pin "3") (pinfunction "SDI_3") (pintype "unspecified"))
      (node (ref "LED182") (pin "1") (pinfunction "SDO_1") (pintype "unspecified"))
    )
    (net (code "370") (name "Net-(LED181-SDO)") (class "Default")
      (node (ref "LED181") (pin "1") (pinfunction "SDO_1") (pintype "unspecified"))
      (node (ref "LED193") (pin "3") (pinfunction "SDI_3") (pintype "unspecified"))
    )
    (net (code "371") (name "Net-(LED182-CKL)") (class "Default")
      (node (ref "LED182") (pin "4") (pinfunction "CKL_4") (pintype "unspecified"))
      (node (ref "LED183") (pin "6") (pinfunction "CKO_6") (pintype "unspecified"))
    )
    (net (code "372") (name "Net-(LED182-SDI)") (class "Default")
      (node (ref "LED182") (pin "3") (pinfunction "SDI_3") (pintype "unspecified"))
      (node (ref "LED183") (pin "1") (pinfunction "SDO_1") (pintype "unspecified"))
    )
    (net (code "373") (name "Net-(LED183-CKL)") (class "Default")
      (node (ref "LED183") (pin "4") (pinfunction "CKL_4") (pintype "unspecified"))
      (node (ref "LED184") (pin "6") (pinfunction "CKO_6") (pintype "unspecified"))
    )
    (net (code "374") (name "Net-(LED183-SDI)") (class "Default")
      (node (ref "LED183") (pin "3") (pinfunction "SDI_3") (pintype "unspecified"))
      (node (ref "LED184") (pin "1") (pinfunction "SDO_1") (pintype "unspecified"))
    )
    (net (code "375") (name "Net-(LED184-CKL)") (class "Default")
      (node (ref "LED184") (pin "4") (pinfunction "CKL_4") (pintype "unspecified"))
      (node (ref "LED185") (pin "6") (pinfunction "CKO_6") (pintype "unspecified"))
    )
    (net (code "376") (name "Net-(LED184-SDI)") (class "Default")
      (node (ref "LED184") (pin "3") (pinfunction "SDI_3") (pintype "unspecified"))
      (node (ref "LED185") (pin "1") (pinfunction "SDO_1") (pintype "unspecified"))
    )
    (net (code "377") (name "Net-(LED185-CKL)") (class "Default")
      (node (ref "LED185") (pin "4") (pinfunction "CKL_4") (pintype "unspecified"))
      (node (ref "LED186") (pin "6") (pinfunction "CKO_6") (pintype "unspecified"))
    )
    (net (code "378") (name "Net-(LED185-SDI)") (class "Default")
      (node (ref "LED185") (pin "3") (pinfunction "SDI_3") (pintype "unspecified"))
      (node (ref "LED186") (pin "1") (pinfunction "SDO_1") (pintype "unspecified"))
    )
    (net (code "379") (name "Net-(LED186-CKL)") (class "Default")
      (node (ref "LED186") (pin "4") (pinfunction "CKL_4") (pintype "unspecified"))
      (node (ref "LED187") (pin "6") (pinfunction "CKO_6") (pintype "unspecified"))
    )
    (net (code "380") (name "Net-(LED186-SDI)") (class "Default")
      (node (ref "LED186") (pin "3") (pinfunction "SDI_3") (pintype "unspecified"))
      (node (ref "LED187") (pin "1") (pinfunction "SDO_1") (pintype "unspecified"))
    )
    (net (code "381") (name "Net-(LED187-CKL)") (class "Default")
      (node (ref "LED187") (pin "4") (pinfunction "CKL_4") (pintype "unspecified"))
      (node (ref "LED188") (pin "6") (pinfunction "CKO_6") (pintype "unspecified"))
    )
    (net (code "382") (name "Net-(LED187-SDI)") (class "Default")
      (node (ref "LED187") (pin "3") (pinfunction "SDI_3") (pintype "unspecified"))
      (node (ref "LED188") (pin "1") (pinfunction "SDO_1") (pintype "unspecified"))
    )
    (net (code "383") (name "Net-(LED188-CKL)") (class "Default")
      (node (ref "LED188") (pin "4") (pinfunction "CKL_4") (pintype "unspecified"))
      (node (ref "LED189") (pin "6") (pinfunction "CKO_6") (pintype "unspecified"))
    )
    (net (code "384") (name "Net-(LED188-SDI)") (class "Default")
      (node (ref "LED188") (pin "3") (pinfunction "SDI_3") (pintype "unspecified"))
      (node (ref "LED189") (pin "1") (pinfunction "SDO_1") (pintype "unspecified"))
    )
    (net (code "385") (name "Net-(LED189-CKL)") (class "Default")
      (node (ref "LED189") (pin "4") (pinfunction "CKL_4") (pintype "unspecified"))
      (node (ref "LED190") (pin "6") (pinfunction "CKO_6") (pintype "unspecified"))
    )
    (net (code "386") (name "Net-(LED189-SDI)") (class "Default")
      (node (ref "LED189") (pin "3") (pinfunction "SDI_3") (pintype "unspecified"))
      (node (ref "LED190") (pin "1") (pinfunction "SDO_1") (pintype "unspecified"))
    )
    (net (code "387") (name "Net-(LED190-CKL)") (class "Default")
      (node (ref "LED190") (pin "4") (pinfunction "CKL_4") (pintype "unspecified"))
      (node (ref "LED191") (pin "6") (pinfunction "CKO_6") (pintype "unspecified"))
    )
    (net (code "388") (name "Net-(LED190-SDI)") (class "Default")
      (node (ref "LED190") (pin "3") (pinfunction "SDI_3") (pintype "unspecified"))
      (node (ref "LED191") (pin "1") (pinfunction "SDO_1") (pintype "unspecified"))
    )
    (net (code "389") (name "Net-(LED191-CKL)") (class "Default")
      (node (ref "LED191") (pin "4") (pinfunction "CKL_4") (pintype "unspecified"))
      (node (ref "LED192") (pin "6") (pinfunction "CKO_6") (pintype "unspecified"))
    )
    (net (code "390") (name "Net-(LED191-SDI)") (class "Default")
      (node (ref "LED191") (pin "3") (pinfunction "SDI_3") (pintype "unspecified"))
      (node (ref "LED192") (pin "1") (pinfunction "SDO_1") (pintype "unspecified"))
    )
    (net (code "391") (name "Net-(LED193-CKO)") (class "Default")
      (node (ref "LED193") (pin "6") (pinfunction "CKO_6") (pintype "unspecified"))
      (node (ref "LED194") (pin "4") (pinfunction "CKL_4") (pintype "unspecified"))
    )
    (net (code "392") (name "Net-(LED193-SDO)") (class "Default")
      (node (ref "LED193") (pin "1") (pinfunction "SDO_1") (pintype "unspecified"))
      (node (ref "LED194") (pin "3") (pinfunction "SDI_3") (pintype "unspecified"))
    )
    (net (code "393") (name "Net-(LED194-CKO)") (class "Default")
      (node (ref "LED194") (pin "6") (pinfunction "CKO_6") (pintype "unspecified"))
      (node (ref "LED195") (pin "4") (pinfunction "CKL_4") (pintype "unspecified"))
    )
    (net (code "394") (name "Net-(LED194-SDO)") (class "Default")
      (node (ref "LED194") (pin "1") (pinfunction "SDO_1") (pintype "unspecified"))
      (node (ref "LED195") (pin "3") (pinfunction "SDI_3") (pintype "unspecified"))
    )
    (net (code "395") (name "Net-(LED195-CKO)") (class "Default")
      (node (ref "LED195") (pin "6") (pinfunction "CKO_6") (pintype "unspecified"))
      (node (ref "LED196") (pin "4") (pinfunction "CKL_4") (pintype "unspecified"))
    )
    (net (code "396") (name "Net-(LED195-SDO)") (class "Default")
      (node (ref "LED195") (pin "1") (pinfunction "SDO_1") (pintype "unspecified"))
      (node (ref "LED196") (pin "3") (pinfunction "SDI_3") (pintype "unspecified"))
    )
    (net (code "397") (name "Net-(LED196-CKO)") (class "Default")
      (node (ref "LED196") (pin "6") (pinfunction "CKO_6") (pintype "unspecified"))
      (node (ref "LED197") (pin "4") (pinfunction "CKL_4") (pintype "unspecified"))
    )
    (net (code "398") (name "Net-(LED196-SDO)") (class "Default")
      (node (ref "LED196") (pin "1") (pinfunction "SDO_1") (pintype "unspecified"))
      (node (ref "LED197") (pin "3") (pinfunction "SDI_3") (pintype "unspecified"))
    )
    (net (code "399") (name "Net-(LED197-CKO)") (class "Default")
      (node (ref "LED197") (pin "6") (pinfunction "CKO_6") (pintype "unspecified"))
      (node (ref "LED198") (pin "4") (pinfunction "CKL_4") (pintype "unspecified"))
    )
    (net (code "400") (name "Net-(LED197-SDO)") (class "Default")
      (node (ref "LED197") (pin "1") (pinfunction "SDO_1") (pintype "unspecified"))
      (node (ref "LED198") (pin "3") (pinfunction "SDI_3") (pintype "unspecified"))
    )
    (net (code "401") (name "Net-(LED198-CKO)") (class "Default")
      (node (ref "LED198") (pin "6") (pinfunction "CKO_6") (pintype "unspecified"))
      (node (ref "LED199") (pin "4") (pinfunction "CKL_4") (pintype "unspecified"))
    )
    (net (code "402") (name "Net-(LED198-SDO)") (class "Default")
      (node (ref "LED198") (pin "1") (pinfunction "SDO_1") (pintype "unspecified"))
      (node (ref "LED199") (pin "3") (pinfunction "SDI_3") (pintype "unspecified"))
    )
    (net (code "403") (name "Net-(LED199-CKO)") (class "Default")
      (node (ref "LED199") (pin "6") (pinfunction "CKO_6") (pintype "unspecified"))
      (node (ref "LED200") (pin "4") (pinfunction "CKL_4") (pintype "unspecified"))
    )
    (net (code "404") (name "Net-(LED199-SDO)") (class "Default")
      (node (ref "LED199") (pin "1") (pinfunction "SDO_1") (pintype "unspecified"))
      (node (ref "LED200") (pin "3") (pinfunction "SDI_3") (pintype "unspecified"))
    )
    (net (code "405") (name "Net-(LED200-CKO)") (class "Default")
      (node (ref "LED200") (pin "6") (pinfunction "CKO_6") (pintype "unspecified"))
      (node (ref "LED201") (pin "4") (pinfunction "CKL_4") (pintype "unspecified"))
    )
    (net (code "406") (name "Net-(LED200-SDO)") (class "Default")
      (node (ref "LED200") (pin "1") (pinfunction "SDO_1") (pintype "unspecified"))
      (node (ref "LED201") (pin "3") (pinfunction "SDI_3") (pintype "unspecified"))
    )
    (net (code "407") (name "Net-(LED201-CKO)") (class "Default")
      (node (ref "LED201") (pin "6") (pinfunction "CKO_6") (pintype "unspecified"))
      (node (ref "LED202") (pin "4") (pinfunction "CKL_4") (pintype "unspecified"))
    )
    (net (code "408") (name "Net-(LED201-SDO)") (class "Default")
      (node (ref "LED201") (pin "1") (pinfunction "SDO_1") (pintype "unspecified"))
      (node (ref "LED202") (pin "3") (pinfunction "SDI_3") (pintype "unspecified"))
    )
    (net (code "409") (name "Net-(LED202-CKO)") (class "Default")
      (node (ref "LED202") (pin "6") (pinfunction "CKO_6") (pintype "unspecified"))
      (node (ref "LED203") (pin "4") (pinfunction "CKL_4") (pintype "unspecified"))
    )
    (net (code "410") (name "Net-(LED202-SDO)") (class "Default")
      (node (ref "LED202") (pin "1") (pinfunction "SDO_1") (pintype "unspecified"))
      (node (ref "LED203") (pin "3") (pinfunction "SDI_3") (pintype "unspecified"))
    )
    (net (code "411") (name "Net-(LED203-CKO)") (class "Default")
      (node (ref "LED203") (pin "6") (pinfunction "CKO_6") (pintype "unspecified"))
      (node (ref "LED204") (pin "4") (pinfunction "CKL_4") (pintype "unspecified"))
    )
    (net (code "412") (name "Net-(LED203-SDO)") (class "Default")
      (node (ref "LED203") (pin "1") (pinfunction "SDO_1") (pintype "unspecified"))
      (node (ref "LED204") (pin "3") (pinfunction "SDI_3") (pintype "unspecified"))
    )
    (net (code "413") (name "Net-(LED204-CKO)") (class "Default")
      (node (ref "LED204") (pin "6") (pinfunction "CKO_6") (pintype "unspecified"))
      (node (ref "LED216") (pin "4") (pinfunction "CKL_4") (pintype "unspecified"))
    )
    (net (code "414") (name "Net-(LED204-SDO)") (class "Default")
      (node (ref "LED204") (pin "1") (pinfunction "SDO_1") (pintype "unspecified"))
      (node (ref "LED216") (pin "3") (pinfunction "SDI_3") (pintype "unspecified"))
    )
    (net (code "415") (name "Net-(LED205-CKL)") (class "Default")
      (node (ref "LED205") (pin "4") (pinfunction "CKL_4") (pintype "unspecified"))
      (node (ref "LED206") (pin "6") (pinfunction "CKO_6") (pintype "unspecified"))
    )
    (net (code "416") (name "Net-(LED205-SDI)") (class "Default")
      (node (ref "LED205") (pin "3") (pinfunction "SDI_3") (pintype "unspecified"))
      (node (ref "LED206") (pin "1") (pinfunction "SDO_1") (pintype "unspecified"))
    )
    (net (code "417") (name "Net-(LED205-VDD)") (class "Default")
      (node (ref "C18") (pin "1") (pinfunction "1_1") (pintype "input"))
      (node (ref "LED205") (pin "5") (pinfunction "VDD_5") (pintype "unspecified"))
      (node (ref "LED216") (pin "5") (pinfunction "VDD_5") (pintype "unspecified"))
    )
    (net (code "418") (name "Net-(LED206-CKL)") (class "Default")
      (node (ref "LED206") (pin "4") (pinfunction "CKL_4") (pintype "unspecified"))
      (node (ref "LED207") (pin "6") (pinfunction "CKO_6") (pintype "unspecified"))
    )
    (net (code "419") (name "Net-(LED206-SDI)") (class "Default")
      (node (ref "LED206") (pin "3") (pinfunction "SDI_3") (pintype "unspecified"))
      (node (ref "LED207") (pin "1") (pinfunction "SDO_1") (pintype "unspecified"))
    )
    (net (code "420") (name "Net-(LED207-CKL)") (class "Default")
      (node (ref "LED207") (pin "4") (pinfunction "CKL_4") (pintype "unspecified"))
      (node (ref "LED208") (pin "6") (pinfunction "CKO_6") (pintype "unspecified"))
    )
    (net (code "421") (name "Net-(LED207-SDI)") (class "Default")
      (node (ref "LED207") (pin "3") (pinfunction "SDI_3") (pintype "unspecified"))
      (node (ref "LED208") (pin "1") (pinfunction "SDO_1") (pintype "unspecified"))
    )
    (net (code "422") (name "Net-(LED208-CKL)") (class "Default")
      (node (ref "LED208") (pin "4") (pinfunction "CKL_4") (pintype "unspecified"))
      (node (ref "LED209") (pin "6") (pinfunction "CKO_6") (pintype "unspecified"))
    )
    (net (code "423") (name "Net-(LED208-SDI)") (class "Default")
      (node (ref "LED208") (pin "3") (pinfunction "SDI_3") (pintype "unspecified"))
      (node (ref "LED209") (pin "1") (pinfunction "SDO_1") (pintype "unspecified"))
    )
    (net (code "424") (name "Net-(LED209-CKL)") (class "Default")
      (node (ref "LED209") (pin "4") (pinfunction "CKL_4") (pintype "unspecified"))
      (node (ref "LED210") (pin "6") (pinfunction "CKO_6") (pintype "unspecified"))
    )
    (net (code "425") (name "Net-(LED209-SDI)") (class "Default")
      (node (ref "LED209") (pin "3") (pinfunction "SDI_3") (pintype "unspecified"))
      (node (ref "LED210") (pin "1") (pinfunction "SDO_1") (pintype "unspecified"))
    )
    (net (code "426") (name "Net-(LED210-CKL)") (class "Default")
      (node (ref "LED210") (pin "4") (pinfunction "CKL_4") (pintype "unspecified"))
      (node (ref "LED211") (pin "6") (pinfunction "CKO_6") (pintype "unspecified"))
    )
    (net (code "427") (name "Net-(LED210-SDI)") (class "Default")
      (node (ref "LED210") (pin "3") (pinfunction "SDI_3") (pintype "unspecified"))
      (node (ref "LED211") (pin "1") (pinfunction "SDO_1") (pintype "unspecified"))
    )
    (net (code "428") (name "Net-(LED211-CKL)") (class "Default")
      (node (ref "LED211") (pin "4") (pinfunction "CKL_4") (pintype "unspecified"))
      (node (ref "LED212") (pin "6") (pinfunction "CKO_6") (pintype "unspecified"))
    )
    (net (code "429") (name "Net-(LED211-SDI)") (class "Default")
      (node (ref "LED211") (pin "3") (pinfunction "SDI_3") (pintype "unspecified"))
      (node (ref "LED212") (pin "1") (pinfunction "SDO_1") (pintype "unspecified"))
    )
    (net (code "430") (name "Net-(LED212-CKL)") (class "Default")
      (node (ref "LED212") (pin "4") (pinfunction "CKL_4") (pintype "unspecified"))
      (node (ref "LED213") (pin "6") (pinfunction "CKO_6") (pintype "unspecified"))
    )
    (net (code "431") (name "Net-(LED212-SDI)") (class "Default")
      (node (ref "LED212") (pin "3") (pinfunction "SDI_3") (pintype "unspecified"))
      (node (ref "LED213") (pin "1") (pinfunction "SDO_1") (pintype "unspecified"))
    )
    (net (code "432") (name "Net-(LED213-CKL)") (class "Default")
      (node (ref "LED213") (pin "4") (pinfunction "CKL_4") (pintype "unspecified"))
      (node (ref "LED214") (pin "6") (pinfunction "CKO_6") (pintype "unspecified"))
    )
    (net (code "433") (name "Net-(LED213-SDI)") (class "Default")
      (node (ref "LED213") (pin "3") (pinfunction "SDI_3") (pintype "unspecified"))
      (node (ref "LED214") (pin "1") (pinfunction "SDO_1") (pintype "unspecified"))
    )
    (net (code "434") (name "Net-(LED214-CKL)") (class "Default")
      (node (ref "LED214") (pin "4") (pinfunction "CKL_4") (pintype "unspecified"))
      (node (ref "LED215") (pin "6") (pinfunction "CKO_6") (pintype "unspecified"))
    )
    (net (code "435") (name "Net-(LED214-SDI)") (class "Default")
      (node (ref "LED214") (pin "3") (pinfunction "SDI_3") (pintype "unspecified"))
      (node (ref "LED215") (pin "1") (pinfunction "SDO_1") (pintype "unspecified"))
    )
    (net (code "436") (name "Net-(LED215-CKL)") (class "Default")
      (node (ref "LED215") (pin "4") (pinfunction "CKL_4") (pintype "unspecified"))
      (node (ref "LED216") (pin "6") (pinfunction "CKO_6") (pintype "unspecified"))
    )
    (net (code "437") (name "Net-(LED215-SDI)") (class "Default")
      (node (ref "LED215") (pin "3") (pinfunction "SDI_3") (pintype "unspecified"))
      (node (ref "LED216") (pin "1") (pinfunction "SDO_1") (pintype "unspecified"))
    )
    (net (code "438") (name "Net-(U2-FB)") (class "Default")
      (node (ref "R3") (pin "1") (pinfunction "1_1") (pintype "input"))
      (node (ref "R4") (pin "2") (pinfunction "2_2") (pintype "input"))
      (node (ref "U2") (pin "3") (pinfunction "FB_3") (pintype "unspecified"))
    )
    (net (code "439") (name "SDI") (class "Default")
      (node (ref "R2") (pin "2") (pinfunction "2_2") (pintype "input"))
      (node (ref "U1") (pin "11") (pinfunction "D10_11") (pintype "unspecified"))
    )
    (net (code "440") (name "VBAT(3.7V)") (class "Default")
      (node (ref "C20") (pin "2") (pinfunction "2_2") (pintype "input"))
      (node (ref "L1") (pin "2") (pinfunction "2_2") (pintype "input"))
      (node (ref "U1") (pin "15") (pinfunction "BAT+_15") (pintype "unspecified"))
      (node (ref "U2") (pin "5") (pinfunction "IN_5") (pintype "unspecified"))
    )
    (net (code "441") (name "unconnected-(LED2-GND-Pad2)") (class "Default")
      (node (ref "LED2") (pin "2") (pinfunction "GND_2") (pintype "unspecified"))
    )
    (net (code "442") (name "unconnected-(LED2-VDD-Pad5)") (class "Default")
      (node (ref "LED2") (pin "5") (pinfunction "VDD_5") (pintype "unspecified"))
    )
    (net (code "443") (name "unconnected-(LED3-GND-Pad2)") (class "Default")
      (node (ref "LED3") (pin "2") (pinfunction "GND_2") (pintype "unspecified"))
    )
    (net (code "444") (name "unconnected-(LED3-VDD-Pad5)") (class "Default")
      (node (ref "LED3") (pin "5") (pinfunction "VDD_5") (pintype "unspecified"))
    )
    (net (code "445") (name "unconnected-(LED4-GND-Pad2)") (class "Default")
      (node (ref "LED4") (pin "2") (pinfunction "GND_2") (pintype "unspecified"))
    )
    (net (code "446") (name "unconnected-(LED4-VDD-Pad5)") (class "Default")
      (node (ref "LED4") (pin "5") (pinfunction "VDD_5") (pintype "unspecified"))
    )
    (net (code "447") (name "unconnected-(LED5-GND-Pad2)") (class "Default")
      (node (ref "LED5") (pin "2") (pinfunction "GND_2") (pintype "unspecified"))
    )
    (net (code "448") (name "unconnected-(LED5-VDD-Pad5)") (class "Default")
      (node (ref "LED5") (pin "5") (pinfunction "VDD_5") (pintype "unspecified"))
    )
    (net (code "449") (name "unconnected-(LED6-GND-Pad2)") (class "Default")
      (node (ref "LED6") (pin "2") (pinfunction "GND_2") (pintype "unspecified"))
    )
    (net (code "450") (name "unconnected-(LED6-VDD-Pad5)") (class "Default")
      (node (ref "LED6") (pin "5") (pinfunction "VDD_5") (pintype "unspecified"))
    )
    (net (code "451") (name "unconnected-(LED7-GND-Pad2)") (class "Default")
      (node (ref "LED7") (pin "2") (pinfunction "GND_2") (pintype "unspecified"))
    )
    (net (code "452") (name "unconnected-(LED7-VDD-Pad5)") (class "Default")
      (node (ref "LED7") (pin "5") (pinfunction "VDD_5") (pintype "unspecified"))
    )
    (net (code "453") (name "unconnected-(LED8-GND-Pad2)") (class "Default")
      (node (ref "LED8") (pin "2") (pinfunction "GND_2") (pintype "unspecified"))
    )
    (net (code "454") (name "unconnected-(LED8-VDD-Pad5)") (class "Default")
      (node (ref "LED8") (pin "5") (pinfunction "VDD_5") (pintype "unspecified"))
    )
    (net (code "455") (name "unconnected-(LED9-GND-Pad2)") (class "Default")
      (node (ref "LED9") (pin "2") (pinfunction "GND_2") (pintype "unspecified"))
    )
    (net (code "456") (name "unconnected-(LED9-VDD-Pad5)") (class "Default")
      (node (ref "LED9") (pin "5") (pinfunction "VDD_5") (pintype "unspecified"))
    )
    (net (code "457") (name "unconnected-(LED10-GND-Pad2)") (class "Default")
      (node (ref "LED10") (pin "2") (pinfunction "GND_2") (pintype "unspecified"))
    )
    (net (code "458") (name "unconnected-(LED10-VDD-Pad5)") (class "Default")
      (node (ref "LED10") (pin "5") (pinfunction "VDD_5") (pintype "unspecified"))
    )
    (net (code "459") (name "unconnected-(LED11-GND-Pad2)") (class "Default")
      (node (ref "LED11") (pin "2") (pinfunction "GND_2") (pintype "unspecified"))
    )
    (net (code "460") (name "unconnected-(LED11-VDD-Pad5)") (class "Default")
      (node (ref "LED11") (pin "5") (pinfunction "VDD_5") (pintype "unspecified"))
    )
    (net (code "461") (name "unconnected-(LED14-GND-Pad2)") (class "Default")
      (node (ref "LED14") (pin "2") (pinfunction "GND_2") (pintype "unspecified"))
    )
    (net (code "462") (name "unconnected-(LED14-VDD-Pad5)") (class "Default")
      (node (ref "LED14") (pin "5") (pinfunction "VDD_5") (pintype "unspecified"))
    )
    (net (code "463") (name "unconnected-(LED15-GND-Pad2)") (class "Default")
      (node (ref "LED15") (pin "2") (pinfunction "GND_2") (pintype "unspecified"))
    )
    (net (code "464") (name "unconnected-(LED15-VDD-Pad5)") (class "Default")
      (node (ref "LED15") (pin "5") (pinfunction "VDD_5") (pintype "unspecified"))
    )
    (net (code "465") (name "unconnected-(LED16-GND-Pad2)") (class "Default")
      (node (ref "LED16") (pin "2") (pinfunction "GND_2") (pintype "unspecified"))
    )
    (net (code "466") (name "unconnected-(LED16-VDD-Pad5)") (class "Default")
      (node (ref "LED16") (pin "5") (pinfunction "VDD_5") (pintype "unspecified"))
    )
    (net (code "467") (name "unconnected-(LED17-GND-Pad2)") (class "Default")
      (node (ref "LED17") (pin "2") (pinfunction "GND_2") (pintype "unspecified"))
    )
    (net (code "468") (name "unconnected-(LED17-VDD-Pad5)") (class "Default")
      (node (ref "LED17") (pin "5") (pinfunction "VDD_5") (pintype "unspecified"))
    )
    (net (code "469") (name "unconnected-(LED18-GND-Pad2)") (class "Default")
      (node (ref "LED18") (pin "2") (pinfunction "GND_2") (pintype "unspecified"))
    )
    (net (code "470") (name "unconnected-(LED18-VDD-Pad5)") (class "Default")
      (node (ref "LED18") (pin "5") (pinfunction "VDD_5") (pintype "unspecified"))
    )
    (net (code "471") (name "unconnected-(LED19-GND-Pad2)") (class "Default")
      (node (ref "LED19") (pin "2") (pinfunction "GND_2") (pintype "unspecified"))
    )
    (net (code "472") (name "unconnected-(LED19-VDD-Pad5)") (class "Default")
      (node (ref "LED19") (pin "5") (pinfunction "VDD_5") (pintype "unspecified"))
    )
    (net (code "473") (name "unconnected-(LED20-GND-Pad2)") (class "Default")
      (node (ref "LED20") (pin "2") (pinfunction "GND_2") (pintype "unspecified"))
    )
    (net (code "474") (name "unconnected-(LED20-VDD-Pad5)") (class "Default")
      (node (ref "LED20") (pin "5") (pinfunction "VDD_5") (pintype "unspecified"))
    )
    (net (code "475") (name "unconnected-(LED21-GND-Pad2)") (class "Default")
      (node (ref "LED21") (pin "2") (pinfunction "GND_2") (pintype "unspecified"))
    )
    (net (code "476") (name "unconnected-(LED21-VDD-Pad5)") (class "Default")
      (node (ref "LED21") (pin "5") (pinfunction "VDD_5") (pintype "unspecified"))
    )
    (net (code "477") (name "unconnected-(LED22-GND-Pad2)") (class "Default")
      (node (ref "LED22") (pin "2") (pinfunction "GND_2") (pintype "unspecified"))
    )
    (net (code "478") (name "unconnected-(LED22-VDD-Pad5)") (class "Default")
      (node (ref "LED22") (pin "5") (pinfunction "VDD_5") (pintype "unspecified"))
    )
    (net (code "479") (name "unconnected-(LED23-GND-Pad2)") (class "Default")
      (node (ref "LED23") (pin "2") (pinfunction "GND_2") (pintype "unspecified"))
    )
    (net (code "480") (name "unconnected-(LED23-VDD-Pad5)") (class "Default")
      (node (ref "LED23") (pin "5") (pinfunction "VDD_5") (pintype "unspecified"))
    )
    (net (code "481") (name "unconnected-(LED26-GND-Pad2)") (class "Default")
      (node (ref "LED26") (pin "2") (pinfunction "GND_2") (pintype "unspecified"))
    )
    (net (code "482") (name "unconnected-(LED26-VDD-Pad5)") (class "Default")
      (node (ref "LED26") (pin "5") (pinfunction "VDD_5") (pintype "unspecified"))
    )
    (net (code "483") (name "unconnected-(LED27-GND-Pad2)") (class "Default")
      (node (ref "LED27") (pin "2") (pinfunction "GND_2") (pintype "unspecified"))
    )
    (net (code "484") (name "unconnected-(LED27-VDD-Pad5)") (class "Default")
      (node (ref "LED27") (pin "5") (pinfunction "VDD_5") (pintype "unspecified"))
    )
    (net (code "485") (name "unconnected-(LED28-GND-Pad2)") (class "Default")
      (node (ref "LED28") (pin "2") (pinfunction "GND_2") (pintype "unspecified"))
    )
    (net (code "486") (name "unconnected-(LED28-VDD-Pad5)") (class "Default")
      (node (ref "LED28") (pin "5") (pinfunction "VDD_5") (pintype "unspecified"))
    )
    (net (code "487") (name "unconnected-(LED29-GND-Pad2)") (class "Default")
      (node (ref "LED29") (pin "2") (pinfunction "GND_2") (pintype "unspecified"))
    )
    (net (code "488") (name "unconnected-(LED29-VDD-Pad5)") (class "Default")
      (node (ref "LED29") (pin "5") (pinfunction "VDD_5") (pintype "unspecified"))
    )
    (net (code "489") (name "unconnected-(LED30-GND-Pad2)") (class "Default")
      (node (ref "LED30") (pin "2") (pinfunction "GND_2") (pintype "unspecified"))
    )
    (net (code "490") (name "unconnected-(LED30-VDD-Pad5)") (class "Default")
      (node (ref "LED30") (pin "5") (pinfunction "VDD_5") (pintype "unspecified"))
    )
    (net (code "491") (name "unconnected-(LED31-GND-Pad2)") (class "Default")
      (node (ref "LED31") (pin "2") (pinfunction "GND_2") (pintype "unspecified"))
    )
    (net (code "492") (name "unconnected-(LED31-VDD-Pad5)") (class "Default")
      (node (ref "LED31") (pin "5") (pinfunction "VDD_5") (pintype "unspecified"))
    )
    (net (code "493") (name "unconnected-(LED32-GND-Pad2)") (class "Default")
      (node (ref "LED32") (pin "2") (pinfunction "GND_2") (pintype "unspecified"))
    )
    (net (code "494") (name "unconnected-(LED32-VDD-Pad5)") (class "Default")
      (node (ref "LED32") (pin "5") (pinfunction "VDD_5") (pintype "unspecified"))
    )
    (net (code "495") (name "unconnected-(LED33-GND-Pad2)") (class "Default")
      (node (ref "LED33") (pin "2") (pinfunction "GND_2") (pintype "unspecified"))
    )
    (net (code "496") (name "unconnected-(LED33-VDD-Pad5)") (class "Default")
      (node (ref "LED33") (pin "5") (pinfunction "VDD_5") (pintype "unspecified"))
    )
    (net (code "497") (name "unconnected-(LED34-GND-Pad2)") (class "Default")
      (node (ref "LED34") (pin "2") (pinfunction "GND_2") (pintype "unspecified"))
    )
    (net (code "498") (name "unconnected-(LED34-VDD-Pad5)") (class "Default")
      (node (ref "LED34") (pin "5") (pinfunction "VDD_5") (pintype "unspecified"))
    )
    (net (code "499") (name "unconnected-(LED35-GND-Pad2)") (class "Default")
      (node (ref "LED35") (pin "2") (pinfunction "GND_2") (pintype "unspecified"))
    )
    (net (code "500") (name "unconnected-(LED35-VDD-Pad5)") (class "Default")
      (node (ref "LED35") (pin "5") (pinfunction "VDD_5") (pintype "unspecified"))
    )
    (net (code "501") (name "unconnected-(LED38-GND-Pad2)") (class "Default")
      (node (ref "LED38") (pin "2") (pinfunction "GND_2") (pintype "unspecified"))
    )
    (net (code "502") (name "unconnected-(LED38-VDD-Pad5)") (class "Default")
      (node (ref "LED38") (pin "5") (pinfunction "VDD_5") (pintype "unspecified"))
    )
    (net (code "503") (name "unconnected-(LED39-GND-Pad2)") (class "Default")
      (node (ref "LED39") (pin "2") (pinfunction "GND_2") (pintype "unspecified"))
    )
    (net (code "504") (name "unconnected-(LED39-VDD-Pad5)") (class "Default")
      (node (ref "LED39") (pin "5") (pinfunction "VDD_5") (pintype "unspecified"))
    )
    (net (code "505") (name "unconnected-(LED40-GND-Pad2)") (class "Default")
      (node (ref "LED40") (pin "2") (pinfunction "GND_2") (pintype "unspecified"))
    )
    (net (code "506") (name "unconnected-(LED40-VDD-Pad5)") (class "Default")
      (node (ref "LED40") (pin "5") (pinfunction "VDD_5") (pintype "unspecified"))
    )
    (net (code "507") (name "unconnected-(LED41-GND-Pad2)") (class "Default")
      (node (ref "LED41") (pin "2") (pinfunction "GND_2") (pintype "unspecified"))
    )
    (net (code "508") (name "unconnected-(LED41-VDD-Pad5)") (class "Default")
      (node (ref "LED41") (pin "5") (pinfunction "VDD_5") (pintype "unspecified"))
    )
    (net (code "509") (name "unconnected-(LED42-GND-Pad2)") (class "Default")
      (node (ref "LED42") (pin "2") (pinfunction "GND_2") (pintype "unspecified"))
    )
    (net (code "510") (name "unconnected-(LED42-VDD-Pad5)") (class "Default")
      (node (ref "LED42") (pin "5") (pinfunction "VDD_5") (pintype "unspecified"))
    )
    (net (code "511") (name "unconnected-(LED43-GND-Pad2)") (class "Default")
      (node (ref "LED43") (pin "2") (pinfunction "GND_2") (pintype "unspecified"))
    )
    (net (code "512") (name "unconnected-(LED43-VDD-Pad5)") (class "Default")
      (node (ref "LED43") (pin "5") (pinfunction "VDD_5") (pintype "unspecified"))
    )
    (net (code "513") (name "unconnected-(LED44-GND-Pad2)") (class "Default")
      (node (ref "LED44") (pin "2") (pinfunction "GND_2") (pintype "unspecified"))
    )
    (net (code "514") (name "unconnected-(LED44-VDD-Pad5)") (class "Default")
      (node (ref "LED44") (pin "5") (pinfunction "VDD_5") (pintype "unspecified"))
    )
    (net (code "515") (name "unconnected-(LED45-GND-Pad2)") (class "Default")
      (node (ref "LED45") (pin "2") (pinfunction "GND_2") (pintype "unspecified"))
    )
    (net (code "516") (name "unconnected-(LED45-VDD-Pad5)") (class "Default")
      (node (ref "LED45") (pin "5") (pinfunction "VDD_5") (pintype "unspecified"))
    )
    (net (code "517") (name "unconnected-(LED46-GND-Pad2)") (class "Default")
      (node (ref "LED46") (pin "2") (pinfunction "GND_2") (pintype "unspecified"))
    )
    (net (code "518") (name "unconnected-(LED46-VDD-Pad5)") (class "Default")
      (node (ref "LED46") (pin "5") (pinfunction "VDD_5") (pintype "unspecified"))
    )
    (net (code "519") (name "unconnected-(LED47-GND-Pad2)") (class "Default")
      (node (ref "LED47") (pin "2") (pinfunction "GND_2") (pintype "unspecified"))
    )
    (net (code "520") (name "unconnected-(LED47-VDD-Pad5)") (class "Default")
      (node (ref "LED47") (pin "5") (pinfunction "VDD_5") (pintype "unspecified"))
    )
    (net (code "521") (name "unconnected-(LED49-SDI-Pad3)") (class "Default")
      (node (ref "LED49") (pin "3") (pinfunction "SDI_3") (pintype "unspecified"))
    )
    (net (code "522") (name "unconnected-(LED50-GND-Pad2)") (class "Default")
      (node (ref "LED50") (pin "2") (pinfunction "GND_2") (pintype "unspecified"))
    )
    (net (code "523") (name "unconnected-(LED50-VDD-Pad5)") (class "Default")
      (node (ref "LED50") (pin "5") (pinfunction "VDD_5") (pintype "unspecified"))
    )
    (net (code "524") (name "unconnected-(LED51-GND-Pad2)") (class "Default")
      (node (ref "LED51") (pin "2") (pinfunction "GND_2") (pintype "unspecified"))
    )
    (net (code "525") (name "unconnected-(LED51-VDD-Pad5)") (class "Default")
      (node (ref "LED51") (pin "5") (pinfunction "VDD_5") (pintype "unspecified"))
    )
    (net (code "526") (name "unconnected-(LED52-GND-Pad2)") (class "Default")
      (node (ref "LED52") (pin "2") (pinfunction "GND_2") (pintype "unspecified"))
    )
    (net (code "527") (name "unconnected-(LED52-VDD-Pad5)") (class "Default")
      (node (ref "LED52") (pin "5") (pinfunction "VDD_5") (pintype "unspecified"))
    )
    (net (code "528") (name "unconnected-(LED53-GND-Pad2)") (class "Default")
      (node (ref "LED53") (pin "2") (pinfunction "GND_2") (pintype "unspecified"))
    )
    (net (code "529") (name "unconnected-(LED53-VDD-Pad5)") (class "Default")
      (node (ref "LED53") (pin "5") (pinfunction "VDD_5") (pintype "unspecified"))
    )
    (net (code "530") (name "unconnected-(LED54-GND-Pad2)") (class "Default")
      (node (ref "LED54") (pin "2") (pinfunction "GND_2") (pintype "unspecified"))
    )
    (net (code "531") (name "unconnected-(LED54-VDD-Pad5)") (class "Default")
      (node (ref "LED54") (pin "5") (pinfunction "VDD_5") (pintype "unspecified"))
    )
    (net (code "532") (name "unconnected-(LED55-GND-Pad2)") (class "Default")
      (node (ref "LED55") (pin "2") (pinfunction "GND_2") (pintype "unspecified"))
    )
    (net (code "533") (name "unconnected-(LED55-VDD-Pad5)") (class "Default")
      (node (ref "LED55") (pin "5") (pinfunction "VDD_5") (pintype "unspecified"))
    )
    (net (code "534") (name "unconnected-(LED56-GND-Pad2)") (class "Default")
      (node (ref "LED56") (pin "2") (pinfunction "GND_2") (pintype "unspecified"))
    )
    (net (code "535") (name "unconnected-(LED56-VDD-Pad5)") (class "Default")
      (node (ref "LED56") (pin "5") (pinfunction "VDD_5") (pintype "unspecified"))
    )
    (net (code "536") (name "unconnected-(LED57-GND-Pad2)") (class "Default")
      (node (ref "LED57") (pin "2") (pinfunction "GND_2") (pintype "unspecified"))
    )
    (net (code "537") (name "unconnected-(LED57-VDD-Pad5)") (class "Default")
      (node (ref "LED57") (pin "5") (pinfunction "VDD_5") (pintype "unspecified"))
    )
    (net (code "538") (name "unconnected-(LED58-GND-Pad2)") (class "Default")
      (node (ref "LED58") (pin "2") (pinfunction "GND_2") (pintype "unspecified"))
    )
    (net (code "539") (name "unconnected-(LED58-VDD-Pad5)") (class "Default")
      (node (ref "LED58") (pin "5") (pinfunction "VDD_5") (pintype "unspecified"))
    )
    (net (code "540") (name "unconnected-(LED59-GND-Pad2)") (class "Default")
      (node (ref "LED59") (pin "2") (pinfunction "GND_2") (pintype "unspecified"))
    )
    (net (code "541") (name "unconnected-(LED59-VDD-Pad5)") (class "Default")
      (node (ref "LED59") (pin "5") (pinfunction "VDD_5") (pintype "unspecified"))
    )
    (net (code "542") (name "unconnected-(LED62-GND-Pad2)") (class "Default")
      (node (ref "LED62") (pin "2") (pinfunction "GND_2") (pintype "unspecified"))
    )
    (net (code "543") (name "unconnected-(LED62-VDD-Pad5)") (class "Default")
      (node (ref "LED62") (pin "5") (pinfunction "VDD_5") (pintype "unspecified"))
    )
    (net (code "544") (name "unconnected-(LED63-GND-Pad2)") (class "Default")
      (node (ref "LED63") (pin "2") (pinfunction "GND_2") (pintype "unspecified"))
    )
    (net (code "545") (name "unconnected-(LED63-VDD-Pad5)") (class "Default")
      (node (ref "LED63") (pin "5") (pinfunction "VDD_5") (pintype "unspecified"))
    )
    (net (code "546") (name "unconnected-(LED64-GND-Pad2)") (class "Default")
      (node (ref "LED64") (pin "2") (pinfunction "GND_2") (pintype "unspecified"))
    )
    (net (code "547") (name "unconnected-(LED64-VDD-Pad5)") (class "Default")
      (node (ref "LED64") (pin "5") (pinfunction "VDD_5") (pintype "unspecified"))
    )
    (net (code "548") (name "unconnected-(LED65-GND-Pad2)") (class "Default")
      (node (ref "LED65") (pin "2") (pinfunction "GND_2") (pintype "unspecified"))
    )
    (net (code "549") (name "unconnected-(LED65-VDD-Pad5)") (class "Default")
      (node (ref "LED65") (pin "5") (pinfunction "VDD_5") (pintype "unspecified"))
    )
    (net (code "550") (name "unconnected-(LED66-GND-Pad2)") (class "Default")
      (node (ref "LED66") (pin "2") (pinfunction "GND_2") (pintype "unspecified"))
    )
    (net (code "551") (name "unconnected-(LED66-VDD-Pad5)") (class "Default")
      (node (ref "LED66") (pin "5") (pinfunction "VDD_5") (pintype "unspecified"))
    )
    (net (code "552") (name "unconnected-(LED67-GND-Pad2)") (class "Default")
      (node (ref "LED67") (pin "2") (pinfunction "GND_2") (pintype "unspecified"))
    )
    (net (code "553") (name "unconnected-(LED67-VDD-Pad5)") (class "Default")
      (node (ref "LED67") (pin "5") (pinfunction "VDD_5") (pintype "unspecified"))
    )
    (net (code "554") (name "unconnected-(LED68-GND-Pad2)") (class "Default")
      (node (ref "LED68") (pin "2") (pinfunction "GND_2") (pintype "unspecified"))
    )
    (net (code "555") (name "unconnected-(LED68-VDD-Pad5)") (class "Default")
      (node (ref "LED68") (pin "5") (pinfunction "VDD_5") (pintype "unspecified"))
    )
    (net (code "556") (name "unconnected-(LED69-GND-Pad2)") (class "Default")
      (node (ref "LED69") (pin "2") (pinfunction "GND_2") (pintype "unspecified"))
    )
    (net (code "557") (name "unconnected-(LED69-VDD-Pad5)") (class "Default")
      (node (ref "LED69") (pin "5") (pinfunction "VDD_5") (pintype "unspecified"))
    )
    (net (code "558") (name "unconnected-(LED70-GND-Pad2)") (class "Default")
      (node (ref "LED70") (pin "2") (pinfunction "GND_2") (pintype "unspecified"))
    )
    (net (code "559") (name "unconnected-(LED70-VDD-Pad5)") (class "Default")
      (node (ref "LED70") (pin "5") (pinfunction "VDD_5") (pintype "unspecified"))
    )
    (net (code "560") (name "unconnected-(LED71-GND-Pad2)") (class "Default")
      (node (ref "LED71") (pin "2") (pinfunction "GND_2") (pintype "unspecified"))
    )
    (net (code "561") (name "unconnected-(LED71-VDD-Pad5)") (class "Default")
      (node (ref "LED71") (pin "5") (pinfunction "VDD_5") (pintype "unspecified"))
    )
    (net (code "562") (name "unconnected-(LED74-GND-Pad2)") (class "Default")
      (node (ref "LED74") (pin "2") (pinfunction "GND_2") (pintype "unspecified"))
    )
    (net (code "563") (name "unconnected-(LED74-VDD-Pad5)") (class "Default")
      (node (ref "LED74") (pin "5") (pinfunction "VDD_5") (pintype "unspecified"))
    )
    (net (code "564") (name "unconnected-(LED75-GND-Pad2)") (class "Default")
      (node (ref "LED75") (pin "2") (pinfunction "GND_2") (pintype "unspecified"))
    )
    (net (code "565") (name "unconnected-(LED75-VDD-Pad5)") (class "Default")
      (node (ref "LED75") (pin "5") (pinfunction "VDD_5") (pintype "unspecified"))
    )
    (net (code "566") (name "unconnected-(LED76-GND-Pad2)") (class "Default")
      (node (ref "LED76") (pin "2") (pinfunction "GND_2") (pintype "unspecified"))
    )
    (net (code "567") (name "unconnected-(LED76-VDD-Pad5)") (class "Default")
      (node (ref "LED76") (pin "5") (pinfunction "VDD_5") (pintype "unspecified"))
    )
    (net (code "568") (name "unconnected-(LED77-GND-Pad2)") (class "Default")
      (node (ref "LED77") (pin "2") (pinfunction "GND_2") (pintype "unspecified"))
    )
    (net (code "569") (name "unconnected-(LED77-VDD-Pad5)") (class "Default")
      (node (ref "LED77") (pin "5") (pinfunction "VDD_5") (pintype "unspecified"))
    )
    (net (code "570") (name "unconnected-(LED78-GND-Pad2)") (class "Default")
      (node (ref "LED78") (pin "2") (pinfunction "GND_2") (pintype "unspecified"))
    )
    (net (code "571") (name "unconnected-(LED78-VDD-Pad5)") (class "Default")
      (node (ref "LED78") (pin "5") (pinfunction "VDD_5") (pintype "unspecified"))
    )
    (net (code "572") (name "unconnected-(LED79-GND-Pad2)") (class "Default")
      (node (ref "LED79") (pin "2") (pinfunction "GND_2") (pintype "unspecified"))
    )
    (net (code "573") (name "unconnected-(LED79-VDD-Pad5)") (class "Default")
      (node (ref "LED79") (pin "5") (pinfunction "VDD_5") (pintype "unspecified"))
    )
    (net (code "574") (name "unconnected-(LED80-GND-Pad2)") (class "Default")
      (node (ref "LED80") (pin "2") (pinfunction "GND_2") (pintype "unspecified"))
    )
    (net (code "575") (name "unconnected-(LED80-VDD-Pad5)") (class "Default")
      (node (ref "LED80") (pin "5") (pinfunction "VDD_5") (pintype "unspecified"))
    )
    (net (code "576") (name "unconnected-(LED81-GND-Pad2)") (class "Default")
      (node (ref "LED81") (pin "2") (pinfunction "GND_2") (pintype "unspecified"))
    )
    (net (code "577") (name "unconnected-(LED81-VDD-Pad5)") (class "Default")
      (node (ref "LED81") (pin "5") (pinfunction "VDD_5") (pintype "unspecified"))
    )
    (net (code "578") (name "unconnected-(LED82-GND-Pad2)") (class "Default")
      (node (ref "LED82") (pin "2") (pinfunction "GND_2") (pintype "unspecified"))
    )
    (net (code "579") (name "unconnected-(LED82-VDD-Pad5)") (class "Default")
      (node (ref "LED82") (pin "5") (pinfunction "VDD_5") (pintype "unspecified"))
    )
    (net (code "580") (name "unconnected-(LED83-GND-Pad2)") (class "Default")
      (node (ref "LED83") (pin "2") (pinfunction "GND_2") (pintype "unspecified"))
    )
    (net (code "581") (name "unconnected-(LED83-VDD-Pad5)") (class "Default")
      (node (ref "LED83") (pin "5") (pinfunction "VDD_5") (pintype "unspecified"))
    )
    (net (code "582") (name "unconnected-(LED86-GND-Pad2)") (class "Default")
      (node (ref "LED86") (pin "2") (pinfunction "GND_2") (pintype "unspecified"))
    )
    (net (code "583") (name "unconnected-(LED86-VDD-Pad5)") (class "Default")
      (node (ref "LED86") (pin "5") (pinfunction "VDD_5") (pintype "unspecified"))
    )
    (net (code "584") (name "unconnected-(LED87-GND-Pad2)") (class "Default")
      (node (ref "LED87") (pin "2") (pinfunction "GND_2") (pintype "unspecified"))
    )
    (net (code "585") (name "unconnected-(LED87-VDD-Pad5)") (class "Default")
      (node (ref "LED87") (pin "5") (pinfunction "VDD_5") (pintype "unspecified"))
    )
    (net (code "586") (name "unconnected-(LED88-GND-Pad2)") (class "Default")
      (node (ref "LED88") (pin "2") (pinfunction "GND_2") (pintype "unspecified"))
    )
    (net (code "587") (name "unconnected-(LED88-VDD-Pad5)") (class "Default")
      (node (ref "LED88") (pin "5") (pinfunction "VDD_5") (pintype "unspecified"))
    )
    (net (code "588") (name "unconnected-(LED89-GND-Pad2)") (class "Default")
      (node (ref "LED89") (pin "2") (pinfunction "GND_2") (pintype "unspecified"))
    )
    (net (code "589") (name "unconnected-(LED89-VDD-Pad5)") (class "Default")
      (node (ref "LED89") (pin "5") (pinfunction "VDD_5") (pintype "unspecified"))
    )
    (net (code "590") (name "unconnected-(LED90-GND-Pad2)") (class "Default")
      (node (ref "LED90") (pin "2") (pinfunction "GND_2") (pintype "unspecified"))
    )
    (net (code "591") (name "unconnected-(LED90-VDD-Pad5)") (class "Default")
      (node (ref "LED90") (pin "5") (pinfunction "VDD_5") (pintype "unspecified"))
    )
    (net (code "592") (name "unconnected-(LED91-GND-Pad2)") (class "Default")
      (node (ref "LED91") (pin "2") (pinfunction "GND_2") (pintype "unspecified"))
    )
    (net (code "593") (name "unconnected-(LED91-VDD-Pad5)") (class "Default")
      (node (ref "LED91") (pin "5") (pinfunction "VDD_5") (pintype "unspecified"))
    )
    (net (code "594") (name "unconnected-(LED92-GND-Pad2)") (class "Default")
      (node (ref "LED92") (pin "2") (pinfunction "GND_2") (pintype "unspecified"))
    )
    (net (code "595") (name "unconnected-(LED92-VDD-Pad5)") (class "Default")
      (node (ref "LED92") (pin "5") (pinfunction "VDD_5") (pintype "unspecified"))
    )
    (net (code "596") (name "unconnected-(LED93-GND-Pad2)") (class "Default")
      (node (ref "LED93") (pin "2") (pinfunction "GND_2") (pintype "unspecified"))
    )
    (net (code "597") (name "unconnected-(LED93-VDD-Pad5)") (class "Default")
      (node (ref "LED93") (pin "5") (pinfunction "VDD_5") (pintype "unspecified"))
    )
    (net (code "598") (name "unconnected-(LED94-GND-Pad2)") (class "Default")
      (node (ref "LED94") (pin "2") (pinfunction "GND_2") (pintype "unspecified"))
    )
    (net (code "599") (name "unconnected-(LED94-VDD-Pad5)") (class "Default")
      (node (ref "LED94") (pin "5") (pinfunction "VDD_5") (pintype "unspecified"))
    )
    (net (code "600") (name "unconnected-(LED95-GND-Pad2)") (class "Default")
      (node (ref "LED95") (pin "2") (pinfunction "GND_2") (pintype "unspecified"))
    )
    (net (code "601") (name "unconnected-(LED95-VDD-Pad5)") (class "Default")
      (node (ref "LED95") (pin "5") (pinfunction "VDD_5") (pintype "unspecified"))
    )
    (net (code "602") (name "unconnected-(LED98-GND-Pad2)") (class "Default")
      (node (ref "LED98") (pin "2") (pinfunction "GND_2") (pintype "unspecified"))
    )
    (net (code "603") (name "unconnected-(LED98-VDD-Pad5)") (class "Default")
      (node (ref "LED98") (pin "5") (pinfunction "VDD_5") (pintype "unspecified"))
    )
    (net (code "604") (name "unconnected-(LED99-GND-Pad2)") (class "Default")
      (node (ref "LED99") (pin "2") (pinfunction "GND_2") (pintype "unspecified"))
    )
    (net (code "605") (name "unconnected-(LED99-VDD-Pad5)") (class "Default")
      (node (ref "LED99") (pin "5") (pinfunction "VDD_5") (pintype "unspecified"))
    )
    (net (code "606") (name "unconnected-(LED100-GND-Pad2)") (class "Default")
      (node (ref "LED100") (pin "2") (pinfunction "GND_2") (pintype "unspecified"))
    )
    (net (code "607") (name "unconnected-(LED100-VDD-Pad5)") (class "Default")
      (node (ref "LED100") (pin "5") (pinfunction "VDD_5") (pintype "unspecified"))
    )
    (net (code "608") (name "unconnected-(LED101-GND-Pad2)") (class "Default")
      (node (ref "LED101") (pin "2") (pinfunction "GND_2") (pintype "unspecified"))
    )
    (net (code "609") (name "unconnected-(LED101-VDD-Pad5)") (class "Default")
      (node (ref "LED101") (pin "5") (pinfunction "VDD_5") (pintype "unspecified"))
    )
    (net (code "610") (name "unconnected-(LED102-GND-Pad2)") (class "Default")
      (node (ref "LED102") (pin "2") (pinfunction "GND_2") (pintype "unspecified"))
    )
    (net (code "611") (name "unconnected-(LED102-VDD-Pad5)") (class "Default")
      (node (ref "LED102") (pin "5") (pinfunction "VDD_5") (pintype "unspecified"))
    )
    (net (code "612") (name "unconnected-(LED103-GND-Pad2)") (class "Default")
      (node (ref "LED103") (pin "2") (pinfunction "GND_2") (pintype "unspecified"))
    )
    (net (code "613") (name "unconnected-(LED103-VDD-Pad5)") (class "Default")
      (node (ref "LED103") (pin "5") (pinfunction "VDD_5") (pintype "unspecified"))
    )
    (net (code "614") (name "unconnected-(LED104-GND-Pad2)") (class "Default")
      (node (ref "LED104") (pin "2") (pinfunction "GND_2") (pintype "unspecified"))
    )
    (net (code "615") (name "unconnected-(LED104-VDD-Pad5)") (class "Default")
      (node (ref "LED104") (pin "5") (pinfunction "VDD_5") (pintype "unspecified"))
    )
    (net (code "616") (name "unconnected-(LED105-GND-Pad2)") (class "Default")
      (node (ref "LED105") (pin "2") (pinfunction "GND_2") (pintype "unspecified"))
    )
    (net (code "617") (name "unconnected-(LED105-VDD-Pad5)") (class "Default")
      (node (ref "LED105") (pin "5") (pinfunction "VDD_5") (pintype "unspecified"))
    )
    (net (code "618") (name "unconnected-(LED106-GND-Pad2)") (class "Default")
      (node (ref "LED106") (pin "2") (pinfunction "GND_2") (pintype "unspecified"))
    )
    (net (code "619") (name "unconnected-(LED106-VDD-Pad5)") (class "Default")
      (node (ref "LED106") (pin "5") (pinfunction "VDD_5") (pintype "unspecified"))
    )
    (net (code "620") (name "unconnected-(LED107-GND-Pad2)") (class "Default")
      (node (ref "LED107") (pin "2") (pinfunction "GND_2") (pintype "unspecified"))
    )
    (net (code "621") (name "unconnected-(LED107-VDD-Pad5)") (class "Default")
      (node (ref "LED107") (pin "5") (pinfunction "VDD_5") (pintype "unspecified"))
    )
    (net (code "622") (name "unconnected-(LED110-GND-Pad2)") (class "Default")
      (node (ref "LED110") (pin "2") (pinfunction "GND_2") (pintype "unspecified"))
    )
    (net (code "623") (name "unconnected-(LED110-VDD-Pad5)") (class "Default")
      (node (ref "LED110") (pin "5") (pinfunction "VDD_5") (pintype "unspecified"))
    )
    (net (code "624") (name "unconnected-(LED111-GND-Pad2)") (class "Default")
      (node (ref "LED111") (pin "2") (pinfunction "GND_2") (pintype "unspecified"))
    )
    (net (code "625") (name "unconnected-(LED111-VDD-Pad5)") (class "Default")
      (node (ref "LED111") (pin "5") (pinfunction "VDD_5") (pintype "unspecified"))
    )
    (net (code "626") (name "unconnected-(LED112-GND-Pad2)") (class "Default")
      (node (ref "LED112") (pin "2") (pinfunction "GND_2") (pintype "unspecified"))
    )
    (net (code "627") (name "unconnected-(LED112-VDD-Pad5)") (class "Default")
      (node (ref "LED112") (pin "5") (pinfunction "VDD_5") (pintype "unspecified"))
    )
    (net (code "628") (name "unconnected-(LED113-GND-Pad2)") (class "Default")
      (node (ref "LED113") (pin "2") (pinfunction "GND_2") (pintype "unspecified"))
    )
    (net (code "629") (name "unconnected-(LED113-VDD-Pad5)") (class "Default")
      (node (ref "LED113") (pin "5") (pinfunction "VDD_5") (pintype "unspecified"))
    )
    (net (code "630") (name "unconnected-(LED114-GND-Pad2)") (class "Default")
      (node (ref "LED114") (pin "2") (pinfunction "GND_2") (pintype "unspecified"))
    )
    (net (code "631") (name "unconnected-(LED114-VDD-Pad5)") (class "Default")
      (node (ref "LED114") (pin "5") (pinfunction "VDD_5") (pintype "unspecified"))
    )
    (net (code "632") (name "unconnected-(LED115-GND-Pad2)") (class "Default")
      (node (ref "LED115") (pin "2") (pinfunction "GND_2") (pintype "unspecified"))
    )
    (net (code "633") (name "unconnected-(LED115-VDD-Pad5)") (class "Default")
      (node (ref "LED115") (pin "5") (pinfunction "VDD_5") (pintype "unspecified"))
    )
    (net (code "634") (name "unconnected-(LED116-GND-Pad2)") (class "Default")
      (node (ref "LED116") (pin "2") (pinfunction "GND_2") (pintype "unspecified"))
    )
    (net (code "635") (name "unconnected-(LED116-VDD-Pad5)") (class "Default")
      (node (ref "LED116") (pin "5") (pinfunction "VDD_5") (pintype "unspecified"))
    )
    (net (code "636") (name "unconnected-(LED117-GND-Pad2)") (class "Default")
      (node (ref "LED117") (pin "2") (pinfunction "GND_2") (pintype "unspecified"))
    )
    (net (code "637") (name "unconnected-(LED117-VDD-Pad5)") (class "Default")
      (node (ref "LED117") (pin "5") (pinfunction "VDD_5") (pintype "unspecified"))
    )
    (net (code "638") (name "unconnected-(LED118-GND-Pad2)") (class "Default")
      (node (ref "LED118") (pin "2") (pinfunction "GND_2") (pintype "unspecified"))
    )
    (net (code "639") (name "unconnected-(LED118-VDD-Pad5)") (class "Default")
      (node (ref "LED118") (pin "5") (pinfunction "VDD_5") (pintype "unspecified"))
    )
    (net (code "640") (name "unconnected-(LED119-GND-Pad2)") (class "Default")
      (node (ref "LED119") (pin "2") (pinfunction "GND_2") (pintype "unspecified"))
    )
    (net (code "641") (name "unconnected-(LED119-VDD-Pad5)") (class "Default")
      (node (ref "LED119") (pin "5") (pinfunction "VDD_5") (pintype "unspecified"))
    )
    (net (code "642") (name "unconnected-(LED122-GND-Pad2)") (class "Default")
      (node (ref "LED122") (pin "2") (pinfunction "GND_2") (pintype "unspecified"))
    )
    (net (code "643") (name "unconnected-(LED122-VDD-Pad5)") (class "Default")
      (node (ref "LED122") (pin "5") (pinfunction "VDD_5") (pintype "unspecified"))
    )
    (net (code "644") (name "unconnected-(LED123-GND-Pad2)") (class "Default")
      (node (ref "LED123") (pin "2") (pinfunction "GND_2") (pintype "unspecified"))
    )
    (net (code "645") (name "unconnected-(LED123-VDD-Pad5)") (class "Default")
      (node (ref "LED123") (pin "5") (pinfunction "VDD_5") (pintype "unspecified"))
    )
    (net (code "646") (name "unconnected-(LED124-GND-Pad2)") (class "Default")
      (node (ref "LED124") (pin "2") (pinfunction "GND_2") (pintype "unspecified"))
    )
    (net (code "647") (name "unconnected-(LED124-VDD-Pad5)") (class "Default")
      (node (ref "LED124") (pin "5") (pinfunction "VDD_5") (pintype "unspecified"))
    )
    (net (code "648") (name "unconnected-(LED125-GND-Pad2)") (class "Default")
      (node (ref "LED125") (pin "2") (pinfunction "GND_2") (pintype "unspecified"))
    )
    (net (code "649") (name "unconnected-(LED125-VDD-Pad5)") (class "Default")
      (node (ref "LED125") (pin "5") (pinfunction "VDD_5") (pintype "unspecified"))
    )
    (net (code "650") (name "unconnected-(LED126-GND-Pad2)") (class "Default")
      (node (ref "LED126") (pin "2") (pinfunction "GND_2") (pintype "unspecified"))
    )
    (net (code "651") (name "unconnected-(LED126-VDD-Pad5)") (class "Default")
      (node (ref "LED126") (pin "5") (pinfunction "VDD_5") (pintype "unspecified"))
    )
    (net (code "652") (name "unconnected-(LED127-GND-Pad2)") (class "Default")
      (node (ref "LED127") (pin "2") (pinfunction "GND_2") (pintype "unspecified"))
    )
    (net (code "653") (name "unconnected-(LED127-VDD-Pad5)") (class "Default")
      (node (ref "LED127") (pin "5") (pinfunction "VDD_5") (pintype "unspecified"))
    )
    (net (code "654") (name "unconnected-(LED128-GND-Pad2)") (class "Default")
      (node (ref "LED128") (pin "2") (pinfunction "GND_2") (pintype "unspecified"))
    )
    (net (code "655") (name "unconnected-(LED128-VDD-Pad5)") (class "Default")
      (node (ref "LED128") (pin "5") (pinfunction "VDD_5") (pintype "unspecified"))
    )
    (net (code "656") (name "unconnected-(LED129-GND-Pad2)") (class "Default")
      (node (ref "LED129") (pin "2") (pinfunction "GND_2") (pintype "unspecified"))
    )
    (net (code "657") (name "unconnected-(LED129-VDD-Pad5)") (class "Default")
      (node (ref "LED129") (pin "5") (pinfunction "VDD_5") (pintype "unspecified"))
    )
    (net (code "658") (name "unconnected-(LED130-GND-Pad2)") (class "Default")
      (node (ref "LED130") (pin "2") (pinfunction "GND_2") (pintype "unspecified"))
    )
    (net (code "659") (name "unconnected-(LED130-VDD-Pad5)") (class "Default")
      (node (ref "LED130") (pin "5") (pinfunction "VDD_5") (pintype "unspecified"))
    )
    (net (code "660") (name "unconnected-(LED131-GND-Pad2)") (class "Default")
      (node (ref "LED131") (pin "2") (pinfunction "GND_2") (pintype "unspecified"))
    )
    (net (code "661") (name "unconnected-(LED131-VDD-Pad5)") (class "Default")
      (node (ref "LED131") (pin "5") (pinfunction "VDD_5") (pintype "unspecified"))
    )
    (net (code "662") (name "unconnected-(LED134-GND-Pad2)") (class "Default")
      (node (ref "LED134") (pin "2") (pinfunction "GND_2") (pintype "unspecified"))
    )
    (net (code "663") (name "unconnected-(LED134-VDD-Pad5)") (class "Default")
      (node (ref "LED134") (pin "5") (pinfunction "VDD_5") (pintype "unspecified"))
    )
    (net (code "664") (name "unconnected-(LED135-GND-Pad2)") (class "Default")
      (node (ref "LED135") (pin "2") (pinfunction "GND_2") (pintype "unspecified"))
    )
    (net (code "665") (name "unconnected-(LED135-VDD-Pad5)") (class "Default")
      (node (ref "LED135") (pin "5") (pinfunction "VDD_5") (pintype "unspecified"))
    )
    (net (code "666") (name "unconnected-(LED136-GND-Pad2)") (class "Default")
      (node (ref "LED136") (pin "2") (pinfunction "GND_2") (pintype "unspecified"))
    )
    (net (code "667") (name "unconnected-(LED136-VDD-Pad5)") (class "Default")
      (node (ref "LED136") (pin "5") (pinfunction "VDD_5") (pintype "unspecified"))
    )
    (net (code "668") (name "unconnected-(LED137-GND-Pad2)") (class "Default")
      (node (ref "LED137") (pin "2") (pinfunction "GND_2") (pintype "unspecified"))
    )
    (net (code "669") (name "unconnected-(LED137-VDD-Pad5)") (class "Default")
      (node (ref "LED137") (pin "5") (pinfunction "VDD_5") (pintype "unspecified"))
    )
    (net (code "670") (name "unconnected-(LED138-GND-Pad2)") (class "Default")
      (node (ref "LED138") (pin "2") (pinfunction "GND_2") (pintype "unspecified"))
    )
    (net (code "671") (name "unconnected-(LED138-VDD-Pad5)") (class "Default")
      (node (ref "LED138") (pin "5") (pinfunction "VDD_5") (pintype "unspecified"))
    )
    (net (code "672") (name "unconnected-(LED139-GND-Pad2)") (class "Default")
      (node (ref "LED139") (pin "2") (pinfunction "GND_2") (pintype "unspecified"))
    )
    (net (code "673") (name "unconnected-(LED139-VDD-Pad5)") (class "Default")
      (node (ref "LED139") (pin "5") (pinfunction "VDD_5") (pintype "unspecified"))
    )
    (net (code "674") (name "unconnected-(LED140-GND-Pad2)") (class "Default")
      (node (ref "LED140") (pin "2") (pinfunction "GND_2") (pintype "unspecified"))
    )
    (net (code "675") (name "unconnected-(LED140-VDD-Pad5)") (class "Default")
      (node (ref "LED140") (pin "5") (pinfunction "VDD_5") (pintype "unspecified"))
    )
    (net (code "676") (name "unconnected-(LED141-GND-Pad2)") (class "Default")
      (node (ref "LED141") (pin "2") (pinfunction "GND_2") (pintype "unspecified"))
    )
    (net (code "677") (name "unconnected-(LED141-VDD-Pad5)") (class "Default")
      (node (ref "LED141") (pin "5") (pinfunction "VDD_5") (pintype "unspecified"))
    )
    (net (code "678") (name "unconnected-(LED142-GND-Pad2)") (class "Default")
      (node (ref "LED142") (pin "2") (pinfunction "GND_2") (pintype "unspecified"))
    )
    (net (code "679") (name "unconnected-(LED142-VDD-Pad5)") (class "Default")
      (node (ref "LED142") (pin "5") (pinfunction "VDD_5") (pintype "unspecified"))
    )
    (net (code "680") (name "unconnected-(LED143-GND-Pad2)") (class "Default")
      (node (ref "LED143") (pin "2") (pinfunction "GND_2") (pintype "unspecified"))
    )
    (net (code "681") (name "unconnected-(LED143-VDD-Pad5)") (class "Default")
      (node (ref "LED143") (pin "5") (pinfunction "VDD_5") (pintype "unspecified"))
    )
    (net (code "682") (name "unconnected-(LED146-GND-Pad2)") (class "Default")
      (node (ref "LED146") (pin "2") (pinfunction "GND_2") (pintype "unspecified"))
    )
    (net (code "683") (name "unconnected-(LED146-VDD-Pad5)") (class "Default")
      (node (ref "LED146") (pin "5") (pinfunction "VDD_5") (pintype "unspecified"))
    )
    (net (code "684") (name "unconnected-(LED147-GND-Pad2)") (class "Default")
      (node (ref "LED147") (pin "2") (pinfunction "GND_2") (pintype "unspecified"))
    )
    (net (code "685") (name "unconnected-(LED147-VDD-Pad5)") (class "Default")
      (node (ref "LED147") (pin "5") (pinfunction "VDD_5") (pintype "unspecified"))
    )
    (net (code "686") (name "unconnected-(LED148-GND-Pad2)") (class "Default")
      (node (ref "LED148") (pin "2") (pinfunction "GND_2") (pintype "unspecified"))
    )
    (net (code "687") (name "unconnected-(LED148-VDD-Pad5)") (class "Default")
      (node (ref "LED148") (pin "5") (pinfunction "VDD_5") (pintype "unspecified"))
    )
    (net (code "688") (name "unconnected-(LED149-GND-Pad2)") (class "Default")
      (node (ref "LED149") (pin "2") (pinfunction "GND_2") (pintype "unspecified"))
    )
    (net (code "689") (name "unconnected-(LED149-VDD-Pad5)") (class "Default")
      (node (ref "LED149") (pin "5") (pinfunction "VDD_5") (pintype "unspecified"))
    )
    (net (code "690") (name "unconnected-(LED150-GND-Pad2)") (class "Default")
      (node (ref "LED150") (pin "2") (pinfunction "GND_2") (pintype "unspecified"))
    )
    (net (code "691") (name "unconnected-(LED150-VDD-Pad5)") (class "Default")
      (node (ref "LED150") (pin "5") (pinfunction "VDD_5") (pintype "unspecified"))
    )
    (net (code "692") (name "unconnected-(LED151-GND-Pad2)") (class "Default")
      (node (ref "LED151") (pin "2") (pinfunction "GND_2") (pintype "unspecified"))
    )
    (net (code "693") (name "unconnected-(LED151-VDD-Pad5)") (class "Default")
      (node (ref "LED151") (pin "5") (pinfunction "VDD_5") (pintype "unspecified"))
    )
    (net (code "694") (name "unconnected-(LED152-GND-Pad2)") (class "Default")
      (node (ref "LED152") (pin "2") (pinfunction "GND_2") (pintype "unspecified"))
    )
    (net (code "695") (name "unconnected-(LED152-VDD-Pad5)") (class "Default")
      (node (ref "LED152") (pin "5") (pinfunction "VDD_5") (pintype "unspecified"))
    )
    (net (code "696") (name "unconnected-(LED153-GND-Pad2)") (class "Default")
      (node (ref "LED153") (pin "2") (pinfunction "GND_2") (pintype "unspecified"))
    )
    (net (code "697") (name "unconnected-(LED153-VDD-Pad5)") (class "Default")
      (node (ref "LED153") (pin "5") (pinfunction "VDD_5") (pintype "unspecified"))
    )
    (net (code "698") (name "unconnected-(LED154-GND-Pad2)") (class "Default")
      (node (ref "LED154") (pin "2") (pinfunction "GND_2") (pintype "unspecified"))
    )
    (net (code "699") (name "unconnected-(LED154-VDD-Pad5)") (class "Default")
      (node (ref "LED154") (pin "5") (pinfunction "VDD_5") (pintype "unspecified"))
    )
    (net (code "700") (name "unconnected-(LED155-GND-Pad2)") (class "Default")
      (node (ref "LED155") (pin "2") (pinfunction "GND_2") (pintype "unspecified"))
    )
    (net (code "701") (name "unconnected-(LED155-VDD-Pad5)") (class "Default")
      (node (ref "LED155") (pin "5") (pinfunction "VDD_5") (pintype "unspecified"))
    )
    (net (code "702") (name "unconnected-(LED158-GND-Pad2)") (class "Default")
      (node (ref "LED158") (pin "2") (pinfunction "GND_2") (pintype "unspecified"))
    )
    (net (code "703") (name "unconnected-(LED158-VDD-Pad5)") (class "Default")
      (node (ref "LED158") (pin "5") (pinfunction "VDD_5") (pintype "unspecified"))
    )
    (net (code "704") (name "unconnected-(LED159-GND-Pad2)") (class "Default")
      (node (ref "LED159") (pin "2") (pinfunction "GND_2") (pintype "unspecified"))
    )
    (net (code "705") (name "unconnected-(LED159-VDD-Pad5)") (class "Default")
      (node (ref "LED159") (pin "5") (pinfunction "VDD_5") (pintype "unspecified"))
    )
    (net (code "706") (name "unconnected-(LED160-GND-Pad2)") (class "Default")
      (node (ref "LED160") (pin "2") (pinfunction "GND_2") (pintype "unspecified"))
    )
    (net (code "707") (name "unconnected-(LED160-VDD-Pad5)") (class "Default")
      (node (ref "LED160") (pin "5") (pinfunction "VDD_5") (pintype "unspecified"))
    )
    (net (code "708") (name "unconnected-(LED161-GND-Pad2)") (class "Default")
      (node (ref "LED161") (pin "2") (pinfunction "GND_2") (pintype "unspecified"))
    )
    (net (code "709") (name "unconnected-(LED161-VDD-Pad5)") (class "Default")
      (node (ref "LED161") (pin "5") (pinfunction "VDD_5") (pintype "unspecified"))
    )
    (net (code "710") (name "unconnected-(LED162-GND-Pad2)") (class "Default")
      (node (ref "LED162") (pin "2") (pinfunction "GND_2") (pintype "unspecified"))
    )
    (net (code "711") (name "unconnected-(LED162-VDD-Pad5)") (class "Default")
      (node (ref "LED162") (pin "5") (pinfunction "VDD_5") (pintype "unspecified"))
    )
    (net (code "712") (name "unconnected-(LED163-GND-Pad2)") (class "Default")
      (node (ref "LED163") (pin "2") (pinfunction "GND_2") (pintype "unspecified"))
    )
    (net (code "713") (name "unconnected-(LED163-VDD-Pad5)") (class "Default")
      (node (ref "LED163") (pin "5") (pinfunction "VDD_5") (pintype "unspecified"))
    )
    (net (code "714") (name "unconnected-(LED164-GND-Pad2)") (class "Default")
      (node (ref "LED164") (pin "2") (pinfunction "GND_2") (pintype "unspecified"))
    )
    (net (code "715") (name "unconnected-(LED164-VDD-Pad5)") (class "Default")
      (node (ref "LED164") (pin "5") (pinfunction "VDD_5") (pintype "unspecified"))
    )
    (net (code "716") (name "unconnected-(LED165-GND-Pad2)") (class "Default")
      (node (ref "LED165") (pin "2") (pinfunction "GND_2") (pintype "unspecified"))
    )
    (net (code "717") (name "unconnected-(LED165-VDD-Pad5)") (class "Default")
      (node (ref "LED165") (pin "5") (pinfunction "VDD_5") (pintype "unspecified"))
    )
    (net (code "718") (name "unconnected-(LED166-GND-Pad2)") (class "Default")
      (node (ref "LED166") (pin "2") (pinfunction "GND_2") (pintype "unspecified"))
    )
    (net (code "719") (name "unconnected-(LED166-VDD-Pad5)") (class "Default")
      (node (ref "LED166") (pin "5") (pinfunction "VDD_5") (pintype "unspecified"))
    )
    (net (code "720") (name "unconnected-(LED167-GND-Pad2)") (class "Default")
      (node (ref "LED167") (pin "2") (pinfunction "GND_2") (pintype "unspecified"))
    )
    (net (code "721") (name "unconnected-(LED167-VDD-Pad5)") (class "Default")
      (node (ref "LED167") (pin "5") (pinfunction "VDD_5") (pintype "unspecified"))
    )
    (net (code "722") (name "unconnected-(LED170-GND-Pad2)") (class "Default")
      (node (ref "LED170") (pin "2") (pinfunction "GND_2") (pintype "unspecified"))
    )
    (net (code "723") (name "unconnected-(LED170-VDD-Pad5)") (class "Default")
      (node (ref "LED170") (pin "5") (pinfunction "VDD_5") (pintype "unspecified"))
    )
    (net (code "724") (name "unconnected-(LED171-GND-Pad2)") (class "Default")
      (node (ref "LED171") (pin "2") (pinfunction "GND_2") (pintype "unspecified"))
    )
    (net (code "725") (name "unconnected-(LED171-VDD-Pad5)") (class "Default")
      (node (ref "LED171") (pin "5") (pinfunction "VDD_5") (pintype "unspecified"))
    )
    (net (code "726") (name "unconnected-(LED172-GND-Pad2)") (class "Default")
      (node (ref "LED172") (pin "2") (pinfunction "GND_2") (pintype "unspecified"))
    )
    (net (code "727") (name "unconnected-(LED172-VDD-Pad5)") (class "Default")
      (node (ref "LED172") (pin "5") (pinfunction "VDD_5") (pintype "unspecified"))
    )
    (net (code "728") (name "unconnected-(LED173-GND-Pad2)") (class "Default")
      (node (ref "LED173") (pin "2") (pinfunction "GND_2") (pintype "unspecified"))
    )
    (net (code "729") (name "unconnected-(LED173-VDD-Pad5)") (class "Default")
      (node (ref "LED173") (pin "5") (pinfunction "VDD_5") (pintype "unspecified"))
    )
    (net (code "730") (name "unconnected-(LED174-GND-Pad2)") (class "Default")
      (node (ref "LED174") (pin "2") (pinfunction "GND_2") (pintype "unspecified"))
    )
    (net (code "731") (name "unconnected-(LED174-VDD-Pad5)") (class "Default")
      (node (ref "LED174") (pin "5") (pinfunction "VDD_5") (pintype "unspecified"))
    )
    (net (code "732") (name "unconnected-(LED175-GND-Pad2)") (class "Default")
      (node (ref "LED175") (pin "2") (pinfunction "GND_2") (pintype "unspecified"))
    )
    (net (code "733") (name "unconnected-(LED175-VDD-Pad5)") (class "Default")
      (node (ref "LED175") (pin "5") (pinfunction "VDD_5") (pintype "unspecified"))
    )
    (net (code "734") (name "unconnected-(LED176-GND-Pad2)") (class "Default")
      (node (ref "LED176") (pin "2") (pinfunction "GND_2") (pintype "unspecified"))
    )
    (net (code "735") (name "unconnected-(LED176-VDD-Pad5)") (class "Default")
      (node (ref "LED176") (pin "5") (pinfunction "VDD_5") (pintype "unspecified"))
    )
    (net (code "736") (name "unconnected-(LED177-GND-Pad2)") (class "Default")
      (node (ref "LED177") (pin "2") (pinfunction "GND_2") (pintype "unspecified"))
    )
    (net (code "737") (name "unconnected-(LED177-VDD-Pad5)") (class "Default")
      (node (ref "LED177") (pin "5") (pinfunction "VDD_5") (pintype "unspecified"))
    )
    (net (code "738") (name "unconnected-(LED178-GND-Pad2)") (class "Default")
      (node (ref "LED178") (pin "2") (pinfunction "GND_2") (pintype "unspecified"))
    )
    (net (code "739") (name "unconnected-(LED178-VDD-Pad5)") (class "Default")
      (node (ref "LED178") (pin "5") (pinfunction "VDD_5") (pintype "unspecified"))
    )
    (net (code "740") (name "unconnected-(LED179-GND-Pad2)") (class "Default")
      (node (ref "LED179") (pin "2") (pinfunction "GND_2") (pintype "unspecified"))
    )
    (net (code "741") (name "unconnected-(LED179-VDD-Pad5)") (class "Default")
      (node (ref "LED179") (pin "5") (pinfunction "VDD_5") (pintype "unspecified"))
    )
    (net (code "742") (name "unconnected-(LED182-GND-Pad2)") (class "Default")
      (node (ref "LED182") (pin "2") (pinfunction "GND_2") (pintype "unspecified"))
    )
    (net (code "743") (name "unconnected-(LED182-VDD-Pad5)") (class "Default")
      (node (ref "LED182") (pin "5") (pinfunction "VDD_5") (pintype "unspecified"))
    )
    (net (code "744") (name "unconnected-(LED183-GND-Pad2)") (class "Default")
      (node (ref "LED183") (pin "2") (pinfunction "GND_2") (pintype "unspecified"))
    )
    (net (code "745") (name "unconnected-(LED183-VDD-Pad5)") (class "Default")
      (node (ref "LED183") (pin "5") (pinfunction "VDD_5") (pintype "unspecified"))
    )
    (net (code "746") (name "unconnected-(LED184-GND-Pad2)") (class "Default")
      (node (ref "LED184") (pin "2") (pinfunction "GND_2") (pintype "unspecified"))
    )
    (net (code "747") (name "unconnected-(LED184-VDD-Pad5)") (class "Default")
      (node (ref "LED184") (pin "5") (pinfunction "VDD_5") (pintype "unspecified"))
    )
    (net (code "748") (name "unconnected-(LED185-GND-Pad2)") (class "Default")
      (node (ref "LED185") (pin "2") (pinfunction "GND_2") (pintype "unspecified"))
    )
    (net (code "749") (name "unconnected-(LED185-VDD-Pad5)") (class "Default")
      (node (ref "LED185") (pin "5") (pinfunction "VDD_5") (pintype "unspecified"))
    )
    (net (code "750") (name "unconnected-(LED186-GND-Pad2)") (class "Default")
      (node (ref "LED186") (pin "2") (pinfunction "GND_2") (pintype "unspecified"))
    )
    (net (code "751") (name "unconnected-(LED186-VDD-Pad5)") (class "Default")
      (node (ref "LED186") (pin "5") (pinfunction "VDD_5") (pintype "unspecified"))
    )
    (net (code "752") (name "unconnected-(LED187-GND-Pad2)") (class "Default")
      (node (ref "LED187") (pin "2") (pinfunction "GND_2") (pintype "unspecified"))
    )
    (net (code "753") (name "unconnected-(LED187-VDD-Pad5)") (class "Default")
      (node (ref "LED187") (pin "5") (pinfunction "VDD_5") (pintype "unspecified"))
    )
    (net (code "754") (name "unconnected-(LED188-GND-Pad2)") (class "Default")
      (node (ref "LED188") (pin "2") (pinfunction "GND_2") (pintype "unspecified"))
    )
    (net (code "755") (name "unconnected-(LED188-VDD-Pad5)") (class "Default")
      (node (ref "LED188") (pin "5") (pinfunction "VDD_5") (pintype "unspecified"))
    )
    (net (code "756") (name "unconnected-(LED189-GND-Pad2)") (class "Default")
      (node (ref "LED189") (pin "2") (pinfunction "GND_2") (pintype "unspecified"))
    )
    (net (code "757") (name "unconnected-(LED189-VDD-Pad5)") (class "Default")
      (node (ref "LED189") (pin "5") (pinfunction "VDD_5") (pintype "unspecified"))
    )
    (net (code "758") (name "unconnected-(LED190-GND-Pad2)") (class "Default")
      (node (ref "LED190") (pin "2") (pinfunction "GND_2") (pintype "unspecified"))
    )
    (net (code "759") (name "unconnected-(LED190-VDD-Pad5)") (class "Default")
      (node (ref "LED190") (pin "5") (pinfunction "VDD_5") (pintype "unspecified"))
    )
    (net (code "760") (name "unconnected-(LED191-GND-Pad2)") (class "Default")
      (node (ref "LED191") (pin "2") (pinfunction "GND_2") (pintype "unspecified"))
    )
    (net (code "761") (name "unconnected-(LED191-VDD-Pad5)") (class "Default")
      (node (ref "LED191") (pin "5") (pinfunction "VDD_5") (pintype "unspecified"))
    )
    (net (code "762") (name "unconnected-(LED194-GND-Pad2)") (class "Default")
      (node (ref "LED194") (pin "2") (pinfunction "GND_2") (pintype "unspecified"))
    )
    (net (code "763") (name "unconnected-(LED194-VDD-Pad5)") (class "Default")
      (node (ref "LED194") (pin "5") (pinfunction "VDD_5") (pintype "unspecified"))
    )
    (net (code "764") (name "unconnected-(LED195-GND-Pad2)") (class "Default")
      (node (ref "LED195") (pin "2") (pinfunction "GND_2") (pintype "unspecified"))
    )
    (net (code "765") (name "unconnected-(LED195-VDD-Pad5)") (class "Default")
      (node (ref "LED195") (pin "5") (pinfunction "VDD_5") (pintype "unspecified"))
    )
    (net (code "766") (name "unconnected-(LED196-GND-Pad2)") (class "Default")
      (node (ref "LED196") (pin "2") (pinfunction "GND_2") (pintype "unspecified"))
    )
    (net (code "767") (name "unconnected-(LED196-VDD-Pad5)") (class "Default")
      (node (ref "LED196") (pin "5") (pinfunction "VDD_5") (pintype "unspecified"))
    )
    (net (code "768") (name "unconnected-(LED197-GND-Pad2)") (class "Default")
      (node (ref "LED197") (pin "2") (pinfunction "GND_2") (pintype "unspecified"))
    )
    (net (code "769") (name "unconnected-(LED197-VDD-Pad5)") (class "Default")
      (node (ref "LED197") (pin "5") (pinfunction "VDD_5") (pintype "unspecified"))
    )
    (net (code "770") (name "unconnected-(LED198-GND-Pad2)") (class "Default")
      (node (ref "LED198") (pin "2") (pinfunction "GND_2") (pintype "unspecified"))
    )
    (net (code "771") (name "unconnected-(LED198-VDD-Pad5)") (class "Default")
      (node (ref "LED198") (pin "5") (pinfunction "VDD_5") (pintype "unspecified"))
    )
    (net (code "772") (name "unconnected-(LED199-GND-Pad2)") (class "Default")
      (node (ref "LED199") (pin "2") (pinfunction "GND_2") (pintype "unspecified"))
    )
    (net (code "773") (name "unconnected-(LED199-VDD-Pad5)") (class "Default")
      (node (ref "LED199") (pin "5") (pinfunction "VDD_5") (pintype "unspecified"))
    )
    (net (code "774") (name "unconnected-(LED200-GND-Pad2)") (class "Default")
      (node (ref "LED200") (pin "2") (pinfunction "GND_2") (pintype "unspecified"))
    )
    (net (code "775") (name "unconnected-(LED200-VDD-Pad5)") (class "Default")
      (node (ref "LED200") (pin "5") (pinfunction "VDD_5") (pintype "unspecified"))
    )
    (net (code "776") (name "unconnected-(LED201-GND-Pad2)") (class "Default")
      (node (ref "LED201") (pin "2") (pinfunction "GND_2") (pintype "unspecified"))
    )
    (net (code "777") (name "unconnected-(LED201-VDD-Pad5)") (class "Default")
      (node (ref "LED201") (pin "5") (pinfunction "VDD_5") (pintype "unspecified"))
    )
    (net (code "778") (name "unconnected-(LED202-GND-Pad2)") (class "Default")
      (node (ref "LED202") (pin "2") (pinfunction "GND_2") (pintype "unspecified"))
    )
    (net (code "779") (name "unconnected-(LED202-VDD-Pad5)") (class "Default")
      (node (ref "LED202") (pin "5") (pinfunction "VDD_5") (pintype "unspecified"))
    )
    (net (code "780") (name "unconnected-(LED203-GND-Pad2)") (class "Default")
      (node (ref "LED203") (pin "2") (pinfunction "GND_2") (pintype "unspecified"))
    )
    (net (code "781") (name "unconnected-(LED203-VDD-Pad5)") (class "Default")
      (node (ref "LED203") (pin "5") (pinfunction "VDD_5") (pintype "unspecified"))
    )
    (net (code "782") (name "unconnected-(LED205-CKO-Pad6)") (class "Default")
      (node (ref "LED205") (pin "6") (pinfunction "CKO_6") (pintype "unspecified"))
    )
    (net (code "783") (name "unconnected-(LED205-SDO-Pad1)") (class "Default")
      (node (ref "LED205") (pin "1") (pinfunction "SDO_1") (pintype "unspecified"))
    )
    (net (code "784") (name "unconnected-(LED206-GND-Pad2)") (class "Default")
      (node (ref "LED206") (pin "2") (pinfunction "GND_2") (pintype "unspecified"))
    )
    (net (code "785") (name "unconnected-(LED206-VDD-Pad5)") (class "Default")
      (node (ref "LED206") (pin "5") (pinfunction "VDD_5") (pintype "unspecified"))
    )
    (net (code "786") (name "unconnected-(LED207-GND-Pad2)") (class "Default")
      (node (ref "LED207") (pin "2") (pinfunction "GND_2") (pintype "unspecified"))
    )
    (net (code "787") (name "unconnected-(LED207-VDD-Pad5)") (class "Default")
      (node (ref "LED207") (pin "5") (pinfunction "VDD_5") (pintype "unspecified"))
    )
    (net (code "788") (name "unconnected-(LED208-GND-Pad2)") (class "Default")
      (node (ref "LED208") (pin "2") (pinfunction "GND_2") (pintype "unspecified"))
    )
    (net (code "789") (name "unconnected-(LED208-VDD-Pad5)") (class "Default")
      (node (ref "LED208") (pin "5") (pinfunction "VDD_5") (pintype "unspecified"))
    )
    (net (code "790") (name "unconnected-(LED209-GND-Pad2)") (class "Default")
      (node (ref "LED209") (pin "2") (pinfunction "GND_2") (pintype "unspecified"))
    )
    (net (code "791") (name "unconnected-(LED209-VDD-Pad5)") (class "Default")
      (node (ref "LED209") (pin "5") (pinfunction "VDD_5") (pintype "unspecified"))
    )
    (net (code "792") (name "unconnected-(LED210-GND-Pad2)") (class "Default")
      (node (ref "LED210") (pin "2") (pinfunction "GND_2") (pintype "unspecified"))
    )
    (net (code "793") (name "unconnected-(LED210-VDD-Pad5)") (class "Default")
      (node (ref "LED210") (pin "5") (pinfunction "VDD_5") (pintype "unspecified"))
    )
    (net (code "794") (name "unconnected-(LED211-GND-Pad2)") (class "Default")
      (node (ref "LED211") (pin "2") (pinfunction "GND_2") (pintype "unspecified"))
    )
    (net (code "795") (name "unconnected-(LED211-VDD-Pad5)") (class "Default")
      (node (ref "LED211") (pin "5") (pinfunction "VDD_5") (pintype "unspecified"))
    )
    (net (code "796") (name "unconnected-(LED212-GND-Pad2)") (class "Default")
      (node (ref "LED212") (pin "2") (pinfunction "GND_2") (pintype "unspecified"))
    )
    (net (code "797") (name "unconnected-(LED212-VDD-Pad5)") (class "Default")
      (node (ref "LED212") (pin "5") (pinfunction "VDD_5") (pintype "unspecified"))
    )
    (net (code "798") (name "unconnected-(LED213-GND-Pad2)") (class "Default")
      (node (ref "LED213") (pin "2") (pinfunction "GND_2") (pintype "unspecified"))
    )
    (net (code "799") (name "unconnected-(LED213-VDD-Pad5)") (class "Default")
      (node (ref "LED213") (pin "5") (pinfunction "VDD_5") (pintype "unspecified"))
    )
    (net (code "800") (name "unconnected-(LED214-GND-Pad2)") (class "Default")
      (node (ref "LED214") (pin "2") (pinfunction "GND_2") (pintype "unspecified"))
    )
    (net (code "801") (name "unconnected-(LED214-VDD-Pad5)") (class "Default")
      (node (ref "LED214") (pin "5") (pinfunction "VDD_5") (pintype "unspecified"))
    )
    (net (code "802") (name "unconnected-(LED215-GND-Pad2)") (class "Default")
      (node (ref "LED215") (pin "2") (pinfunction "GND_2") (pintype "unspecified"))
    )
    (net (code "803") (name "unconnected-(LED215-VDD-Pad5)") (class "Default")
      (node (ref "LED215") (pin "5") (pinfunction "VDD_5") (pintype "unspecified"))
    )
    (net (code "804") (name "unconnected-(U1-3V3-Pad12)") (class "Default")
      (node (ref "U1") (pin "12") (pinfunction "3V3_12") (pintype "unspecified"))
    )
    (net (code "805") (name "unconnected-(U1-5V-Pad14)") (class "Default")
      (node (ref "U1") (pin "14") (pinfunction "5V_14") (pintype "unspecified"))
    )
    (net (code "806") (name "unconnected-(U1-D0-Pad1)") (class "Default")
      (node (ref "U1") (pin "1") (pinfunction "D0_1") (pintype "unspecified"))
    )
    (net (code "807") (name "unconnected-(U1-D1-Pad2)") (class "Default")
      (node (ref "U1") (pin "2") (pinfunction "D1_2") (pintype "unspecified"))
    )
    (net (code "808") (name "unconnected-(U1-D2-Pad3)") (class "Default")
      (node (ref "U1") (pin "3") (pinfunction "D2_3") (pintype "unspecified"))
    )
    (net (code "809") (name "unconnected-(U1-D3-Pad4)") (class "Default")
      (node (ref "U1") (pin "4") (pinfunction "D3_4") (pintype "unspecified"))
    )
    (net (code "810") (name "unconnected-(U1-D4-Pad5)") (class "Default")
      (node (ref "U1") (pin "5") (pinfunction "D4_5") (pintype "unspecified"))
    )
    (net (code "811") (name "unconnected-(U1-D5-Pad6)") (class "Default")
      (node (ref "U1") (pin "6") (pinfunction "D5_6") (pintype "unspecified"))
    )
    (net (code "812") (name "unconnected-(U1-D7-Pad8)") (class "Default")
      (node (ref "U1") (pin "8") (pinfunction "D7_8") (pintype "unspecified"))
    )
    (net (code "813") (name "unconnected-(U1-D9-Pad10)") (class "Default")
      (node (ref "U1") (pin "10") (pinfunction "D9_10") (pintype "unspecified"))
    )
    (net (code "814") (name "unconnected-(U1-EN-Pad21)") (class "Default")
      (node (ref "U1") (pin "21") (pinfunction "EN_21") (pintype "unspecified"))
    )
    (net (code "815") (name "unconnected-(U1-GND-Pad13)") (class "Default")
      (node (ref "U1") (pin "13") (pinfunction "GND_13") (pintype "unspecified"))
    )
    (net (code "816") (name "unconnected-(U1-GND-Pad20)") (class "Default")
      (node (ref "U1") (pin "20") (pinfunction "GND_20") (pintype "unspecified"))
    )
    (net (code "817") (name "unconnected-(U1-MTCK-Pad18)") (class "Default")
      (node (ref "U1") (pin "18") (pinfunction "MTCK_18") (pintype "unspecified"))
    )
    (net (code "818") (name "unconnected-(U1-MTDI-Pad23)") (class "Default")
      (node (ref "U1") (pin "23") (pinfunction "MTDI_23") (pintype "unspecified"))
    )
    (net (code "819") (name "unconnected-(U1-MTMS-Pad19)") (class "Default")
      (node (ref "U1") (pin "19") (pinfunction "MTMS_19") (pintype "unspecified"))
    )
    (net (code "820") (name "unconnected-(U1-MYDO-Pad22)") (class "Default")
      (node (ref "U1") (pin "22") (pinfunction "MYDO_22") (pintype "unspecified"))
    )
    (net (code "821") (name "unconnected-(U1-PAD-Pad17)") (class "Default")
      (node (ref "U1") (pin "17") (pinfunction "PAD_17") (pintype "unspecified"))
    )
    (net (code "822") (name "unconnected-(U2-NC-Pad6)") (class "Default")
      (node (ref "U2") (pin "6") (pinfunction "NC_6") (pintype "unspecified+no_connect"))
    )
  )
)
